# 1-Schematic_Volumetric_Display.net
KiCad netlist of a schematic drawn in EasyEDA
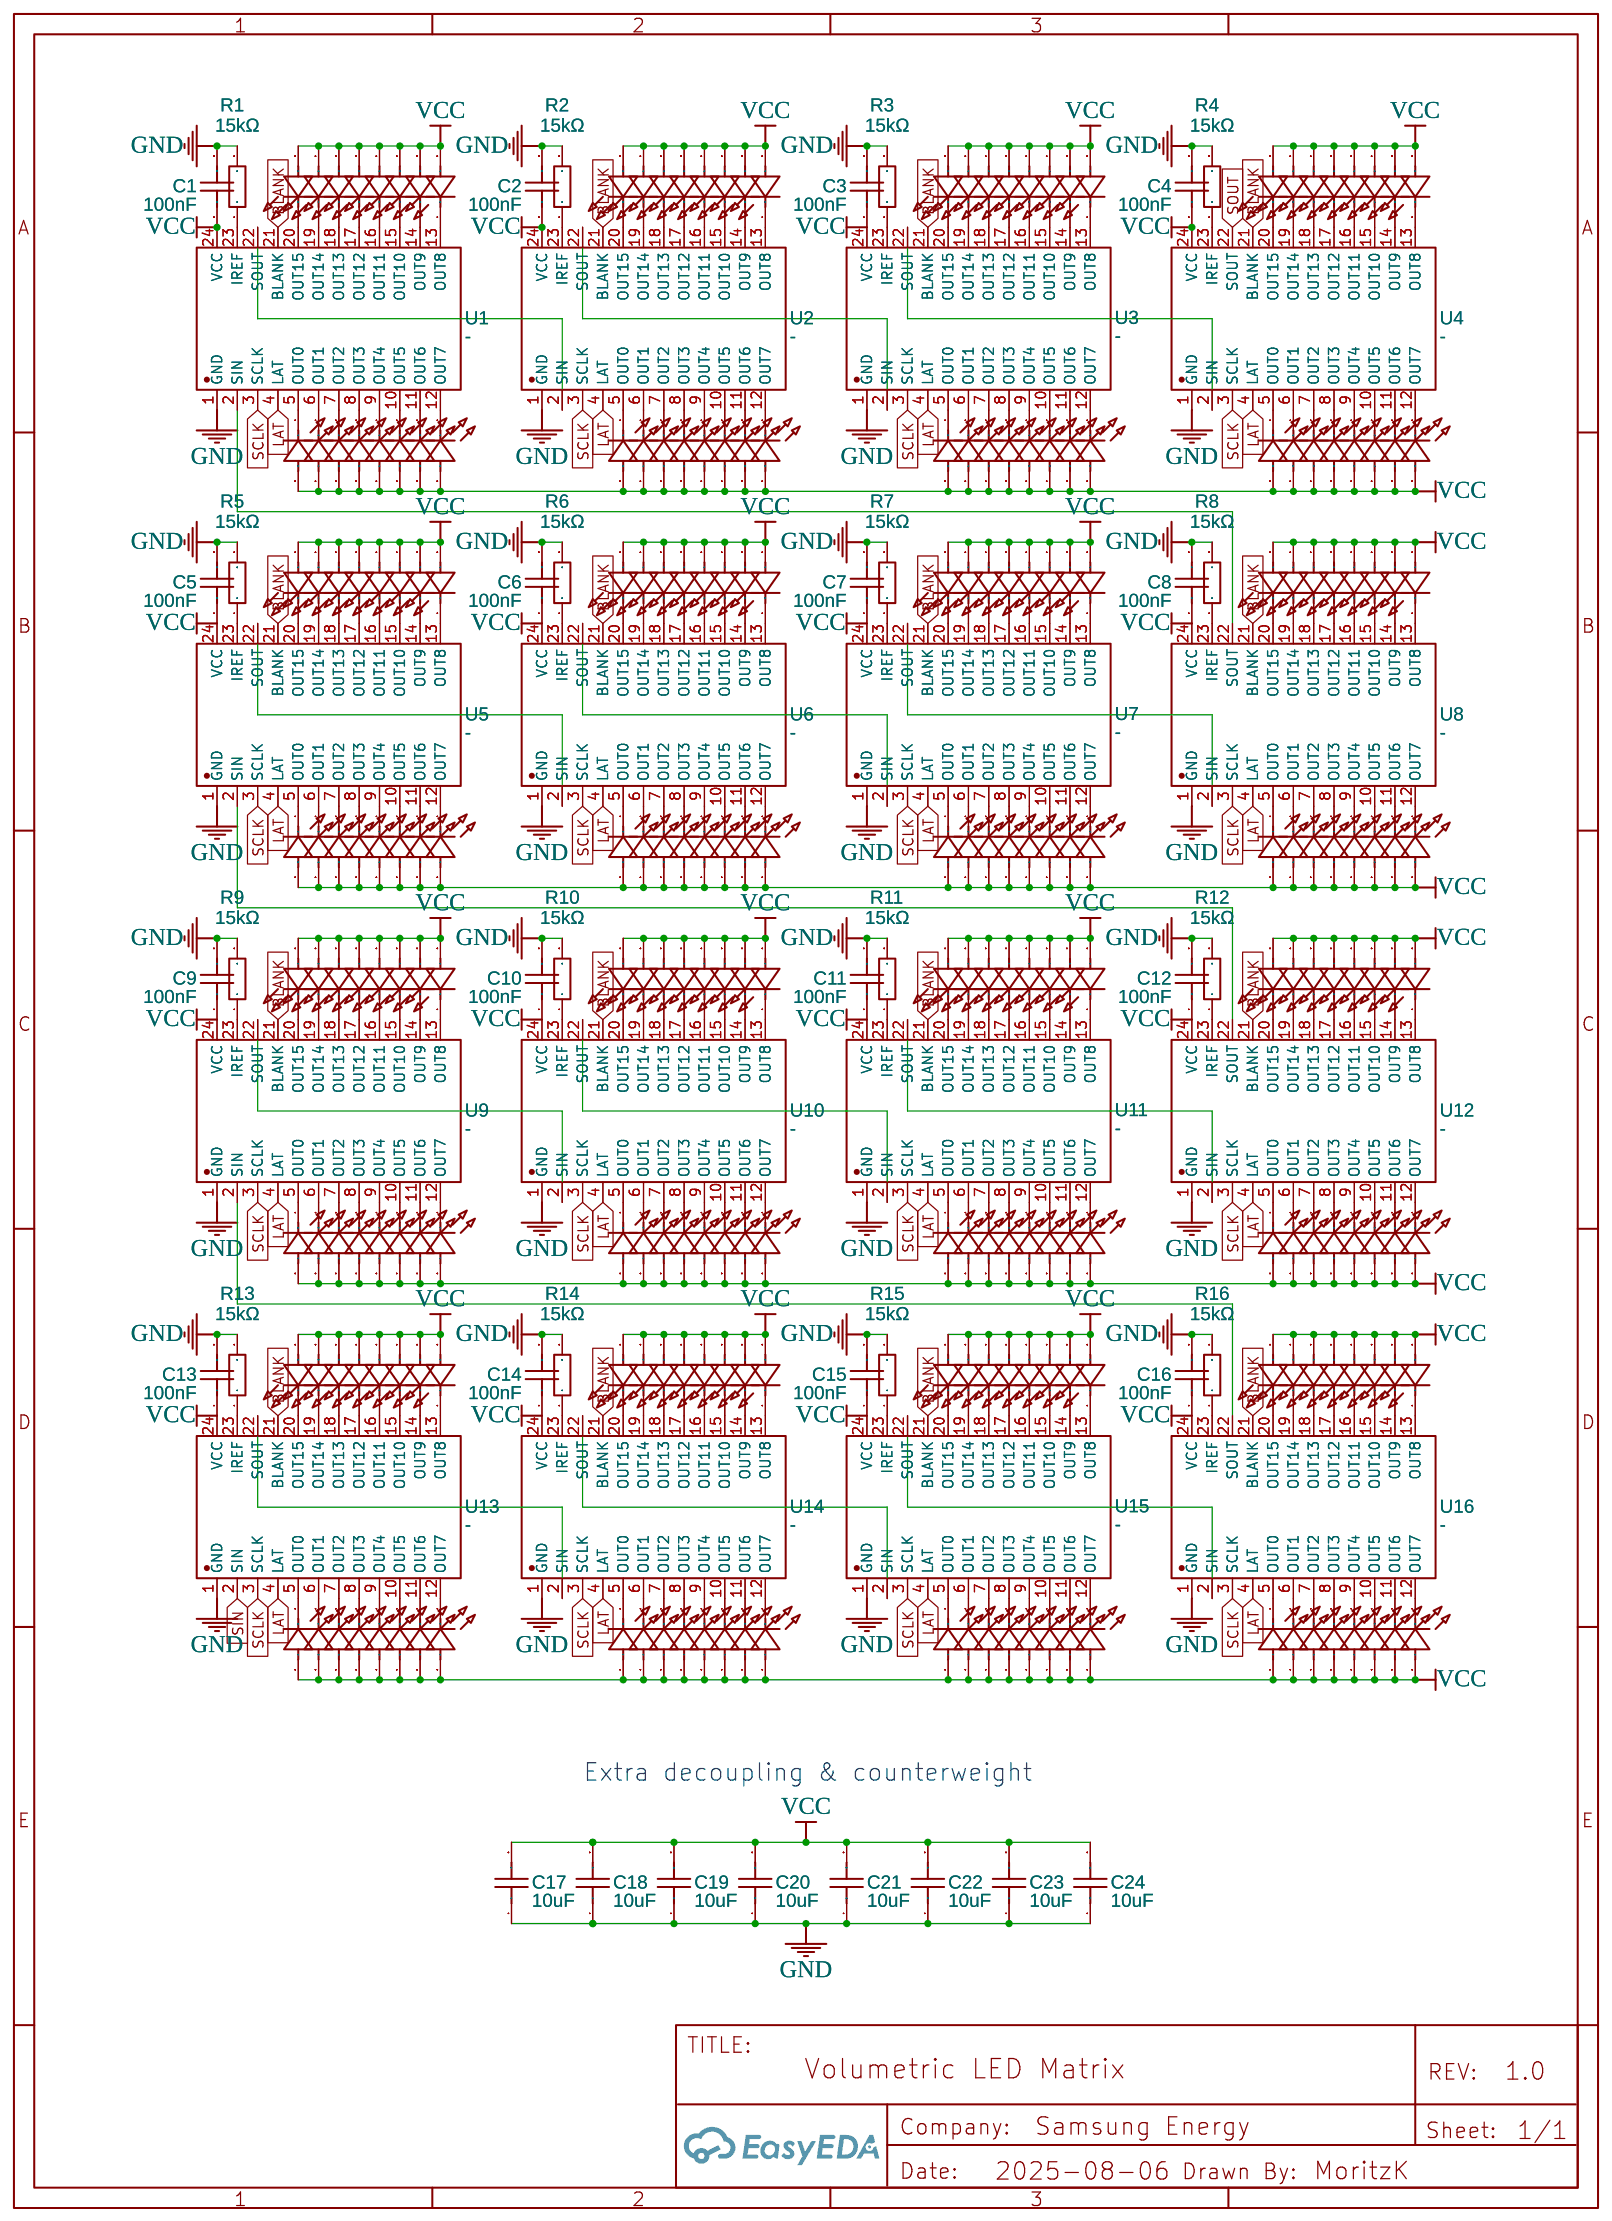
[diagram p0: schematic sheet]

(export (version "E")
  (design (tool "Eeschema 10.0.6"))
  (components
    (comp (ref "C1")
      (value "100nF")
      (fields
        (field (name "Manufacturer Part") "CC0603KRX7R9BB104")
        (field (name "Manufacturer") "YAGEO(国巨)")
      )
      (libsource (lib "") (part "CC0603KRX7R9BB104"))
    )
    (comp (ref "C2")
      (value "100nF")
      (fields
        (field (name "Manufacturer Part") "CC0603KRX7R9BB104")
        (field (name "Manufacturer") "YAGEO(国巨)")
      )
      (libsource (lib "") (part "CC0603KRX7R9BB104"))
    )
    (comp (ref "C3")
      (value "100nF")
      (fields
        (field (name "Manufacturer Part") "CC0603KRX7R9BB104")
        (field (name "Manufacturer") "YAGEO(国巨)")
      )
      (libsource (lib "") (part "CC0603KRX7R9BB104"))
    )
    (comp (ref "C4")
      (value "100nF")
      (fields
        (field (name "Manufacturer Part") "CC0603KRX7R9BB104")
        (field (name "Manufacturer") "YAGEO(国巨)")
      )
      (libsource (lib "") (part "CC0603KRX7R9BB104"))
    )
    (comp (ref "C5")
      (value "100nF")
      (fields
        (field (name "Manufacturer Part") "CC0603KRX7R9BB104")
        (field (name "Manufacturer") "YAGEO(国巨)")
      )
      (libsource (lib "") (part "CC0603KRX7R9BB104"))
    )
    (comp (ref "C6")
      (value "100nF")
      (fields
        (field (name "Manufacturer Part") "CC0603KRX7R9BB104")
        (field (name "Manufacturer") "YAGEO(国巨)")
      )
      (libsource (lib "") (part "CC0603KRX7R9BB104"))
    )
    (comp (ref "C7")
      (value "100nF")
      (fields
        (field (name "Manufacturer Part") "CC0603KRX7R9BB104")
        (field (name "Manufacturer") "YAGEO(国巨)")
      )
      (libsource (lib "") (part "CC0603KRX7R9BB104"))
    )
    (comp (ref "C8")
      (value "100nF")
      (fields
        (field (name "Manufacturer Part") "CC0603KRX7R9BB104")
        (field (name "Manufacturer") "YAGEO(国巨)")
      )
      (libsource (lib "") (part "CC0603KRX7R9BB104"))
    )
    (comp (ref "C9")
      (value "100nF")
      (fields
        (field (name "Manufacturer Part") "CC0603KRX7R9BB104")
        (field (name "Manufacturer") "YAGEO(国巨)")
      )
      (libsource (lib "") (part "CC0603KRX7R9BB104"))
    )
    (comp (ref "C10")
      (value "100nF")
      (fields
        (field (name "Manufacturer Part") "CC0603KRX7R9BB104")
        (field (name "Manufacturer") "YAGEO(国巨)")
      )
      (libsource (lib "") (part "CC0603KRX7R9BB104"))
    )
    (comp (ref "C11")
      (value "100nF")
      (fields
        (field (name "Manufacturer Part") "CC0603KRX7R9BB104")
        (field (name "Manufacturer") "YAGEO(国巨)")
      )
      (libsource (lib "") (part "CC0603KRX7R9BB104"))
    )
    (comp (ref "C12")
      (value "100nF")
      (fields
        (field (name "Manufacturer Part") "CC0603KRX7R9BB104")
        (field (name "Manufacturer") "YAGEO(国巨)")
      )
      (libsource (lib "") (part "CC0603KRX7R9BB104"))
    )
    (comp (ref "C13")
      (value "100nF")
      (fields
        (field (name "Manufacturer Part") "CC0603KRX7R9BB104")
        (field (name "Manufacturer") "YAGEO(国巨)")
      )
      (libsource (lib "") (part "CC0603KRX7R9BB104"))
    )
    (comp (ref "C14")
      (value "100nF")
      (fields
        (field (name "Manufacturer Part") "CC0603KRX7R9BB104")
        (field (name "Manufacturer") "YAGEO(国巨)")
      )
      (libsource (lib "") (part "CC0603KRX7R9BB104"))
    )
    (comp (ref "C15")
      (value "100nF")
      (fields
        (field (name "Manufacturer Part") "CC0603KRX7R9BB104")
        (field (name "Manufacturer") "YAGEO(国巨)")
      )
      (libsource (lib "") (part "CC0603KRX7R9BB104"))
    )
    (comp (ref "C16")
      (value "100nF")
      (fields
        (field (name "Manufacturer Part") "CC0603KRX7R9BB104")
        (field (name "Manufacturer") "YAGEO(国巨)")
      )
      (libsource (lib "") (part "CC0603KRX7R9BB104"))
    )
    (comp (ref "C17")
      (value "10uF")
      (fields
        (field (name "Manufacturer Part") "CL10A106KP8NNNC")
        (field (name "Manufacturer") "SAMSUNG(三星)")
      )
      (libsource (lib "") (part "CL10A106KP8NNNC"))
    )
    (comp (ref "C18")
      (value "10uF")
      (fields
        (field (name "Manufacturer Part") "CL10A106KP8NNNC")
        (field (name "Manufacturer") "SAMSUNG(三星)")
      )
      (libsource (lib "") (part "CL10A106KP8NNNC"))
    )
    (comp (ref "C19")
      (value "10uF")
      (fields
        (field (name "Manufacturer Part") "CL10A106KP8NNNC")
        (field (name "Manufacturer") "SAMSUNG(三星)")
      )
      (libsource (lib "") (part "CL10A106KP8NNNC"))
    )
    (comp (ref "C20")
      (value "10uF")
      (fields
        (field (name "Manufacturer Part") "CL10A106KP8NNNC")
        (field (name "Manufacturer") "SAMSUNG(三星)")
      )
      (libsource (lib "") (part "CL10A106KP8NNNC"))
    )
    (comp (ref "C21")
      (value "10uF")
      (fields
        (field (name "Manufacturer Part") "CL10A106KP8NNNC")
        (field (name "Manufacturer") "SAMSUNG(三星)")
      )
      (libsource (lib "") (part "CL10A106KP8NNNC"))
    )
    (comp (ref "C22")
      (value "10uF")
      (fields
        (field (name "Manufacturer Part") "CL10A106KP8NNNC")
        (field (name "Manufacturer") "SAMSUNG(三星)")
      )
      (libsource (lib "") (part "CL10A106KP8NNNC"))
    )
    (comp (ref "C23")
      (value "10uF")
      (fields
        (field (name "Manufacturer Part") "CL10A106KP8NNNC")
        (field (name "Manufacturer") "SAMSUNG(三星)")
      )
      (libsource (lib "") (part "CL10A106KP8NNNC"))
    )
    (comp (ref "C24")
      (value "10uF")
      (fields
        (field (name "Manufacturer Part") "CL10A106KP8NNNC")
        (field (name "Manufacturer") "SAMSUNG(三星)")
      )
      (libsource (lib "") (part "CL10A106KP8NNNC"))
    )
    (comp (ref "LED1")
      (value "F.0603.00106/P2-0603W7YS2-06T-001")
      (fields (field (name "Manufacturer") "TUOZHAN(拓展光电)"))
      (libsource (lib "") (part "F.0603.00106/P2-0603W7YS2-06T-001_1"))
    )
    (comp (ref "LED2")
      (value "F.0603.00106/P2-0603W7YS2-06T-001")
      (fields (field (name "Manufacturer") "TUOZHAN(拓展光电)"))
      (libsource (lib "") (part "F.0603.00106/P2-0603W7YS2-06T-001_1"))
    )
    (comp (ref "LED3")
      (value "F.0603.00106/P2-0603W7YS2-06T-001")
      (fields (field (name "Manufacturer") "TUOZHAN(拓展光电)"))
      (libsource (lib "") (part "F.0603.00106/P2-0603W7YS2-06T-001_1"))
    )
    (comp (ref "LED4")
      (value "F.0603.00106/P2-0603W7YS2-06T-001")
      (fields (field (name "Manufacturer") "TUOZHAN(拓展光电)"))
      (libsource (lib "") (part "F.0603.00106/P2-0603W7YS2-06T-001_1"))
    )
    (comp (ref "LED5")
      (value "F.0603.00106/P2-0603W7YS2-06T-001")
      (fields (field (name "Manufacturer") "TUOZHAN(拓展光电)"))
      (libsource (lib "") (part "F.0603.00106/P2-0603W7YS2-06T-001_1"))
    )
    (comp (ref "LED6")
      (value "F.0603.00106/P2-0603W7YS2-06T-001")
      (fields (field (name "Manufacturer") "TUOZHAN(拓展光电)"))
      (libsource (lib "") (part "F.0603.00106/P2-0603W7YS2-06T-001_1"))
    )
    (comp (ref "LED7")
      (value "F.0603.00106/P2-0603W7YS2-06T-001")
      (fields (field (name "Manufacturer") "TUOZHAN(拓展光电)"))
      (libsource (lib "") (part "F.0603.00106/P2-0603W7YS2-06T-001_1"))
    )
    (comp (ref "LED8")
      (value "F.0603.00106/P2-0603W7YS2-06T-001")
      (fields (field (name "Manufacturer") "TUOZHAN(拓展光电)"))
      (libsource (lib "") (part "F.0603.00106/P2-0603W7YS2-06T-001_1"))
    )
    (comp (ref "LED9")
      (value "F.0603.00106/P2-0603W7YS2-06T-001")
      (fields (field (name "Manufacturer") "TUOZHAN(拓展光电)"))
      (libsource (lib "") (part "F.0603.00106/P2-0603W7YS2-06T-001_1"))
    )
    (comp (ref "LED10")
      (value "F.0603.00106/P2-0603W7YS2-06T-001")
      (fields (field (name "Manufacturer") "TUOZHAN(拓展光电)"))
      (libsource (lib "") (part "F.0603.00106/P2-0603W7YS2-06T-001_1"))
    )
    (comp (ref "LED11")
      (value "F.0603.00106/P2-0603W7YS2-06T-001")
      (fields (field (name "Manufacturer") "TUOZHAN(拓展光电)"))
      (libsource (lib "") (part "F.0603.00106/P2-0603W7YS2-06T-001_1"))
    )
    (comp (ref "LED12")
      (value "F.0603.00106/P2-0603W7YS2-06T-001")
      (fields (field (name "Manufacturer") "TUOZHAN(拓展光电)"))
      (libsource (lib "") (part "F.0603.00106/P2-0603W7YS2-06T-001_1"))
    )
    (comp (ref "LED13")
      (value "F.0603.00106/P2-0603W7YS2-06T-001")
      (fields (field (name "Manufacturer") "TUOZHAN(拓展光电)"))
      (libsource (lib "") (part "F.0603.00106/P2-0603W7YS2-06T-001_1"))
    )
    (comp (ref "LED14")
      (value "F.0603.00106/P2-0603W7YS2-06T-001")
      (fields (field (name "Manufacturer") "TUOZHAN(拓展光电)"))
      (libsource (lib "") (part "F.0603.00106/P2-0603W7YS2-06T-001_1"))
    )
    (comp (ref "LED15")
      (value "F.0603.00106/P2-0603W7YS2-06T-001")
      (fields (field (name "Manufacturer") "TUOZHAN(拓展光电)"))
      (libsource (lib "") (part "F.0603.00106/P2-0603W7YS2-06T-001_1"))
    )
    (comp (ref "LED16")
      (value "F.0603.00106/P2-0603W7YS2-06T-001")
      (fields (field (name "Manufacturer") "TUOZHAN(拓展光电)"))
      (libsource (lib "") (part "F.0603.00106/P2-0603W7YS2-06T-001_1"))
    )
    (comp (ref "LED17")
      (value "F.0603.00106/P2-0603W7YS2-06T-001")
      (fields (field (name "Manufacturer") "TUOZHAN(拓展光电)"))
      (libsource (lib "") (part "F.0603.00106/P2-0603W7YS2-06T-001_1"))
    )
    (comp (ref "LED18")
      (value "F.0603.00106/P2-0603W7YS2-06T-001")
      (fields (field (name "Manufacturer") "TUOZHAN(拓展光电)"))
      (libsource (lib "") (part "F.0603.00106/P2-0603W7YS2-06T-001_1"))
    )
    (comp (ref "LED19")
      (value "F.0603.00106/P2-0603W7YS2-06T-001")
      (fields (field (name "Manufacturer") "TUOZHAN(拓展光电)"))
      (libsource (lib "") (part "F.0603.00106/P2-0603W7YS2-06T-001_1"))
    )
    (comp (ref "LED20")
      (value "F.0603.00106/P2-0603W7YS2-06T-001")
      (fields (field (name "Manufacturer") "TUOZHAN(拓展光电)"))
      (libsource (lib "") (part "F.0603.00106/P2-0603W7YS2-06T-001_1"))
    )
    (comp (ref "LED21")
      (value "F.0603.00106/P2-0603W7YS2-06T-001")
      (fields (field (name "Manufacturer") "TUOZHAN(拓展光电)"))
      (libsource (lib "") (part "F.0603.00106/P2-0603W7YS2-06T-001_1"))
    )
    (comp (ref "LED22")
      (value "F.0603.00106/P2-0603W7YS2-06T-001")
      (fields (field (name "Manufacturer") "TUOZHAN(拓展光电)"))
      (libsource (lib "") (part "F.0603.00106/P2-0603W7YS2-06T-001_1"))
    )
    (comp (ref "LED23")
      (value "F.0603.00106/P2-0603W7YS2-06T-001")
      (fields (field (name "Manufacturer") "TUOZHAN(拓展光电)"))
      (libsource (lib "") (part "F.0603.00106/P2-0603W7YS2-06T-001_1"))
    )
    (comp (ref "LED24")
      (value "F.0603.00106/P2-0603W7YS2-06T-001")
      (fields (field (name "Manufacturer") "TUOZHAN(拓展光电)"))
      (libsource (lib "") (part "F.0603.00106/P2-0603W7YS2-06T-001_1"))
    )
    (comp (ref "LED25")
      (value "F.0603.00106/P2-0603W7YS2-06T-001")
      (fields (field (name "Manufacturer") "TUOZHAN(拓展光电)"))
      (libsource (lib "") (part "F.0603.00106/P2-0603W7YS2-06T-001_1"))
    )
    (comp (ref "LED26")
      (value "F.0603.00106/P2-0603W7YS2-06T-001")
      (fields (field (name "Manufacturer") "TUOZHAN(拓展光电)"))
      (libsource (lib "") (part "F.0603.00106/P2-0603W7YS2-06T-001_1"))
    )
    (comp (ref "LED27")
      (value "F.0603.00106/P2-0603W7YS2-06T-001")
      (fields (field (name "Manufacturer") "TUOZHAN(拓展光电)"))
      (libsource (lib "") (part "F.0603.00106/P2-0603W7YS2-06T-001_1"))
    )
    (comp (ref "LED28")
      (value "F.0603.00106/P2-0603W7YS2-06T-001")
      (fields (field (name "Manufacturer") "TUOZHAN(拓展光电)"))
      (libsource (lib "") (part "F.0603.00106/P2-0603W7YS2-06T-001_1"))
    )
    (comp (ref "LED29")
      (value "F.0603.00106/P2-0603W7YS2-06T-001")
      (fields (field (name "Manufacturer") "TUOZHAN(拓展光电)"))
      (libsource (lib "") (part "F.0603.00106/P2-0603W7YS2-06T-001_1"))
    )
    (comp (ref "LED30")
      (value "F.0603.00106/P2-0603W7YS2-06T-001")
      (fields (field (name "Manufacturer") "TUOZHAN(拓展光电)"))
      (libsource (lib "") (part "F.0603.00106/P2-0603W7YS2-06T-001_1"))
    )
    (comp (ref "LED31")
      (value "F.0603.00106/P2-0603W7YS2-06T-001")
      (fields (field (name "Manufacturer") "TUOZHAN(拓展光电)"))
      (libsource (lib "") (part "F.0603.00106/P2-0603W7YS2-06T-001_1"))
    )
    (comp (ref "LED32")
      (value "F.0603.00106/P2-0603W7YS2-06T-001")
      (fields (field (name "Manufacturer") "TUOZHAN(拓展光电)"))
      (libsource (lib "") (part "F.0603.00106/P2-0603W7YS2-06T-001_1"))
    )
    (comp (ref "LED33")
      (value "F.0603.00106/P2-0603W7YS2-06T-001")
      (fields (field (name "Manufacturer") "TUOZHAN(拓展光电)"))
      (libsource (lib "") (part "F.0603.00106/P2-0603W7YS2-06T-001"))
    )
    (comp (ref "LED34")
      (value "F.0603.00106/P2-0603W7YS2-06T-001")
      (fields (field (name "Manufacturer") "TUOZHAN(拓展光电)"))
      (libsource (lib "") (part "F.0603.00106/P2-0603W7YS2-06T-001"))
    )
    (comp (ref "LED35")
      (value "F.0603.00106/P2-0603W7YS2-06T-001")
      (fields (field (name "Manufacturer") "TUOZHAN(拓展光电)"))
      (libsource (lib "") (part "F.0603.00106/P2-0603W7YS2-06T-001"))
    )
    (comp (ref "LED36")
      (value "F.0603.00106/P2-0603W7YS2-06T-001")
      (fields (field (name "Manufacturer") "TUOZHAN(拓展光电)"))
      (libsource (lib "") (part "F.0603.00106/P2-0603W7YS2-06T-001"))
    )
    (comp (ref "LED37")
      (value "F.0603.00106/P2-0603W7YS2-06T-001")
      (fields (field (name "Manufacturer") "TUOZHAN(拓展光电)"))
      (libsource (lib "") (part "F.0603.00106/P2-0603W7YS2-06T-001"))
    )
    (comp (ref "LED38")
      (value "F.0603.00106/P2-0603W7YS2-06T-001")
      (fields (field (name "Manufacturer") "TUOZHAN(拓展光电)"))
      (libsource (lib "") (part "F.0603.00106/P2-0603W7YS2-06T-001"))
    )
    (comp (ref "LED39")
      (value "F.0603.00106/P2-0603W7YS2-06T-001")
      (fields (field (name "Manufacturer") "TUOZHAN(拓展光电)"))
      (libsource (lib "") (part "F.0603.00106/P2-0603W7YS2-06T-001"))
    )
    (comp (ref "LED40")
      (value "F.0603.00106/P2-0603W7YS2-06T-001")
      (fields (field (name "Manufacturer") "TUOZHAN(拓展光电)"))
      (libsource (lib "") (part "F.0603.00106/P2-0603W7YS2-06T-001"))
    )
    (comp (ref "LED41")
      (value "F.0603.00106/P2-0603W7YS2-06T-001")
      (fields (field (name "Manufacturer") "TUOZHAN(拓展光电)"))
      (libsource (lib "") (part "F.0603.00106/P2-0603W7YS2-06T-001"))
    )
    (comp (ref "LED42")
      (value "F.0603.00106/P2-0603W7YS2-06T-001")
      (fields (field (name "Manufacturer") "TUOZHAN(拓展光电)"))
      (libsource (lib "") (part "F.0603.00106/P2-0603W7YS2-06T-001"))
    )
    (comp (ref "LED43")
      (value "F.0603.00106/P2-0603W7YS2-06T-001")
      (fields (field (name "Manufacturer") "TUOZHAN(拓展光电)"))
      (libsource (lib "") (part "F.0603.00106/P2-0603W7YS2-06T-001"))
    )
    (comp (ref "LED44")
      (value "F.0603.00106/P2-0603W7YS2-06T-001")
      (fields (field (name "Manufacturer") "TUOZHAN(拓展光电)"))
      (libsource (lib "") (part "F.0603.00106/P2-0603W7YS2-06T-001"))
    )
    (comp (ref "LED45")
      (value "F.0603.00106/P2-0603W7YS2-06T-001")
      (fields (field (name "Manufacturer") "TUOZHAN(拓展光电)"))
      (libsource (lib "") (part "F.0603.00106/P2-0603W7YS2-06T-001"))
    )
    (comp (ref "LED46")
      (value "F.0603.00106/P2-0603W7YS2-06T-001")
      (fields (field (name "Manufacturer") "TUOZHAN(拓展光电)"))
      (libsource (lib "") (part "F.0603.00106/P2-0603W7YS2-06T-001"))
    )
    (comp (ref "LED47")
      (value "F.0603.00106/P2-0603W7YS2-06T-001")
      (fields (field (name "Manufacturer") "TUOZHAN(拓展光电)"))
      (libsource (lib "") (part "F.0603.00106/P2-0603W7YS2-06T-001"))
    )
    (comp (ref "LED48")
      (value "F.0603.00106/P2-0603W7YS2-06T-001")
      (fields (field (name "Manufacturer") "TUOZHAN(拓展光电)"))
      (libsource (lib "") (part "F.0603.00106/P2-0603W7YS2-06T-001"))
    )
    (comp (ref "LED49")
      (value "F.0603.00106/P2-0603W7YS2-06T-001")
      (fields (field (name "Manufacturer") "TUOZHAN(拓展光电)"))
      (libsource (lib "") (part "F.0603.00106/P2-0603W7YS2-06T-001"))
    )
    (comp (ref "LED50")
      (value "F.0603.00106/P2-0603W7YS2-06T-001")
      (fields (field (name "Manufacturer") "TUOZHAN(拓展光电)"))
      (libsource (lib "") (part "F.0603.00106/P2-0603W7YS2-06T-001"))
    )
    (comp (ref "LED51")
      (value "F.0603.00106/P2-0603W7YS2-06T-001")
      (fields (field (name "Manufacturer") "TUOZHAN(拓展光电)"))
      (libsource (lib "") (part "F.0603.00106/P2-0603W7YS2-06T-001"))
    )
    (comp (ref "LED52")
      (value "F.0603.00106/P2-0603W7YS2-06T-001")
      (fields (field (name "Manufacturer") "TUOZHAN(拓展光电)"))
      (libsource (lib "") (part "F.0603.00106/P2-0603W7YS2-06T-001"))
    )
    (comp (ref "LED53")
      (value "F.0603.00106/P2-0603W7YS2-06T-001")
      (fields (field (name "Manufacturer") "TUOZHAN(拓展光电)"))
      (libsource (lib "") (part "F.0603.00106/P2-0603W7YS2-06T-001"))
    )
    (comp (ref "LED54")
      (value "F.0603.00106/P2-0603W7YS2-06T-001")
      (fields (field (name "Manufacturer") "TUOZHAN(拓展光电)"))
      (libsource (lib "") (part "F.0603.00106/P2-0603W7YS2-06T-001"))
    )
    (comp (ref "LED55")
      (value "F.0603.00106/P2-0603W7YS2-06T-001")
      (fields (field (name "Manufacturer") "TUOZHAN(拓展光电)"))
      (libsource (lib "") (part "F.0603.00106/P2-0603W7YS2-06T-001"))
    )
    (comp (ref "LED56")
      (value "F.0603.00106/P2-0603W7YS2-06T-001")
      (fields (field (name "Manufacturer") "TUOZHAN(拓展光电)"))
      (libsource (lib "") (part "F.0603.00106/P2-0603W7YS2-06T-001"))
    )
    (comp (ref "LED57")
      (value "F.0603.00106/P2-0603W7YS2-06T-001")
      (fields (field (name "Manufacturer") "TUOZHAN(拓展光电)"))
      (libsource (lib "") (part "F.0603.00106/P2-0603W7YS2-06T-001"))
    )
    (comp (ref "LED58")
      (value "F.0603.00106/P2-0603W7YS2-06T-001")
      (fields (field (name "Manufacturer") "TUOZHAN(拓展光电)"))
      (libsource (lib "") (part "F.0603.00106/P2-0603W7YS2-06T-001"))
    )
    (comp (ref "LED59")
      (value "F.0603.00106/P2-0603W7YS2-06T-001")
      (fields (field (name "Manufacturer") "TUOZHAN(拓展光电)"))
      (libsource (lib "") (part "F.0603.00106/P2-0603W7YS2-06T-001"))
    )
    (comp (ref "LED60")
      (value "F.0603.00106/P2-0603W7YS2-06T-001")
      (fields (field (name "Manufacturer") "TUOZHAN(拓展光电)"))
      (libsource (lib "") (part "F.0603.00106/P2-0603W7YS2-06T-001"))
    )
    (comp (ref "LED61")
      (value "F.0603.00106/P2-0603W7YS2-06T-001")
      (fields (field (name "Manufacturer") "TUOZHAN(拓展光电)"))
      (libsource (lib "") (part "F.0603.00106/P2-0603W7YS2-06T-001"))
    )
    (comp (ref "LED62")
      (value "F.0603.00106/P2-0603W7YS2-06T-001")
      (fields (field (name "Manufacturer") "TUOZHAN(拓展光电)"))
      (libsource (lib "") (part "F.0603.00106/P2-0603W7YS2-06T-001"))
    )
    (comp (ref "LED63")
      (value "F.0603.00106/P2-0603W7YS2-06T-001")
      (fields (field (name "Manufacturer") "TUOZHAN(拓展光电)"))
      (libsource (lib "") (part "F.0603.00106/P2-0603W7YS2-06T-001"))
    )
    (comp (ref "LED64")
      (value "F.0603.00106/P2-0603W7YS2-06T-001")
      (fields (field (name "Manufacturer") "TUOZHAN(拓展光电)"))
      (libsource (lib "") (part "F.0603.00106/P2-0603W7YS2-06T-001"))
    )
    (comp (ref "LED65")
      (value "F.0603.00106/P2-0603W7YS2-06T-001")
      (fields (field (name "Manufacturer") "TUOZHAN(拓展光电)"))
      (libsource (lib "") (part "F.0603.00106/P2-0603W7YS2-06T-001_1"))
    )
    (comp (ref "LED66")
      (value "F.0603.00106/P2-0603W7YS2-06T-001")
      (fields (field (name "Manufacturer") "TUOZHAN(拓展光电)"))
      (libsource (lib "") (part "F.0603.00106/P2-0603W7YS2-06T-001_1"))
    )
    (comp (ref "LED67")
      (value "F.0603.00106/P2-0603W7YS2-06T-001")
      (fields (field (name "Manufacturer") "TUOZHAN(拓展光电)"))
      (libsource (lib "") (part "F.0603.00106/P2-0603W7YS2-06T-001_1"))
    )
    (comp (ref "LED68")
      (value "F.0603.00106/P2-0603W7YS2-06T-001")
      (fields (field (name "Manufacturer") "TUOZHAN(拓展光电)"))
      (libsource (lib "") (part "F.0603.00106/P2-0603W7YS2-06T-001_1"))
    )
    (comp (ref "LED69")
      (value "F.0603.00106/P2-0603W7YS2-06T-001")
      (fields (field (name "Manufacturer") "TUOZHAN(拓展光电)"))
      (libsource (lib "") (part "F.0603.00106/P2-0603W7YS2-06T-001_1"))
    )
    (comp (ref "LED70")
      (value "F.0603.00106/P2-0603W7YS2-06T-001")
      (fields (field (name "Manufacturer") "TUOZHAN(拓展光电)"))
      (libsource (lib "") (part "F.0603.00106/P2-0603W7YS2-06T-001_1"))
    )
    (comp (ref "LED71")
      (value "F.0603.00106/P2-0603W7YS2-06T-001")
      (fields (field (name "Manufacturer") "TUOZHAN(拓展光电)"))
      (libsource (lib "") (part "F.0603.00106/P2-0603W7YS2-06T-001_1"))
    )
    (comp (ref "LED72")
      (value "F.0603.00106/P2-0603W7YS2-06T-001")
      (fields (field (name "Manufacturer") "TUOZHAN(拓展光电)"))
      (libsource (lib "") (part "F.0603.00106/P2-0603W7YS2-06T-001_1"))
    )
    (comp (ref "LED73")
      (value "F.0603.00106/P2-0603W7YS2-06T-001")
      (fields (field (name "Manufacturer") "TUOZHAN(拓展光电)"))
      (libsource (lib "") (part "F.0603.00106/P2-0603W7YS2-06T-001_1"))
    )
    (comp (ref "LED74")
      (value "F.0603.00106/P2-0603W7YS2-06T-001")
      (fields (field (name "Manufacturer") "TUOZHAN(拓展光电)"))
      (libsource (lib "") (part "F.0603.00106/P2-0603W7YS2-06T-001_1"))
    )
    (comp (ref "LED75")
      (value "F.0603.00106/P2-0603W7YS2-06T-001")
      (fields (field (name "Manufacturer") "TUOZHAN(拓展光电)"))
      (libsource (lib "") (part "F.0603.00106/P2-0603W7YS2-06T-001_1"))
    )
    (comp (ref "LED76")
      (value "F.0603.00106/P2-0603W7YS2-06T-001")
      (fields (field (name "Manufacturer") "TUOZHAN(拓展光电)"))
      (libsource (lib "") (part "F.0603.00106/P2-0603W7YS2-06T-001_1"))
    )
    (comp (ref "LED77")
      (value "F.0603.00106/P2-0603W7YS2-06T-001")
      (fields (field (name "Manufacturer") "TUOZHAN(拓展光电)"))
      (libsource (lib "") (part "F.0603.00106/P2-0603W7YS2-06T-001_1"))
    )
    (comp (ref "LED78")
      (value "F.0603.00106/P2-0603W7YS2-06T-001")
      (fields (field (name "Manufacturer") "TUOZHAN(拓展光电)"))
      (libsource (lib "") (part "F.0603.00106/P2-0603W7YS2-06T-001_1"))
    )
    (comp (ref "LED79")
      (value "F.0603.00106/P2-0603W7YS2-06T-001")
      (fields (field (name "Manufacturer") "TUOZHAN(拓展光电)"))
      (libsource (lib "") (part "F.0603.00106/P2-0603W7YS2-06T-001_1"))
    )
    (comp (ref "LED80")
      (value "F.0603.00106/P2-0603W7YS2-06T-001")
      (fields (field (name "Manufacturer") "TUOZHAN(拓展光电)"))
      (libsource (lib "") (part "F.0603.00106/P2-0603W7YS2-06T-001_1"))
    )
    (comp (ref "LED81")
      (value "F.0603.00106/P2-0603W7YS2-06T-001")
      (fields (field (name "Manufacturer") "TUOZHAN(拓展光电)"))
      (libsource (lib "") (part "F.0603.00106/P2-0603W7YS2-06T-001_1"))
    )
    (comp (ref "LED82")
      (value "F.0603.00106/P2-0603W7YS2-06T-001")
      (fields (field (name "Manufacturer") "TUOZHAN(拓展光电)"))
      (libsource (lib "") (part "F.0603.00106/P2-0603W7YS2-06T-001_1"))
    )
    (comp (ref "LED83")
      (value "F.0603.00106/P2-0603W7YS2-06T-001")
      (fields (field (name "Manufacturer") "TUOZHAN(拓展光电)"))
      (libsource (lib "") (part "F.0603.00106/P2-0603W7YS2-06T-001_1"))
    )
    (comp (ref "LED84")
      (value "F.0603.00106/P2-0603W7YS2-06T-001")
      (fields (field (name "Manufacturer") "TUOZHAN(拓展光电)"))
      (libsource (lib "") (part "F.0603.00106/P2-0603W7YS2-06T-001_1"))
    )
    (comp (ref "LED85")
      (value "F.0603.00106/P2-0603W7YS2-06T-001")
      (fields (field (name "Manufacturer") "TUOZHAN(拓展光电)"))
      (libsource (lib "") (part "F.0603.00106/P2-0603W7YS2-06T-001_1"))
    )
    (comp (ref "LED86")
      (value "F.0603.00106/P2-0603W7YS2-06T-001")
      (fields (field (name "Manufacturer") "TUOZHAN(拓展光电)"))
      (libsource (lib "") (part "F.0603.00106/P2-0603W7YS2-06T-001_1"))
    )
    (comp (ref "LED87")
      (value "F.0603.00106/P2-0603W7YS2-06T-001")
      (fields (field (name "Manufacturer") "TUOZHAN(拓展光电)"))
      (libsource (lib "") (part "F.0603.00106/P2-0603W7YS2-06T-001_1"))
    )
    (comp (ref "LED88")
      (value "F.0603.00106/P2-0603W7YS2-06T-001")
      (fields (field (name "Manufacturer") "TUOZHAN(拓展光电)"))
      (libsource (lib "") (part "F.0603.00106/P2-0603W7YS2-06T-001_1"))
    )
    (comp (ref "LED89")
      (value "F.0603.00106/P2-0603W7YS2-06T-001")
      (fields (field (name "Manufacturer") "TUOZHAN(拓展光电)"))
      (libsource (lib "") (part "F.0603.00106/P2-0603W7YS2-06T-001_1"))
    )
    (comp (ref "LED90")
      (value "F.0603.00106/P2-0603W7YS2-06T-001")
      (fields (field (name "Manufacturer") "TUOZHAN(拓展光电)"))
      (libsource (lib "") (part "F.0603.00106/P2-0603W7YS2-06T-001_1"))
    )
    (comp (ref "LED91")
      (value "F.0603.00106/P2-0603W7YS2-06T-001")
      (fields (field (name "Manufacturer") "TUOZHAN(拓展光电)"))
      (libsource (lib "") (part "F.0603.00106/P2-0603W7YS2-06T-001_1"))
    )
    (comp (ref "LED92")
      (value "F.0603.00106/P2-0603W7YS2-06T-001")
      (fields (field (name "Manufacturer") "TUOZHAN(拓展光电)"))
      (libsource (lib "") (part "F.0603.00106/P2-0603W7YS2-06T-001_1"))
    )
    (comp (ref "LED93")
      (value "F.0603.00106/P2-0603W7YS2-06T-001")
      (fields (field (name "Manufacturer") "TUOZHAN(拓展光电)"))
      (libsource (lib "") (part "F.0603.00106/P2-0603W7YS2-06T-001_1"))
    )
    (comp (ref "LED94")
      (value "F.0603.00106/P2-0603W7YS2-06T-001")
      (fields (field (name "Manufacturer") "TUOZHAN(拓展光电)"))
      (libsource (lib "") (part "F.0603.00106/P2-0603W7YS2-06T-001_1"))
    )
    (comp (ref "LED95")
      (value "F.0603.00106/P2-0603W7YS2-06T-001")
      (fields (field (name "Manufacturer") "TUOZHAN(拓展光电)"))
      (libsource (lib "") (part "F.0603.00106/P2-0603W7YS2-06T-001_1"))
    )
    (comp (ref "LED96")
      (value "F.0603.00106/P2-0603W7YS2-06T-001")
      (fields (field (name "Manufacturer") "TUOZHAN(拓展光电)"))
      (libsource (lib "") (part "F.0603.00106/P2-0603W7YS2-06T-001_1"))
    )
    (comp (ref "LED97")
      (value "F.0603.00106/P2-0603W7YS2-06T-001")
      (fields (field (name "Manufacturer") "TUOZHAN(拓展光电)"))
      (libsource (lib "") (part "F.0603.00106/P2-0603W7YS2-06T-001"))
    )
    (comp (ref "LED98")
      (value "F.0603.00106/P2-0603W7YS2-06T-001")
      (fields (field (name "Manufacturer") "TUOZHAN(拓展光电)"))
      (libsource (lib "") (part "F.0603.00106/P2-0603W7YS2-06T-001"))
    )
    (comp (ref "LED99")
      (value "F.0603.00106/P2-0603W7YS2-06T-001")
      (fields (field (name "Manufacturer") "TUOZHAN(拓展光电)"))
      (libsource (lib "") (part "F.0603.00106/P2-0603W7YS2-06T-001"))
    )
    (comp (ref "LED100")
      (value "F.0603.00106/P2-0603W7YS2-06T-001")
      (fields (field (name "Manufacturer") "TUOZHAN(拓展光电)"))
      (libsource (lib "") (part "F.0603.00106/P2-0603W7YS2-06T-001"))
    )
    (comp (ref "LED101")
      (value "F.0603.00106/P2-0603W7YS2-06T-001")
      (fields (field (name "Manufacturer") "TUOZHAN(拓展光电)"))
      (libsource (lib "") (part "F.0603.00106/P2-0603W7YS2-06T-001"))
    )
    (comp (ref "LED102")
      (value "F.0603.00106/P2-0603W7YS2-06T-001")
      (fields (field (name "Manufacturer") "TUOZHAN(拓展光电)"))
      (libsource (lib "") (part "F.0603.00106/P2-0603W7YS2-06T-001"))
    )
    (comp (ref "LED103")
      (value "F.0603.00106/P2-0603W7YS2-06T-001")
      (fields (field (name "Manufacturer") "TUOZHAN(拓展光电)"))
      (libsource (lib "") (part "F.0603.00106/P2-0603W7YS2-06T-001"))
    )
    (comp (ref "LED104")
      (value "F.0603.00106/P2-0603W7YS2-06T-001")
      (fields (field (name "Manufacturer") "TUOZHAN(拓展光电)"))
      (libsource (lib "") (part "F.0603.00106/P2-0603W7YS2-06T-001"))
    )
    (comp (ref "LED105")
      (value "F.0603.00106/P2-0603W7YS2-06T-001")
      (fields (field (name "Manufacturer") "TUOZHAN(拓展光电)"))
      (libsource (lib "") (part "F.0603.00106/P2-0603W7YS2-06T-001"))
    )
    (comp (ref "LED106")
      (value "F.0603.00106/P2-0603W7YS2-06T-001")
      (fields (field (name "Manufacturer") "TUOZHAN(拓展光电)"))
      (libsource (lib "") (part "F.0603.00106/P2-0603W7YS2-06T-001"))
    )
    (comp (ref "LED107")
      (value "F.0603.00106/P2-0603W7YS2-06T-001")
      (fields (field (name "Manufacturer") "TUOZHAN(拓展光电)"))
      (libsource (lib "") (part "F.0603.00106/P2-0603W7YS2-06T-001"))
    )
    (comp (ref "LED108")
      (value "F.0603.00106/P2-0603W7YS2-06T-001")
      (fields (field (name "Manufacturer") "TUOZHAN(拓展光电)"))
      (libsource (lib "") (part "F.0603.00106/P2-0603W7YS2-06T-001"))
    )
    (comp (ref "LED109")
      (value "F.0603.00106/P2-0603W7YS2-06T-001")
      (fields (field (name "Manufacturer") "TUOZHAN(拓展光电)"))
      (libsource (lib "") (part "F.0603.00106/P2-0603W7YS2-06T-001"))
    )
    (comp (ref "LED110")
      (value "F.0603.00106/P2-0603W7YS2-06T-001")
      (fields (field (name "Manufacturer") "TUOZHAN(拓展光电)"))
      (libsource (lib "") (part "F.0603.00106/P2-0603W7YS2-06T-001"))
    )
    (comp (ref "LED111")
      (value "F.0603.00106/P2-0603W7YS2-06T-001")
      (fields (field (name "Manufacturer") "TUOZHAN(拓展光电)"))
      (libsource (lib "") (part "F.0603.00106/P2-0603W7YS2-06T-001"))
    )
    (comp (ref "LED112")
      (value "F.0603.00106/P2-0603W7YS2-06T-001")
      (fields (field (name "Manufacturer") "TUOZHAN(拓展光电)"))
      (libsource (lib "") (part "F.0603.00106/P2-0603W7YS2-06T-001"))
    )
    (comp (ref "LED113")
      (value "F.0603.00106/P2-0603W7YS2-06T-001")
      (fields (field (name "Manufacturer") "TUOZHAN(拓展光电)"))
      (libsource (lib "") (part "F.0603.00106/P2-0603W7YS2-06T-001"))
    )
    (comp (ref "LED114")
      (value "F.0603.00106/P2-0603W7YS2-06T-001")
      (fields (field (name "Manufacturer") "TUOZHAN(拓展光电)"))
      (libsource (lib "") (part "F.0603.00106/P2-0603W7YS2-06T-001"))
    )
    (comp (ref "LED115")
      (value "F.0603.00106/P2-0603W7YS2-06T-001")
      (fields (field (name "Manufacturer") "TUOZHAN(拓展光电)"))
      (libsource (lib "") (part "F.0603.00106/P2-0603W7YS2-06T-001"))
    )
    (comp (ref "LED116")
      (value "F.0603.00106/P2-0603W7YS2-06T-001")
      (fields (field (name "Manufacturer") "TUOZHAN(拓展光电)"))
      (libsource (lib "") (part "F.0603.00106/P2-0603W7YS2-06T-001"))
    )
    (comp (ref "LED117")
      (value "F.0603.00106/P2-0603W7YS2-06T-001")
      (fields (field (name "Manufacturer") "TUOZHAN(拓展光电)"))
      (libsource (lib "") (part "F.0603.00106/P2-0603W7YS2-06T-001"))
    )
    (comp (ref "LED118")
      (value "F.0603.00106/P2-0603W7YS2-06T-001")
      (fields (field (name "Manufacturer") "TUOZHAN(拓展光电)"))
      (libsource (lib "") (part "F.0603.00106/P2-0603W7YS2-06T-001"))
    )
    (comp (ref "LED119")
      (value "F.0603.00106/P2-0603W7YS2-06T-001")
      (fields (field (name "Manufacturer") "TUOZHAN(拓展光电)"))
      (libsource (lib "") (part "F.0603.00106/P2-0603W7YS2-06T-001"))
    )
    (comp (ref "LED120")
      (value "F.0603.00106/P2-0603W7YS2-06T-001")
      (fields (field (name "Manufacturer") "TUOZHAN(拓展光电)"))
      (libsource (lib "") (part "F.0603.00106/P2-0603W7YS2-06T-001"))
    )
    (comp (ref "LED121")
      (value "F.0603.00106/P2-0603W7YS2-06T-001")
      (fields (field (name "Manufacturer") "TUOZHAN(拓展光电)"))
      (libsource (lib "") (part "F.0603.00106/P2-0603W7YS2-06T-001"))
    )
    (comp (ref "LED122")
      (value "F.0603.00106/P2-0603W7YS2-06T-001")
      (fields (field (name "Manufacturer") "TUOZHAN(拓展光电)"))
      (libsource (lib "") (part "F.0603.00106/P2-0603W7YS2-06T-001"))
    )
    (comp (ref "LED123")
      (value "F.0603.00106/P2-0603W7YS2-06T-001")
      (fields (field (name "Manufacturer") "TUOZHAN(拓展光电)"))
      (libsource (lib "") (part "F.0603.00106/P2-0603W7YS2-06T-001"))
    )
    (comp (ref "LED124")
      (value "F.0603.00106/P2-0603W7YS2-06T-001")
      (fields (field (name "Manufacturer") "TUOZHAN(拓展光电)"))
      (libsource (lib "") (part "F.0603.00106/P2-0603W7YS2-06T-001"))
    )
    (comp (ref "LED125")
      (value "F.0603.00106/P2-0603W7YS2-06T-001")
      (fields (field (name "Manufacturer") "TUOZHAN(拓展光电)"))
      (libsource (lib "") (part "F.0603.00106/P2-0603W7YS2-06T-001"))
    )
    (comp (ref "LED126")
      (value "F.0603.00106/P2-0603W7YS2-06T-001")
      (fields (field (name "Manufacturer") "TUOZHAN(拓展光电)"))
      (libsource (lib "") (part "F.0603.00106/P2-0603W7YS2-06T-001"))
    )
    (comp (ref "LED127")
      (value "F.0603.00106/P2-0603W7YS2-06T-001")
      (fields (field (name "Manufacturer") "TUOZHAN(拓展光电)"))
      (libsource (lib "") (part "F.0603.00106/P2-0603W7YS2-06T-001"))
    )
    (comp (ref "LED128")
      (value "F.0603.00106/P2-0603W7YS2-06T-001")
      (fields (field (name "Manufacturer") "TUOZHAN(拓展光电)"))
      (libsource (lib "") (part "F.0603.00106/P2-0603W7YS2-06T-001"))
    )
    (comp (ref "LED129")
      (value "F.0603.00106/P2-0603W7YS2-06T-001")
      (fields (field (name "Manufacturer") "TUOZHAN(拓展光电)"))
      (libsource (lib "") (part "F.0603.00106/P2-0603W7YS2-06T-001_1"))
    )
    (comp (ref "LED130")
      (value "F.0603.00106/P2-0603W7YS2-06T-001")
      (fields (field (name "Manufacturer") "TUOZHAN(拓展光电)"))
      (libsource (lib "") (part "F.0603.00106/P2-0603W7YS2-06T-001_1"))
    )
    (comp (ref "LED131")
      (value "F.0603.00106/P2-0603W7YS2-06T-001")
      (fields (field (name "Manufacturer") "TUOZHAN(拓展光电)"))
      (libsource (lib "") (part "F.0603.00106/P2-0603W7YS2-06T-001_1"))
    )
    (comp (ref "LED132")
      (value "F.0603.00106/P2-0603W7YS2-06T-001")
      (fields (field (name "Manufacturer") "TUOZHAN(拓展光电)"))
      (libsource (lib "") (part "F.0603.00106/P2-0603W7YS2-06T-001_1"))
    )
    (comp (ref "LED133")
      (value "F.0603.00106/P2-0603W7YS2-06T-001")
      (fields (field (name "Manufacturer") "TUOZHAN(拓展光电)"))
      (libsource (lib "") (part "F.0603.00106/P2-0603W7YS2-06T-001_1"))
    )
    (comp (ref "LED134")
      (value "F.0603.00106/P2-0603W7YS2-06T-001")
      (fields (field (name "Manufacturer") "TUOZHAN(拓展光电)"))
      (libsource (lib "") (part "F.0603.00106/P2-0603W7YS2-06T-001_1"))
    )
    (comp (ref "LED135")
      (value "F.0603.00106/P2-0603W7YS2-06T-001")
      (fields (field (name "Manufacturer") "TUOZHAN(拓展光电)"))
      (libsource (lib "") (part "F.0603.00106/P2-0603W7YS2-06T-001_1"))
    )
    (comp (ref "LED136")
      (value "F.0603.00106/P2-0603W7YS2-06T-001")
      (fields (field (name "Manufacturer") "TUOZHAN(拓展光电)"))
      (libsource (lib "") (part "F.0603.00106/P2-0603W7YS2-06T-001_1"))
    )
    (comp (ref "LED137")
      (value "F.0603.00106/P2-0603W7YS2-06T-001")
      (fields (field (name "Manufacturer") "TUOZHAN(拓展光电)"))
      (libsource (lib "") (part "F.0603.00106/P2-0603W7YS2-06T-001_1"))
    )
    (comp (ref "LED138")
      (value "F.0603.00106/P2-0603W7YS2-06T-001")
      (fields (field (name "Manufacturer") "TUOZHAN(拓展光电)"))
      (libsource (lib "") (part "F.0603.00106/P2-0603W7YS2-06T-001_1"))
    )
    (comp (ref "LED139")
      (value "F.0603.00106/P2-0603W7YS2-06T-001")
      (fields (field (name "Manufacturer") "TUOZHAN(拓展光电)"))
      (libsource (lib "") (part "F.0603.00106/P2-0603W7YS2-06T-001_1"))
    )
    (comp (ref "LED140")
      (value "F.0603.00106/P2-0603W7YS2-06T-001")
      (fields (field (name "Manufacturer") "TUOZHAN(拓展光电)"))
      (libsource (lib "") (part "F.0603.00106/P2-0603W7YS2-06T-001_1"))
    )
    (comp (ref "LED141")
      (value "F.0603.00106/P2-0603W7YS2-06T-001")
      (fields (field (name "Manufacturer") "TUOZHAN(拓展光电)"))
      (libsource (lib "") (part "F.0603.00106/P2-0603W7YS2-06T-001_1"))
    )
    (comp (ref "LED142")
      (value "F.0603.00106/P2-0603W7YS2-06T-001")
      (fields (field (name "Manufacturer") "TUOZHAN(拓展光电)"))
      (libsource (lib "") (part "F.0603.00106/P2-0603W7YS2-06T-001_1"))
    )
    (comp (ref "LED143")
      (value "F.0603.00106/P2-0603W7YS2-06T-001")
      (fields (field (name "Manufacturer") "TUOZHAN(拓展光电)"))
      (libsource (lib "") (part "F.0603.00106/P2-0603W7YS2-06T-001_1"))
    )
    (comp (ref "LED144")
      (value "F.0603.00106/P2-0603W7YS2-06T-001")
      (fields (field (name "Manufacturer") "TUOZHAN(拓展光电)"))
      (libsource (lib "") (part "F.0603.00106/P2-0603W7YS2-06T-001_1"))
    )
    (comp (ref "LED145")
      (value "F.0603.00106/P2-0603W7YS2-06T-001")
      (fields (field (name "Manufacturer") "TUOZHAN(拓展光电)"))
      (libsource (lib "") (part "F.0603.00106/P2-0603W7YS2-06T-001_1"))
    )
    (comp (ref "LED146")
      (value "F.0603.00106/P2-0603W7YS2-06T-001")
      (fields (field (name "Manufacturer") "TUOZHAN(拓展光电)"))
      (libsource (lib "") (part "F.0603.00106/P2-0603W7YS2-06T-001_1"))
    )
    (comp (ref "LED147")
      (value "F.0603.00106/P2-0603W7YS2-06T-001")
      (fields (field (name "Manufacturer") "TUOZHAN(拓展光电)"))
      (libsource (lib "") (part "F.0603.00106/P2-0603W7YS2-06T-001_1"))
    )
    (comp (ref "LED148")
      (value "F.0603.00106/P2-0603W7YS2-06T-001")
      (fields (field (name "Manufacturer") "TUOZHAN(拓展光电)"))
      (libsource (lib "") (part "F.0603.00106/P2-0603W7YS2-06T-001_1"))
    )
    (comp (ref "LED149")
      (value "F.0603.00106/P2-0603W7YS2-06T-001")
      (fields (field (name "Manufacturer") "TUOZHAN(拓展光电)"))
      (libsource (lib "") (part "F.0603.00106/P2-0603W7YS2-06T-001_1"))
    )
    (comp (ref "LED150")
      (value "F.0603.00106/P2-0603W7YS2-06T-001")
      (fields (field (name "Manufacturer") "TUOZHAN(拓展光电)"))
      (libsource (lib "") (part "F.0603.00106/P2-0603W7YS2-06T-001_1"))
    )
    (comp (ref "LED151")
      (value "F.0603.00106/P2-0603W7YS2-06T-001")
      (fields (field (name "Manufacturer") "TUOZHAN(拓展光电)"))
      (libsource (lib "") (part "F.0603.00106/P2-0603W7YS2-06T-001_1"))
    )
    (comp (ref "LED152")
      (value "F.0603.00106/P2-0603W7YS2-06T-001")
      (fields (field (name "Manufacturer") "TUOZHAN(拓展光电)"))
      (libsource (lib "") (part "F.0603.00106/P2-0603W7YS2-06T-001_1"))
    )
    (comp (ref "LED153")
      (value "F.0603.00106/P2-0603W7YS2-06T-001")
      (fields (field (name "Manufacturer") "TUOZHAN(拓展光电)"))
      (libsource (lib "") (part "F.0603.00106/P2-0603W7YS2-06T-001_1"))
    )
    (comp (ref "LED154")
      (value "F.0603.00106/P2-0603W7YS2-06T-001")
      (fields (field (name "Manufacturer") "TUOZHAN(拓展光电)"))
      (libsource (lib "") (part "F.0603.00106/P2-0603W7YS2-06T-001_1"))
    )
    (comp (ref "LED155")
      (value "F.0603.00106/P2-0603W7YS2-06T-001")
      (fields (field (name "Manufacturer") "TUOZHAN(拓展光电)"))
      (libsource (lib "") (part "F.0603.00106/P2-0603W7YS2-06T-001_1"))
    )
    (comp (ref "LED156")
      (value "F.0603.00106/P2-0603W7YS2-06T-001")
      (fields (field (name "Manufacturer") "TUOZHAN(拓展光电)"))
      (libsource (lib "") (part "F.0603.00106/P2-0603W7YS2-06T-001_1"))
    )
    (comp (ref "LED157")
      (value "F.0603.00106/P2-0603W7YS2-06T-001")
      (fields (field (name "Manufacturer") "TUOZHAN(拓展光电)"))
      (libsource (lib "") (part "F.0603.00106/P2-0603W7YS2-06T-001_1"))
    )
    (comp (ref "LED158")
      (value "F.0603.00106/P2-0603W7YS2-06T-001")
      (fields (field (name "Manufacturer") "TUOZHAN(拓展光电)"))
      (libsource (lib "") (part "F.0603.00106/P2-0603W7YS2-06T-001_1"))
    )
    (comp (ref "LED159")
      (value "F.0603.00106/P2-0603W7YS2-06T-001")
      (fields (field (name "Manufacturer") "TUOZHAN(拓展光电)"))
      (libsource (lib "") (part "F.0603.00106/P2-0603W7YS2-06T-001_1"))
    )
    (comp (ref "LED160")
      (value "F.0603.00106/P2-0603W7YS2-06T-001")
      (fields (field (name "Manufacturer") "TUOZHAN(拓展光电)"))
      (libsource (lib "") (part "F.0603.00106/P2-0603W7YS2-06T-001_1"))
    )
    (comp (ref "LED161")
      (value "F.0603.00106/P2-0603W7YS2-06T-001")
      (fields (field (name "Manufacturer") "TUOZHAN(拓展光电)"))
      (libsource (lib "") (part "F.0603.00106/P2-0603W7YS2-06T-001"))
    )
    (comp (ref "LED162")
      (value "F.0603.00106/P2-0603W7YS2-06T-001")
      (fields (field (name "Manufacturer") "TUOZHAN(拓展光电)"))
      (libsource (lib "") (part "F.0603.00106/P2-0603W7YS2-06T-001"))
    )
    (comp (ref "LED163")
      (value "F.0603.00106/P2-0603W7YS2-06T-001")
      (fields (field (name "Manufacturer") "TUOZHAN(拓展光电)"))
      (libsource (lib "") (part "F.0603.00106/P2-0603W7YS2-06T-001"))
    )
    (comp (ref "LED164")
      (value "F.0603.00106/P2-0603W7YS2-06T-001")
      (fields (field (name "Manufacturer") "TUOZHAN(拓展光电)"))
      (libsource (lib "") (part "F.0603.00106/P2-0603W7YS2-06T-001"))
    )
    (comp (ref "LED165")
      (value "F.0603.00106/P2-0603W7YS2-06T-001")
      (fields (field (name "Manufacturer") "TUOZHAN(拓展光电)"))
      (libsource (lib "") (part "F.0603.00106/P2-0603W7YS2-06T-001"))
    )
    (comp (ref "LED166")
      (value "F.0603.00106/P2-0603W7YS2-06T-001")
      (fields (field (name "Manufacturer") "TUOZHAN(拓展光电)"))
      (libsource (lib "") (part "F.0603.00106/P2-0603W7YS2-06T-001"))
    )
    (comp (ref "LED167")
      (value "F.0603.00106/P2-0603W7YS2-06T-001")
      (fields (field (name "Manufacturer") "TUOZHAN(拓展光电)"))
      (libsource (lib "") (part "F.0603.00106/P2-0603W7YS2-06T-001"))
    )
    (comp (ref "LED168")
      (value "F.0603.00106/P2-0603W7YS2-06T-001")
      (fields (field (name "Manufacturer") "TUOZHAN(拓展光电)"))
      (libsource (lib "") (part "F.0603.00106/P2-0603W7YS2-06T-001"))
    )
    (comp (ref "LED169")
      (value "F.0603.00106/P2-0603W7YS2-06T-001")
      (fields (field (name "Manufacturer") "TUOZHAN(拓展光电)"))
      (libsource (lib "") (part "F.0603.00106/P2-0603W7YS2-06T-001"))
    )
    (comp (ref "LED170")
      (value "F.0603.00106/P2-0603W7YS2-06T-001")
      (fields (field (name "Manufacturer") "TUOZHAN(拓展光电)"))
      (libsource (lib "") (part "F.0603.00106/P2-0603W7YS2-06T-001"))
    )
    (comp (ref "LED171")
      (value "F.0603.00106/P2-0603W7YS2-06T-001")
      (fields (field (name "Manufacturer") "TUOZHAN(拓展光电)"))
      (libsource (lib "") (part "F.0603.00106/P2-0603W7YS2-06T-001"))
    )
    (comp (ref "LED172")
      (value "F.0603.00106/P2-0603W7YS2-06T-001")
      (fields (field (name "Manufacturer") "TUOZHAN(拓展光电)"))
      (libsource (lib "") (part "F.0603.00106/P2-0603W7YS2-06T-001"))
    )
    (comp (ref "LED173")
      (value "F.0603.00106/P2-0603W7YS2-06T-001")
      (fields (field (name "Manufacturer") "TUOZHAN(拓展光电)"))
      (libsource (lib "") (part "F.0603.00106/P2-0603W7YS2-06T-001"))
    )
    (comp (ref "LED174")
      (value "F.0603.00106/P2-0603W7YS2-06T-001")
      (fields (field (name "Manufacturer") "TUOZHAN(拓展光电)"))
      (libsource (lib "") (part "F.0603.00106/P2-0603W7YS2-06T-001"))
    )
    (comp (ref "LED175")
      (value "F.0603.00106/P2-0603W7YS2-06T-001")
      (fields (field (name "Manufacturer") "TUOZHAN(拓展光电)"))
      (libsource (lib "") (part "F.0603.00106/P2-0603W7YS2-06T-001"))
    )
    (comp (ref "LED176")
      (value "F.0603.00106/P2-0603W7YS2-06T-001")
      (fields (field (name "Manufacturer") "TUOZHAN(拓展光电)"))
      (libsource (lib "") (part "F.0603.00106/P2-0603W7YS2-06T-001"))
    )
    (comp (ref "LED177")
      (value "F.0603.00106/P2-0603W7YS2-06T-001")
      (fields (field (name "Manufacturer") "TUOZHAN(拓展光电)"))
      (libsource (lib "") (part "F.0603.00106/P2-0603W7YS2-06T-001"))
    )
    (comp (ref "LED178")
      (value "F.0603.00106/P2-0603W7YS2-06T-001")
      (fields (field (name "Manufacturer") "TUOZHAN(拓展光电)"))
      (libsource (lib "") (part "F.0603.00106/P2-0603W7YS2-06T-001"))
    )
    (comp (ref "LED179")
      (value "F.0603.00106/P2-0603W7YS2-06T-001")
      (fields (field (name "Manufacturer") "TUOZHAN(拓展光电)"))
      (libsource (lib "") (part "F.0603.00106/P2-0603W7YS2-06T-001"))
    )
    (comp (ref "LED180")
      (value "F.0603.00106/P2-0603W7YS2-06T-001")
      (fields (field (name "Manufacturer") "TUOZHAN(拓展光电)"))
      (libsource (lib "") (part "F.0603.00106/P2-0603W7YS2-06T-001"))
    )
    (comp (ref "LED181")
      (value "F.0603.00106/P2-0603W7YS2-06T-001")
      (fields (field (name "Manufacturer") "TUOZHAN(拓展光电)"))
      (libsource (lib "") (part "F.0603.00106/P2-0603W7YS2-06T-001"))
    )
    (comp (ref "LED182")
      (value "F.0603.00106/P2-0603W7YS2-06T-001")
      (fields (field (name "Manufacturer") "TUOZHAN(拓展光电)"))
      (libsource (lib "") (part "F.0603.00106/P2-0603W7YS2-06T-001"))
    )
    (comp (ref "LED183")
      (value "F.0603.00106/P2-0603W7YS2-06T-001")
      (fields (field (name "Manufacturer") "TUOZHAN(拓展光电)"))
      (libsource (lib "") (part "F.0603.00106/P2-0603W7YS2-06T-001"))
    )
    (comp (ref "LED184")
      (value "F.0603.00106/P2-0603W7YS2-06T-001")
      (fields (field (name "Manufacturer") "TUOZHAN(拓展光电)"))
      (libsource (lib "") (part "F.0603.00106/P2-0603W7YS2-06T-001"))
    )
    (comp (ref "LED185")
      (value "F.0603.00106/P2-0603W7YS2-06T-001")
      (fields (field (name "Manufacturer") "TUOZHAN(拓展光电)"))
      (libsource (lib "") (part "F.0603.00106/P2-0603W7YS2-06T-001"))
    )
    (comp (ref "LED186")
      (value "F.0603.00106/P2-0603W7YS2-06T-001")
      (fields (field (name "Manufacturer") "TUOZHAN(拓展光电)"))
      (libsource (lib "") (part "F.0603.00106/P2-0603W7YS2-06T-001"))
    )
    (comp (ref "LED187")
      (value "F.0603.00106/P2-0603W7YS2-06T-001")
      (fields (field (name "Manufacturer") "TUOZHAN(拓展光电)"))
      (libsource (lib "") (part "F.0603.00106/P2-0603W7YS2-06T-001"))
    )
    (comp (ref "LED188")
      (value "F.0603.00106/P2-0603W7YS2-06T-001")
      (fields (field (name "Manufacturer") "TUOZHAN(拓展光电)"))
      (libsource (lib "") (part "F.0603.00106/P2-0603W7YS2-06T-001"))
    )
    (comp (ref "LED189")
      (value "F.0603.00106/P2-0603W7YS2-06T-001")
      (fields (field (name "Manufacturer") "TUOZHAN(拓展光电)"))
      (libsource (lib "") (part "F.0603.00106/P2-0603W7YS2-06T-001"))
    )
    (comp (ref "LED190")
      (value "F.0603.00106/P2-0603W7YS2-06T-001")
      (fields (field (name "Manufacturer") "TUOZHAN(拓展光电)"))
      (libsource (lib "") (part "F.0603.00106/P2-0603W7YS2-06T-001"))
    )
    (comp (ref "LED191")
      (value "F.0603.00106/P2-0603W7YS2-06T-001")
      (fields (field (name "Manufacturer") "TUOZHAN(拓展光电)"))
      (libsource (lib "") (part "F.0603.00106/P2-0603W7YS2-06T-001"))
    )
    (comp (ref "LED192")
      (value "F.0603.00106/P2-0603W7YS2-06T-001")
      (fields (field (name "Manufacturer") "TUOZHAN(拓展光电)"))
      (libsource (lib "") (part "F.0603.00106/P2-0603W7YS2-06T-001"))
    )
    (comp (ref "LED193")
      (value "F.0603.00106/P2-0603W7YS2-06T-001")
      (fields (field (name "Manufacturer") "TUOZHAN(拓展光电)"))
      (libsource (lib "") (part "F.0603.00106/P2-0603W7YS2-06T-001_1"))
    )
    (comp (ref "LED194")
      (value "F.0603.00106/P2-0603W7YS2-06T-001")
      (fields (field (name "Manufacturer") "TUOZHAN(拓展光电)"))
      (libsource (lib "") (part "F.0603.00106/P2-0603W7YS2-06T-001_1"))
    )
    (comp (ref "LED195")
      (value "F.0603.00106/P2-0603W7YS2-06T-001")
      (fields (field (name "Manufacturer") "TUOZHAN(拓展光电)"))
      (libsource (lib "") (part "F.0603.00106/P2-0603W7YS2-06T-001_1"))
    )
    (comp (ref "LED196")
      (value "F.0603.00106/P2-0603W7YS2-06T-001")
      (fields (field (name "Manufacturer") "TUOZHAN(拓展光电)"))
      (libsource (lib "") (part "F.0603.00106/P2-0603W7YS2-06T-001_1"))
    )
    (comp (ref "LED197")
      (value "F.0603.00106/P2-0603W7YS2-06T-001")
      (fields (field (name "Manufacturer") "TUOZHAN(拓展光电)"))
      (libsource (lib "") (part "F.0603.00106/P2-0603W7YS2-06T-001_1"))
    )
    (comp (ref "LED198")
      (value "F.0603.00106/P2-0603W7YS2-06T-001")
      (fields (field (name "Manufacturer") "TUOZHAN(拓展光电)"))
      (libsource (lib "") (part "F.0603.00106/P2-0603W7YS2-06T-001_1"))
    )
    (comp (ref "LED199")
      (value "F.0603.00106/P2-0603W7YS2-06T-001")
      (fields (field (name "Manufacturer") "TUOZHAN(拓展光电)"))
      (libsource (lib "") (part "F.0603.00106/P2-0603W7YS2-06T-001_1"))
    )
    (comp (ref "LED200")
      (value "F.0603.00106/P2-0603W7YS2-06T-001")
      (fields (field (name "Manufacturer") "TUOZHAN(拓展光电)"))
      (libsource (lib "") (part "F.0603.00106/P2-0603W7YS2-06T-001_1"))
    )
    (comp (ref "LED201")
      (value "F.0603.00106/P2-0603W7YS2-06T-001")
      (fields (field (name "Manufacturer") "TUOZHAN(拓展光电)"))
      (libsource (lib "") (part "F.0603.00106/P2-0603W7YS2-06T-001_1"))
    )
    (comp (ref "LED202")
      (value "F.0603.00106/P2-0603W7YS2-06T-001")
      (fields (field (name "Manufacturer") "TUOZHAN(拓展光电)"))
      (libsource (lib "") (part "F.0603.00106/P2-0603W7YS2-06T-001_1"))
    )
    (comp (ref "LED203")
      (value "F.0603.00106/P2-0603W7YS2-06T-001")
      (fields (field (name "Manufacturer") "TUOZHAN(拓展光电)"))
      (libsource (lib "") (part "F.0603.00106/P2-0603W7YS2-06T-001_1"))
    )
    (comp (ref "LED204")
      (value "F.0603.00106/P2-0603W7YS2-06T-001")
      (fields (field (name "Manufacturer") "TUOZHAN(拓展光电)"))
      (libsource (lib "") (part "F.0603.00106/P2-0603W7YS2-06T-001_1"))
    )
    (comp (ref "LED205")
      (value "F.0603.00106/P2-0603W7YS2-06T-001")
      (fields (field (name "Manufacturer") "TUOZHAN(拓展光电)"))
      (libsource (lib "") (part "F.0603.00106/P2-0603W7YS2-06T-001_1"))
    )
    (comp (ref "LED206")
      (value "F.0603.00106/P2-0603W7YS2-06T-001")
      (fields (field (name "Manufacturer") "TUOZHAN(拓展光电)"))
      (libsource (lib "") (part "F.0603.00106/P2-0603W7YS2-06T-001_1"))
    )
    (comp (ref "LED207")
      (value "F.0603.00106/P2-0603W7YS2-06T-001")
      (fields (field (name "Manufacturer") "TUOZHAN(拓展光电)"))
      (libsource (lib "") (part "F.0603.00106/P2-0603W7YS2-06T-001_1"))
    )
    (comp (ref "LED208")
      (value "F.0603.00106/P2-0603W7YS2-06T-001")
      (fields (field (name "Manufacturer") "TUOZHAN(拓展光电)"))
      (libsource (lib "") (part "F.0603.00106/P2-0603W7YS2-06T-001_1"))
    )
    (comp (ref "LED209")
      (value "F.0603.00106/P2-0603W7YS2-06T-001")
      (fields (field (name "Manufacturer") "TUOZHAN(拓展光电)"))
      (libsource (lib "") (part "F.0603.00106/P2-0603W7YS2-06T-001_1"))
    )
    (comp (ref "LED210")
      (value "F.0603.00106/P2-0603W7YS2-06T-001")
      (fields (field (name "Manufacturer") "TUOZHAN(拓展光电)"))
      (libsource (lib "") (part "F.0603.00106/P2-0603W7YS2-06T-001_1"))
    )
    (comp (ref "LED211")
      (value "F.0603.00106/P2-0603W7YS2-06T-001")
      (fields (field (name "Manufacturer") "TUOZHAN(拓展光电)"))
      (libsource (lib "") (part "F.0603.00106/P2-0603W7YS2-06T-001_1"))
    )
    (comp (ref "LED212")
      (value "F.0603.00106/P2-0603W7YS2-06T-001")
      (fields (field (name "Manufacturer") "TUOZHAN(拓展光电)"))
      (libsource (lib "") (part "F.0603.00106/P2-0603W7YS2-06T-001_1"))
    )
    (comp (ref "LED213")
      (value "F.0603.00106/P2-0603W7YS2-06T-001")
      (fields (field (name "Manufacturer") "TUOZHAN(拓展光电)"))
      (libsource (lib "") (part "F.0603.00106/P2-0603W7YS2-06T-001_1"))
    )
    (comp (ref "LED214")
      (value "F.0603.00106/P2-0603W7YS2-06T-001")
      (fields (field (name "Manufacturer") "TUOZHAN(拓展光电)"))
      (libsource (lib "") (part "F.0603.00106/P2-0603W7YS2-06T-001_1"))
    )
    (comp (ref "LED215")
      (value "F.0603.00106/P2-0603W7YS2-06T-001")
      (fields (field (name "Manufacturer") "TUOZHAN(拓展光电)"))
      (libsource (lib "") (part "F.0603.00106/P2-0603W7YS2-06T-001_1"))
    )
    (comp (ref "LED216")
      (value "F.0603.00106/P2-0603W7YS2-06T-001")
      (fields (field (name "Manufacturer") "TUOZHAN(拓展光电)"))
      (libsource (lib "") (part "F.0603.00106/P2-0603W7YS2-06T-001_1"))
    )
    (comp (ref "LED217")
      (value "F.0603.00106/P2-0603W7YS2-06T-001")
      (fields (field (name "Manufacturer") "TUOZHAN(拓展光电)"))
      (libsource (lib "") (part "F.0603.00106/P2-0603W7YS2-06T-001_1"))
    )
    (comp (ref "LED218")
      (value "F.0603.00106/P2-0603W7YS2-06T-001")
      (fields (field (name "Manufacturer") "TUOZHAN(拓展光电)"))
      (libsource (lib "") (part "F.0603.00106/P2-0603W7YS2-06T-001_1"))
    )
    (comp (ref "LED219")
      (value "F.0603.00106/P2-0603W7YS2-06T-001")
      (fields (field (name "Manufacturer") "TUOZHAN(拓展光电)"))
      (libsource (lib "") (part "F.0603.00106/P2-0603W7YS2-06T-001_1"))
    )
    (comp (ref "LED220")
      (value "F.0603.00106/P2-0603W7YS2-06T-001")
      (fields (field (name "Manufacturer") "TUOZHAN(拓展光电)"))
      (libsource (lib "") (part "F.0603.00106/P2-0603W7YS2-06T-001_1"))
    )
    (comp (ref "LED221")
      (value "F.0603.00106/P2-0603W7YS2-06T-001")
      (fields (field (name "Manufacturer") "TUOZHAN(拓展光电)"))
      (libsource (lib "") (part "F.0603.00106/P2-0603W7YS2-06T-001_1"))
    )
    (comp (ref "LED222")
      (value "F.0603.00106/P2-0603W7YS2-06T-001")
      (fields (field (name "Manufacturer") "TUOZHAN(拓展光电)"))
      (libsource (lib "") (part "F.0603.00106/P2-0603W7YS2-06T-001_1"))
    )
    (comp (ref "LED223")
      (value "F.0603.00106/P2-0603W7YS2-06T-001")
      (fields (field (name "Manufacturer") "TUOZHAN(拓展光电)"))
      (libsource (lib "") (part "F.0603.00106/P2-0603W7YS2-06T-001_1"))
    )
    (comp (ref "LED224")
      (value "F.0603.00106/P2-0603W7YS2-06T-001")
      (fields (field (name "Manufacturer") "TUOZHAN(拓展光电)"))
      (libsource (lib "") (part "F.0603.00106/P2-0603W7YS2-06T-001_1"))
    )
    (comp (ref "LED225")
      (value "F.0603.00106/P2-0603W7YS2-06T-001")
      (fields (field (name "Manufacturer") "TUOZHAN(拓展光电)"))
      (libsource (lib "") (part "F.0603.00106/P2-0603W7YS2-06T-001"))
    )
    (comp (ref "LED226")
      (value "F.0603.00106/P2-0603W7YS2-06T-001")
      (fields (field (name "Manufacturer") "TUOZHAN(拓展光电)"))
      (libsource (lib "") (part "F.0603.00106/P2-0603W7YS2-06T-001"))
    )
    (comp (ref "LED227")
      (value "F.0603.00106/P2-0603W7YS2-06T-001")
      (fields (field (name "Manufacturer") "TUOZHAN(拓展光电)"))
      (libsource (lib "") (part "F.0603.00106/P2-0603W7YS2-06T-001"))
    )
    (comp (ref "LED228")
      (value "F.0603.00106/P2-0603W7YS2-06T-001")
      (fields (field (name "Manufacturer") "TUOZHAN(拓展光电)"))
      (libsource (lib "") (part "F.0603.00106/P2-0603W7YS2-06T-001"))
    )
    (comp (ref "LED229")
      (value "F.0603.00106/P2-0603W7YS2-06T-001")
      (fields (field (name "Manufacturer") "TUOZHAN(拓展光电)"))
      (libsource (lib "") (part "F.0603.00106/P2-0603W7YS2-06T-001"))
    )
    (comp (ref "LED230")
      (value "F.0603.00106/P2-0603W7YS2-06T-001")
      (fields (field (name "Manufacturer") "TUOZHAN(拓展光电)"))
      (libsource (lib "") (part "F.0603.00106/P2-0603W7YS2-06T-001"))
    )
    (comp (ref "LED231")
      (value "F.0603.00106/P2-0603W7YS2-06T-001")
      (fields (field (name "Manufacturer") "TUOZHAN(拓展光电)"))
      (libsource (lib "") (part "F.0603.00106/P2-0603W7YS2-06T-001"))
    )
    (comp (ref "LED232")
      (value "F.0603.00106/P2-0603W7YS2-06T-001")
      (fields (field (name "Manufacturer") "TUOZHAN(拓展光电)"))
      (libsource (lib "") (part "F.0603.00106/P2-0603W7YS2-06T-001"))
    )
    (comp (ref "LED233")
      (value "F.0603.00106/P2-0603W7YS2-06T-001")
      (fields (field (name "Manufacturer") "TUOZHAN(拓展光电)"))
      (libsource (lib "") (part "F.0603.00106/P2-0603W7YS2-06T-001"))
    )
    (comp (ref "LED234")
      (value "F.0603.00106/P2-0603W7YS2-06T-001")
      (fields (field (name "Manufacturer") "TUOZHAN(拓展光电)"))
      (libsource (lib "") (part "F.0603.00106/P2-0603W7YS2-06T-001"))
    )
    (comp (ref "LED235")
      (value "F.0603.00106/P2-0603W7YS2-06T-001")
      (fields (field (name "Manufacturer") "TUOZHAN(拓展光电)"))
      (libsource (lib "") (part "F.0603.00106/P2-0603W7YS2-06T-001"))
    )
    (comp (ref "LED236")
      (value "F.0603.00106/P2-0603W7YS2-06T-001")
      (fields (field (name "Manufacturer") "TUOZHAN(拓展光电)"))
      (libsource (lib "") (part "F.0603.00106/P2-0603W7YS2-06T-001"))
    )
    (comp (ref "LED237")
      (value "F.0603.00106/P2-0603W7YS2-06T-001")
      (fields (field (name "Manufacturer") "TUOZHAN(拓展光电)"))
      (libsource (lib "") (part "F.0603.00106/P2-0603W7YS2-06T-001"))
    )
    (comp (ref "LED238")
      (value "F.0603.00106/P2-0603W7YS2-06T-001")
      (fields (field (name "Manufacturer") "TUOZHAN(拓展光电)"))
      (libsource (lib "") (part "F.0603.00106/P2-0603W7YS2-06T-001"))
    )
    (comp (ref "LED239")
      (value "F.0603.00106/P2-0603W7YS2-06T-001")
      (fields (field (name "Manufacturer") "TUOZHAN(拓展光电)"))
      (libsource (lib "") (part "F.0603.00106/P2-0603W7YS2-06T-001"))
    )
    (comp (ref "LED240")
      (value "F.0603.00106/P2-0603W7YS2-06T-001")
      (fields (field (name "Manufacturer") "TUOZHAN(拓展光电)"))
      (libsource (lib "") (part "F.0603.00106/P2-0603W7YS2-06T-001"))
    )
    (comp (ref "LED241")
      (value "F.0603.00106/P2-0603W7YS2-06T-001")
      (fields (field (name "Manufacturer") "TUOZHAN(拓展光电)"))
      (libsource (lib "") (part "F.0603.00106/P2-0603W7YS2-06T-001"))
    )
    (comp (ref "LED242")
      (value "F.0603.00106/P2-0603W7YS2-06T-001")
      (fields (field (name "Manufacturer") "TUOZHAN(拓展光电)"))
      (libsource (lib "") (part "F.0603.00106/P2-0603W7YS2-06T-001"))
    )
    (comp (ref "LED243")
      (value "F.0603.00106/P2-0603W7YS2-06T-001")
      (fields (field (name "Manufacturer") "TUOZHAN(拓展光电)"))
      (libsource (lib "") (part "F.0603.00106/P2-0603W7YS2-06T-001"))
    )
    (comp (ref "LED244")
      (value "F.0603.00106/P2-0603W7YS2-06T-001")
      (fields (field (name "Manufacturer") "TUOZHAN(拓展光电)"))
      (libsource (lib "") (part "F.0603.00106/P2-0603W7YS2-06T-001"))
    )
    (comp (ref "LED245")
      (value "F.0603.00106/P2-0603W7YS2-06T-001")
      (fields (field (name "Manufacturer") "TUOZHAN(拓展光电)"))
      (libsource (lib "") (part "F.0603.00106/P2-0603W7YS2-06T-001"))
    )
    (comp (ref "LED246")
      (value "F.0603.00106/P2-0603W7YS2-06T-001")
      (fields (field (name "Manufacturer") "TUOZHAN(拓展光电)"))
      (libsource (lib "") (part "F.0603.00106/P2-0603W7YS2-06T-001"))
    )
    (comp (ref "LED247")
      (value "F.0603.00106/P2-0603W7YS2-06T-001")
      (fields (field (name "Manufacturer") "TUOZHAN(拓展光电)"))
      (libsource (lib "") (part "F.0603.00106/P2-0603W7YS2-06T-001"))
    )
    (comp (ref "LED248")
      (value "F.0603.00106/P2-0603W7YS2-06T-001")
      (fields (field (name "Manufacturer") "TUOZHAN(拓展光电)"))
      (libsource (lib "") (part "F.0603.00106/P2-0603W7YS2-06T-001"))
    )
    (comp (ref "LED249")
      (value "F.0603.00106/P2-0603W7YS2-06T-001")
      (fields (field (name "Manufacturer") "TUOZHAN(拓展光电)"))
      (libsource (lib "") (part "F.0603.00106/P2-0603W7YS2-06T-001"))
    )
    (comp (ref "LED250")
      (value "F.0603.00106/P2-0603W7YS2-06T-001")
      (fields (field (name "Manufacturer") "TUOZHAN(拓展光电)"))
      (libsource (lib "") (part "F.0603.00106/P2-0603W7YS2-06T-001"))
    )
    (comp (ref "LED251")
      (value "F.0603.00106/P2-0603W7YS2-06T-001")
      (fields (field (name "Manufacturer") "TUOZHAN(拓展光电)"))
      (libsource (lib "") (part "F.0603.00106/P2-0603W7YS2-06T-001"))
    )
    (comp (ref "LED252")
      (value "F.0603.00106/P2-0603W7YS2-06T-001")
      (fields (field (name "Manufacturer") "TUOZHAN(拓展光电)"))
      (libsource (lib "") (part "F.0603.00106/P2-0603W7YS2-06T-001"))
    )
    (comp (ref "LED253")
      (value "F.0603.00106/P2-0603W7YS2-06T-001")
      (fields (field (name "Manufacturer") "TUOZHAN(拓展光电)"))
      (libsource (lib "") (part "F.0603.00106/P2-0603W7YS2-06T-001"))
    )
    (comp (ref "LED254")
      (value "F.0603.00106/P2-0603W7YS2-06T-001")
      (fields (field (name "Manufacturer") "TUOZHAN(拓展光电)"))
      (libsource (lib "") (part "F.0603.00106/P2-0603W7YS2-06T-001"))
    )
    (comp (ref "LED255")
      (value "F.0603.00106/P2-0603W7YS2-06T-001")
      (fields (field (name "Manufacturer") "TUOZHAN(拓展光电)"))
      (libsource (lib "") (part "F.0603.00106/P2-0603W7YS2-06T-001"))
    )
    (comp (ref "LED256")
      (value "F.0603.00106/P2-0603W7YS2-06T-001")
      (fields (field (name "Manufacturer") "TUOZHAN(拓展光电)"))
      (libsource (lib "") (part "F.0603.00106/P2-0603W7YS2-06T-001"))
    )
    (comp (ref "R1")
      (value "15kΩ")
      (fields
        (field (name "Manufacturer Part") "0603WAF1502T5E")
        (field (name "Manufacturer") "UNI-ROYAL(厚声)")
      )
      (libsource (lib "") (part "0603WAF1502T5E"))
    )
    (comp (ref "R2")
      (value "15kΩ")
      (fields
        (field (name "Manufacturer Part") "0603WAF1502T5E")
        (field (name "Manufacturer") "UNI-ROYAL(厚声)")
      )
      (libsource (lib "") (part "0603WAF1502T5E"))
    )
    (comp (ref "R3")
      (value "15kΩ")
      (fields
        (field (name "Manufacturer Part") "0603WAF1502T5E")
        (field (name "Manufacturer") "UNI-ROYAL(厚声)")
      )
      (libsource (lib "") (part "0603WAF1502T5E"))
    )
    (comp (ref "R4")
      (value "15kΩ")
      (fields
        (field (name "Manufacturer Part") "0603WAF1502T5E")
        (field (name "Manufacturer") "UNI-ROYAL(厚声)")
      )
      (libsource (lib "") (part "0603WAF1502T5E"))
    )
    (comp (ref "R5")
      (value "15kΩ")
      (fields
        (field (name "Manufacturer Part") "0603WAF1502T5E")
        (field (name "Manufacturer") "UNI-ROYAL(厚声)")
      )
      (libsource (lib "") (part "0603WAF1502T5E"))
    )
    (comp (ref "R6")
      (value "15kΩ")
      (fields
        (field (name "Manufacturer Part") "0603WAF1502T5E")
        (field (name "Manufacturer") "UNI-ROYAL(厚声)")
      )
      (libsource (lib "") (part "0603WAF1502T5E"))
    )
    (comp (ref "R7")
      (value "15kΩ")
      (fields
        (field (name "Manufacturer Part") "0603WAF1502T5E")
        (field (name "Manufacturer") "UNI-ROYAL(厚声)")
      )
      (libsource (lib "") (part "0603WAF1502T5E"))
    )
    (comp (ref "R8")
      (value "15kΩ")
      (fields
        (field (name "Manufacturer Part") "0603WAF1502T5E")
        (field (name "Manufacturer") "UNI-ROYAL(厚声)")
      )
      (libsource (lib "") (part "0603WAF1502T5E"))
    )
    (comp (ref "R9")
      (value "15kΩ")
      (fields
        (field (name "Manufacturer Part") "0603WAF1502T5E")
        (field (name "Manufacturer") "UNI-ROYAL(厚声)")
      )
      (libsource (lib "") (part "0603WAF1502T5E"))
    )
    (comp (ref "R10")
      (value "15kΩ")
      (fields
        (field (name "Manufacturer Part") "0603WAF1502T5E")
        (field (name "Manufacturer") "UNI-ROYAL(厚声)")
      )
      (libsource (lib "") (part "0603WAF1502T5E"))
    )
    (comp (ref "R11")
      (value "15kΩ")
      (fields
        (field (name "Manufacturer Part") "0603WAF1502T5E")
        (field (name "Manufacturer") "UNI-ROYAL(厚声)")
      )
      (libsource (lib "") (part "0603WAF1502T5E"))
    )
    (comp (ref "R12")
      (value "15kΩ")
      (fields
        (field (name "Manufacturer Part") "0603WAF1502T5E")
        (field (name "Manufacturer") "UNI-ROYAL(厚声)")
      )
      (libsource (lib "") (part "0603WAF1502T5E"))
    )
    (comp (ref "R13")
      (value "15kΩ")
      (fields
        (field (name "Manufacturer Part") "0603WAF1502T5E")
        (field (name "Manufacturer") "UNI-ROYAL(厚声)")
      )
      (libsource (lib "") (part "0603WAF1502T5E"))
    )
    (comp (ref "R14")
      (value "15kΩ")
      (fields
        (field (name "Manufacturer Part") "0603WAF1502T5E")
        (field (name "Manufacturer") "UNI-ROYAL(厚声)")
      )
      (libsource (lib "") (part "0603WAF1502T5E"))
    )
    (comp (ref "R15")
      (value "15kΩ")
      (fields
        (field (name "Manufacturer Part") "0603WAF1502T5E")
        (field (name "Manufacturer") "UNI-ROYAL(厚声)")
      )
      (libsource (lib "") (part "0603WAF1502T5E"))
    )
    (comp (ref "R16")
      (value "15kΩ")
      (fields
        (field (name "Manufacturer Part") "0603WAF1502T5E")
        (field (name "Manufacturer") "UNI-ROYAL(厚声)")
      )
      (libsource (lib "") (part "0603WAF1502T5E"))
    )
    (comp (ref "U1")
      (value "-")
      (fields (field (name "Manufacturer Part") "TLC59283DBQR") (field (name "Manufacturer") "TI(德州仪器)"))
      (libsource (lib "") (part "TLC59283DBQR"))
    )
    (comp (ref "U2")
      (value "-")
      (fields (field (name "Manufacturer Part") "TLC59283DBQR") (field (name "Manufacturer") "TI(德州仪器)"))
      (libsource (lib "") (part "TLC59283DBQR"))
    )
    (comp (ref "U3")
      (value "-")
      (fields (field (name "Manufacturer Part") "TLC59283DBQR") (field (name "Manufacturer") "TI(德州仪器)"))
      (libsource (lib "") (part "TLC59283DBQR"))
    )
    (comp (ref "U4")
      (value "-")
      (fields (field (name "Manufacturer Part") "TLC59283DBQR") (field (name "Manufacturer") "TI(德州仪器)"))
      (libsource (lib "") (part "TLC59283DBQR"))
    )
    (comp (ref "U5")
      (value "-")
      (fields (field (name "Manufacturer Part") "TLC59283DBQR") (field (name "Manufacturer") "TI(德州仪器)"))
      (libsource (lib "") (part "TLC59283DBQR"))
    )
    (comp (ref "U6")
      (value "-")
      (fields (field (name "Manufacturer Part") "TLC59283DBQR") (field (name "Manufacturer") "TI(德州仪器)"))
      (libsource (lib "") (part "TLC59283DBQR"))
    )
    (comp (ref "U7")
      (value "-")
      (fields (field (name "Manufacturer Part") "TLC59283DBQR") (field (name "Manufacturer") "TI(德州仪器)"))
      (libsource (lib "") (part "TLC59283DBQR"))
    )
    (comp (ref "U8")
      (value "-")
      (fields (field (name "Manufacturer Part") "TLC59283DBQR") (field (name "Manufacturer") "TI(德州仪器)"))
      (libsource (lib "") (part "TLC59283DBQR"))
    )
    (comp (ref "U9")
      (value "-")
      (fields (field (name "Manufacturer Part") "TLC59283DBQR") (field (name "Manufacturer") "TI(德州仪器)"))
      (libsource (lib "") (part "TLC59283DBQR"))
    )
    (comp (ref "U10")
      (value "-")
      (fields (field (name "Manufacturer Part") "TLC59283DBQR") (field (name "Manufacturer") "TI(德州仪器)"))
      (libsource (lib "") (part "TLC59283DBQR"))
    )
    (comp (ref "U11")
      (value "-")
      (fields (field (name "Manufacturer Part") "TLC59283DBQR") (field (name "Manufacturer") "TI(德州仪器)"))
      (libsource (lib "") (part "TLC59283DBQR"))
    )
    (comp (ref "U12")
      (value "-")
      (fields (field (name "Manufacturer Part") "TLC59283DBQR") (field (name "Manufacturer") "TI(德州仪器)"))
      (libsource (lib "") (part "TLC59283DBQR"))
    )
    (comp (ref "U13")
      (value "-")
      (fields (field (name "Manufacturer Part") "TLC59283DBQR") (field (name "Manufacturer") "TI(德州仪器)"))
      (libsource (lib "") (part "TLC59283DBQR"))
    )
    (comp (ref "U14")
      (value "-")
      (fields (field (name "Manufacturer Part") "TLC59283DBQR") (field (name "Manufacturer") "TI(德州仪器)"))
      (libsource (lib "") (part "TLC59283DBQR"))
    )
    (comp (ref "U15")
      (value "-")
      (fields (field (name "Manufacturer Part") "TLC59283DBQR") (field (name "Manufacturer") "TI(德州仪器)"))
      (libsource (lib "") (part "TLC59283DBQR"))
    )
    (comp (ref "U16")
      (value "-")
      (fields (field (name "Manufacturer Part") "TLC59283DBQR") (field (name "Manufacturer") "TI(德州仪器)"))
      (libsource (lib "") (part "TLC59283DBQR"))
    )
  )
  (nets
    (net (code "1") (name "BLANK") (class "Default")
      (node (ref "U1") (pin "21") (pinfunction "BLANK_21") (pintype "unspecified"))
      (node (ref "U10") (pin "21") (pinfunction "BLANK_21") (pintype "unspecified"))
      (node (ref "U11") (pin "21") (pinfunction "BLANK_21") (pintype "unspecified"))
      (node (ref "U12") (pin "21") (pinfunction "BLANK_21") (pintype "unspecified"))
      (node (ref "U13") (pin "21") (pinfunction "BLANK_21") (pintype "unspecified"))
      (node (ref "U14") (pin "21") (pinfunction "BLANK_21") (pintype "unspecified"))
      (node (ref "U15") (pin "21") (pinfunction "BLANK_21") (pintype "unspecified"))
      (node (ref "U16") (pin "21") (pinfunction "BLANK_21") (pintype "unspecified"))
      (node (ref "U2") (pin "21") (pinfunction "BLANK_21") (pintype "unspecified"))
      (node (ref "U3") (pin "21") (pinfunction "BLANK_21") (pintype "unspecified"))
      (node (ref "U4") (pin "21") (pinfunction "BLANK_21") (pintype "unspecified"))
      (node (ref "U5") (pin "21") (pinfunction "BLANK_21") (pintype "unspecified"))
      (node (ref "U6") (pin "21") (pinfunction "BLANK_21") (pintype "unspecified"))
      (node (ref "U7") (pin "21") (pinfunction "BLANK_21") (pintype "unspecified"))
      (node (ref "U8") (pin "21") (pinfunction "BLANK_21") (pintype "unspecified"))
      (node (ref "U9") (pin "21") (pinfunction "BLANK_21") (pintype "unspecified"))
    )
    (net (code "2") (name "GND") (class "Default")
      (node (ref "C1") (pin "2") (pinfunction "2_2") (pintype "unspecified"))
      (node (ref "C10") (pin "2") (pinfunction "2_2") (pintype "unspecified"))
      (node (ref "C11") (pin "2") (pinfunction "2_2") (pintype "unspecified"))
      (node (ref "C12") (pin "2") (pinfunction "2_2") (pintype "unspecified"))
      (node (ref "C13") (pin "2") (pinfunction "2_2") (pintype "unspecified"))
      (node (ref "C14") (pin "2") (pinfunction "2_2") (pintype "unspecified"))
      (node (ref "C15") (pin "2") (pinfunction "2_2") (pintype "unspecified"))
      (node (ref "C16") (pin "2") (pinfunction "2_2") (pintype "unspecified"))
      (node (ref "C17") (pin "1") (pinfunction "1_1") (pintype "unspecified"))
      (node (ref "C18") (pin "1") (pinfunction "1_1") (pintype "unspecified"))
      (node (ref "C19") (pin "1") (pinfunction "1_1") (pintype "unspecified"))
      (node (ref "C2") (pin "2") (pinfunction "2_2") (pintype "unspecified"))
      (node (ref "C20") (pin "1") (pinfunction "1_1") (pintype "unspecified"))
      (node (ref "C21") (pin "1") (pinfunction "1_1") (pintype "unspecified"))
      (node (ref "C22") (pin "1") (pinfunction "1_1") (pintype "unspecified"))
      (node (ref "C23") (pin "1") (pinfunction "1_1") (pintype "unspecified"))
      (node (ref "C24") (pin "1") (pinfunction "1_1") (pintype "unspecified"))
      (node (ref "C3") (pin "2") (pinfunction "2_2") (pintype "unspecified"))
      (node (ref "C4") (pin "2") (pinfunction "2_2") (pintype "unspecified"))
      (node (ref "C5") (pin "2") (pinfunction "2_2") (pintype "unspecified"))
      (node (ref "C6") (pin "2") (pinfunction "2_2") (pintype "unspecified"))
      (node (ref "C7") (pin "2") (pinfunction "2_2") (pintype "unspecified"))
      (node (ref "C8") (pin "2") (pinfunction "2_2") (pintype "unspecified"))
      (node (ref "C9") (pin "2") (pinfunction "2_2") (pintype "unspecified"))
      (node (ref "R1") (pin "2") (pinfunction "2_2") (pintype "input"))
      (node (ref "R10") (pin "2") (pinfunction "2_2") (pintype "input"))
      (node (ref "R11") (pin "2") (pinfunction "2_2") (pintype "input"))
      (node (ref "R12") (pin "2") (pinfunction "2_2") (pintype "input"))
      (node (ref "R13") (pin "2") (pinfunction "2_2") (pintype "input"))
      (node (ref "R14") (pin "2") (pinfunction "2_2") (pintype "input"))
      (node (ref "R15") (pin "2") (pinfunction "2_2") (pintype "input"))
      (node (ref "R16") (pin "2") (pinfunction "2_2") (pintype "input"))
      (node (ref "R2") (pin "2") (pinfunction "2_2") (pintype "input"))
      (node (ref "R3") (pin "2") (pinfunction "2_2") (pintype "input"))
      (node (ref "R4") (pin "2") (pinfunction "2_2") (pintype "input"))
      (node (ref "R5") (pin "2") (pinfunction "2_2") (pintype "input"))
      (node (ref "R6") (pin "2") (pinfunction "2_2") (pintype "input"))
      (node (ref "R7") (pin "2") (pinfunction "2_2") (pintype "input"))
      (node (ref "R8") (pin "2") (pinfunction "2_2") (pintype "input"))
      (node (ref "R9") (pin "2") (pinfunction "2_2") (pintype "input"))
      (node (ref "U1") (pin "1") (pinfunction "GND_1") (pintype "unspecified"))
      (node (ref "U10") (pin "1") (pinfunction "GND_1") (pintype "unspecified"))
      (node (ref "U11") (pin "1") (pinfunction "GND_1") (pintype "unspecified"))
      (node (ref "U12") (pin "1") (pinfunction "GND_1") (pintype "unspecified"))
      (node (ref "U13") (pin "1") (pinfunction "GND_1") (pintype "unspecified"))
      (node (ref "U14") (pin "1") (pinfunction "GND_1") (pintype "unspecified"))
      (node (ref "U15") (pin "1") (pinfunction "GND_1") (pintype "unspecified"))
      (node (ref "U16") (pin "1") (pinfunction "GND_1") (pintype "unspecified"))
      (node (ref "U2") (pin "1") (pinfunction "GND_1") (pintype "unspecified"))
      (node (ref "U3") (pin "1") (pinfunction "GND_1") (pintype "unspecified"))
      (node (ref "U4") (pin "1") (pinfunction "GND_1") (pintype "unspecified"))
      (node (ref "U5") (pin "1") (pinfunction "GND_1") (pintype "unspecified"))
      (node (ref "U6") (pin "1") (pinfunction "GND_1") (pintype "unspecified"))
      (node (ref "U7") (pin "1") (pinfunction "GND_1") (pintype "unspecified"))
      (node (ref "U8") (pin "1") (pinfunction "GND_1") (pintype "unspecified"))
      (node (ref "U9") (pin "1") (pinfunction "GND_1") (pintype "unspecified"))
    )
    (net (code "3") (name "LAT") (class "Default")
      (node (ref "U1") (pin "4") (pinfunction "LAT_4") (pintype "unspecified"))
      (node (ref "U10") (pin "4") (pinfunction "LAT_4") (pintype "unspecified"))
      (node (ref "U11") (pin "4") (pinfunction "LAT_4") (pintype "unspecified"))
      (node (ref "U12") (pin "4") (pinfunction "LAT_4") (pintype "unspecified"))
      (node (ref "U13") (pin "4") (pinfunction "LAT_4") (pintype "unspecified"))
      (node (ref "U14") (pin "4") (pinfunction "LAT_4") (pintype "unspecified"))
      (node (ref "U15") (pin "4") (pinfunction "LAT_4") (pintype "unspecified"))
      (node (ref "U16") (pin "4") (pinfunction "LAT_4") (pintype "unspecified"))
      (node (ref "U2") (pin "4") (pinfunction "LAT_4") (pintype "unspecified"))
      (node (ref "U3") (pin "4") (pinfunction "LAT_4") (pintype "unspecified"))
      (node (ref "U4") (pin "4") (pinfunction "LAT_4") (pintype "unspecified"))
      (node (ref "U5") (pin "4") (pinfunction "LAT_4") (pintype "unspecified"))
      (node (ref "U6") (pin "4") (pinfunction "LAT_4") (pintype "unspecified"))
      (node (ref "U7") (pin "4") (pinfunction "LAT_4") (pintype "unspecified"))
      (node (ref "U8") (pin "4") (pinfunction "LAT_4") (pintype "unspecified"))
      (node (ref "U9") (pin "4") (pinfunction "LAT_4") (pintype "unspecified"))
    )
    (net (code "4") (name "Net-(LED1-K)") (class "Default")
      (node (ref "LED1") (pin "1") (pinfunction "K_1") (pintype "unspecified"))
      (node (ref "U1") (pin "20") (pinfunction "OUT15_20") (pintype "unspecified"))
    )
    (net (code "5") (name "Net-(LED2-K)") (class "Default")
      (node (ref "LED2") (pin "1") (pinfunction "K_1") (pintype "unspecified"))
      (node (ref "U1") (pin "19") (pinfunction "OUT14_19") (pintype "unspecified"))
    )
    (net (code "6") (name "Net-(LED3-K)") (class "Default")
      (node (ref "LED3") (pin "1") (pinfunction "K_1") (pintype "unspecified"))
      (node (ref "U1") (pin "18") (pinfunction "OUT13_18") (pintype "unspecified"))
    )
    (net (code "7") (name "Net-(LED4-K)") (class "Default")
      (node (ref "LED4") (pin "1") (pinfunction "K_1") (pintype "unspecified"))
      (node (ref "U1") (pin "17") (pinfunction "OUT12_17") (pintype "unspecified"))
    )
    (net (code "8") (name "Net-(LED5-K)") (class "Default")
      (node (ref "LED5") (pin "1") (pinfunction "K_1") (pintype "unspecified"))
      (node (ref "U1") (pin "16") (pinfunction "OUT11_16") (pintype "unspecified"))
    )
    (net (code "9") (name "Net-(LED6-K)") (class "Default")
      (node (ref "LED6") (pin "1") (pinfunction "K_1") (pintype "unspecified"))
      (node (ref "U1") (pin "15") (pinfunction "OUT10_15") (pintype "unspecified"))
    )
    (net (code "10") (name "Net-(LED7-K)") (class "Default")
      (node (ref "LED7") (pin "1") (pinfunction "K_1") (pintype "unspecified"))
      (node (ref "U1") (pin "14") (pinfunction "OUT9_14") (pintype "unspecified"))
    )
    (net (code "11") (name "Net-(LED8-K)") (class "Default")
      (node (ref "LED8") (pin "1") (pinfunction "K_1") (pintype "unspecified"))
      (node (ref "U1") (pin "13") (pinfunction "OUT8_13") (pintype "unspecified"))
    )
    (net (code "12") (name "Net-(LED9-K)") (class "Default")
      (node (ref "LED9") (pin "1") (pinfunction "K_1") (pintype "unspecified"))
      (node (ref "U2") (pin "20") (pinfunction "OUT15_20") (pintype "unspecified"))
    )
    (net (code "13") (name "Net-(LED10-K)") (class "Default")
      (node (ref "LED10") (pin "1") (pinfunction "K_1") (pintype "unspecified"))
      (node (ref "U2") (pin "19") (pinfunction "OUT14_19") (pintype "unspecified"))
    )
    (net (code "14") (name "Net-(LED11-K)") (class "Default")
      (node (ref "LED11") (pin "1") (pinfunction "K_1") (pintype "unspecified"))
      (node (ref "U2") (pin "18") (pinfunction "OUT13_18") (pintype "unspecified"))
    )
    (net (code "15") (name "Net-(LED12-K)") (class "Default")
      (node (ref "LED12") (pin "1") (pinfunction "K_1") (pintype "unspecified"))
      (node (ref "U2") (pin "17") (pinfunction "OUT12_17") (pintype "unspecified"))
    )
    (net (code "16") (name "Net-(LED13-K)") (class "Default")
      (node (ref "LED13") (pin "1") (pinfunction "K_1") (pintype "unspecified"))
      (node (ref "U2") (pin "16") (pinfunction "OUT11_16") (pintype "unspecified"))
    )
    (net (code "17") (name "Net-(LED14-K)") (class "Default")
      (node (ref "LED14") (pin "1") (pinfunction "K_1") (pintype "unspecified"))
      (node (ref "U2") (pin "15") (pinfunction "OUT10_15") (pintype "unspecified"))
    )
    (net (code "18") (name "Net-(LED15-K)") (class "Default")
      (node (ref "LED15") (pin "1") (pinfunction "K_1") (pintype "unspecified"))
      (node (ref "U2") (pin "14") (pinfunction "OUT9_14") (pintype "unspecified"))
    )
    (net (code "19") (name "Net-(LED16-K)") (class "Default")
      (node (ref "LED16") (pin "1") (pinfunction "K_1") (pintype "unspecified"))
      (node (ref "U2") (pin "13") (pinfunction "OUT8_13") (pintype "unspecified"))
    )
    (net (code "20") (name "Net-(LED17-K)") (class "Default")
      (node (ref "LED17") (pin "1") (pinfunction "K_1") (pintype "unspecified"))
      (node (ref "U3") (pin "20") (pinfunction "OUT15_20") (pintype "unspecified"))
    )
    (net (code "21") (name "Net-(LED18-K)") (class "Default")
      (node (ref "LED18") (pin "1") (pinfunction "K_1") (pintype "unspecified"))
      (node (ref "U3") (pin "19") (pinfunction "OUT14_19") (pintype "unspecified"))
    )
    (net (code "22") (name "Net-(LED19-K)") (class "Default")
      (node (ref "LED19") (pin "1") (pinfunction "K_1") (pintype "unspecified"))
      (node (ref "U3") (pin "18") (pinfunction "OUT13_18") (pintype "unspecified"))
    )
    (net (code "23") (name "Net-(LED20-K)") (class "Default")
      (node (ref "LED20") (pin "1") (pinfunction "K_1") (pintype "unspecified"))
      (node (ref "U3") (pin "17") (pinfunction "OUT12_17") (pintype "unspecified"))
    )
    (net (code "24") (name "Net-(LED21-K)") (class "Default")
      (node (ref "LED21") (pin "1") (pinfunction "K_1") (pintype "unspecified"))
      (node (ref "U3") (pin "16") (pinfunction "OUT11_16") (pintype "unspecified"))
    )
    (net (code "25") (name "Net-(LED22-K)") (class "Default")
      (node (ref "LED22") (pin "1") (pinfunction "K_1") (pintype "unspecified"))
      (node (ref "U3") (pin "15") (pinfunction "OUT10_15") (pintype "unspecified"))
    )
    (net (code "26") (name "Net-(LED23-K)") (class "Default")
      (node (ref "LED23") (pin "1") (pinfunction "K_1") (pintype "unspecified"))
      (node (ref "U3") (pin "14") (pinfunction "OUT9_14") (pintype "unspecified"))
    )
    (net (code "27") (name "Net-(LED24-K)") (class "Default")
      (node (ref "LED24") (pin "1") (pinfunction "K_1") (pintype "unspecified"))
      (node (ref "U3") (pin "13") (pinfunction "OUT8_13") (pintype "unspecified"))
    )
    (net (code "28") (name "Net-(LED25-K)") (class "Default")
      (node (ref "LED25") (pin "1") (pinfunction "K_1") (pintype "unspecified"))
      (node (ref "U4") (pin "20") (pinfunction "OUT15_20") (pintype "unspecified"))
    )
    (net (code "29") (name "Net-(LED26-K)") (class "Default")
      (node (ref "LED26") (pin "1") (pinfunction "K_1") (pintype "unspecified"))
      (node (ref "U4") (pin "19") (pinfunction "OUT14_19") (pintype "unspecified"))
    )
    (net (code "30") (name "Net-(LED27-K)") (class "Default")
      (node (ref "LED27") (pin "1") (pinfunction "K_1") (pintype "unspecified"))
      (node (ref "U4") (pin "18") (pinfunction "OUT13_18") (pintype "unspecified"))
    )
    (net (code "31") (name "Net-(LED28-K)") (class "Default")
      (node (ref "LED28") (pin "1") (pinfunction "K_1") (pintype "unspecified"))
      (node (ref "U4") (pin "17") (pinfunction "OUT12_17") (pintype "unspecified"))
    )
    (net (code "32") (name "Net-(LED29-K)") (class "Default")
      (node (ref "LED29") (pin "1") (pinfunction "K_1") (pintype "unspecified"))
      (node (ref "U4") (pin "16") (pinfunction "OUT11_16") (pintype "unspecified"))
    )
    (net (code "33") (name "Net-(LED30-K)") (class "Default")
      (node (ref "LED30") (pin "1") (pinfunction "K_1") (pintype "unspecified"))
      (node (ref "U4") (pin "15") (pinfunction "OUT10_15") (pintype "unspecified"))
    )
    (net (code "34") (name "Net-(LED31-K)") (class "Default")
      (node (ref "LED31") (pin "1") (pinfunction "K_1") (pintype "unspecified"))
      (node (ref "U4") (pin "14") (pinfunction "OUT9_14") (pintype "unspecified"))
    )
    (net (code "35") (name "Net-(LED32-K)") (class "Default")
      (node (ref "LED32") (pin "1") (pinfunction "K_1") (pintype "unspecified"))
      (node (ref "U4") (pin "13") (pinfunction "OUT8_13") (pintype "unspecified"))
    )
    (net (code "36") (name "Net-(LED33-K)") (class "Default")
      (node (ref "LED33") (pin "1") (pinfunction "K_1") (pintype "unspecified"))
      (node (ref "U1") (pin "5") (pinfunction "OUT0_5") (pintype "unspecified"))
    )
    (net (code "37") (name "Net-(LED34-K)") (class "Default")
      (node (ref "LED34") (pin "1") (pinfunction "K_1") (pintype "unspecified"))
      (node (ref "U1") (pin "6") (pinfunction "OUT1_6") (pintype "unspecified"))
    )
    (net (code "38") (name "Net-(LED35-K)") (class "Default")
      (node (ref "LED35") (pin "1") (pinfunction "K_1") (pintype "unspecified"))
      (node (ref "U1") (pin "7") (pinfunction "OUT2_7") (pintype "unspecified"))
    )
    (net (code "39") (name "Net-(LED36-K)") (class "Default")
      (node (ref "LED36") (pin "1") (pinfunction "K_1") (pintype "unspecified"))
      (node (ref "U1") (pin "8") (pinfunction "OUT3_8") (pintype "unspecified"))
    )
    (net (code "40") (name "Net-(LED37-K)") (class "Default")
      (node (ref "LED37") (pin "1") (pinfunction "K_1") (pintype "unspecified"))
      (node (ref "U1") (pin "9") (pinfunction "OUT4_9") (pintype "unspecified"))
    )
    (net (code "41") (name "Net-(LED38-K)") (class "Default")
      (node (ref "LED38") (pin "1") (pinfunction "K_1") (pintype "unspecified"))
      (node (ref "U1") (pin "10") (pinfunction "OUT5_10") (pintype "unspecified"))
    )
    (net (code "42") (name "Net-(LED39-K)") (class "Default")
      (node (ref "LED39") (pin "1") (pinfunction "K_1") (pintype "unspecified"))
      (node (ref "U1") (pin "11") (pinfunction "OUT6_11") (pintype "unspecified"))
    )
    (net (code "43") (name "Net-(LED40-K)") (class "Default")
      (node (ref "LED40") (pin "1") (pinfunction "K_1") (pintype "unspecified"))
      (node (ref "U1") (pin "12") (pinfunction "OUT7_12") (pintype "unspecified"))
    )
    (net (code "44") (name "Net-(LED41-K)") (class "Default")
      (node (ref "LED41") (pin "1") (pinfunction "K_1") (pintype "unspecified"))
      (node (ref "U2") (pin "5") (pinfunction "OUT0_5") (pintype "unspecified"))
    )
    (net (code "45") (name "Net-(LED42-K)") (class "Default")
      (node (ref "LED42") (pin "1") (pinfunction "K_1") (pintype "unspecified"))
      (node (ref "U2") (pin "6") (pinfunction "OUT1_6") (pintype "unspecified"))
    )
    (net (code "46") (name "Net-(LED43-K)") (class "Default")
      (node (ref "LED43") (pin "1") (pinfunction "K_1") (pintype "unspecified"))
      (node (ref "U2") (pin "7") (pinfunction "OUT2_7") (pintype "unspecified"))
    )
    (net (code "47") (name "Net-(LED44-K)") (class "Default")
      (node (ref "LED44") (pin "1") (pinfunction "K_1") (pintype "unspecified"))
      (node (ref "U2") (pin "8") (pinfunction "OUT3_8") (pintype "unspecified"))
    )
    (net (code "48") (name "Net-(LED45-K)") (class "Default")
      (node (ref "LED45") (pin "1") (pinfunction "K_1") (pintype "unspecified"))
      (node (ref "U2") (pin "9") (pinfunction "OUT4_9") (pintype "unspecified"))
    )
    (net (code "49") (name "Net-(LED46-K)") (class "Default")
      (node (ref "LED46") (pin "1") (pinfunction "K_1") (pintype "unspecified"))
      (node (ref "U2") (pin "10") (pinfunction "OUT5_10") (pintype "unspecified"))
    )
    (net (code "50") (name "Net-(LED47-K)") (class "Default")
      (node (ref "LED47") (pin "1") (pinfunction "K_1") (pintype "unspecified"))
      (node (ref "U2") (pin "11") (pinfunction "OUT6_11") (pintype "unspecified"))
    )
    (net (code "51") (name "Net-(LED48-K)") (class "Default")
      (node (ref "LED48") (pin "1") (pinfunction "K_1") (pintype "unspecified"))
      (node (ref "U2") (pin "12") (pinfunction "OUT7_12") (pintype "unspecified"))
    )
    (net (code "52") (name "Net-(LED49-K)") (class "Default")
      (node (ref "LED49") (pin "1") (pinfunction "K_1") (pintype "unspecified"))
      (node (ref "U3") (pin "5") (pinfunction "OUT0_5") (pintype "unspecified"))
    )
    (net (code "53") (name "Net-(LED50-K)") (class "Default")
      (node (ref "LED50") (pin "1") (pinfunction "K_1") (pintype "unspecified"))
      (node (ref "U3") (pin "6") (pinfunction "OUT1_6") (pintype "unspecified"))
    )
    (net (code "54") (name "Net-(LED51-K)") (class "Default")
      (node (ref "LED51") (pin "1") (pinfunction "K_1") (pintype "unspecified"))
      (node (ref "U3") (pin "7") (pinfunction "OUT2_7") (pintype "unspecified"))
    )
    (net (code "55") (name "Net-(LED52-K)") (class "Default")
      (node (ref "LED52") (pin "1") (pinfunction "K_1") (pintype "unspecified"))
      (node (ref "U3") (pin "8") (pinfunction "OUT3_8") (pintype "unspecified"))
    )
    (net (code "56") (name "Net-(LED53-K)") (class "Default")
      (node (ref "LED53") (pin "1") (pinfunction "K_1") (pintype "unspecified"))
      (node (ref "U3") (pin "9") (pinfunction "OUT4_9") (pintype "unspecified"))
    )
    (net (code "57") (name "Net-(LED54-K)") (class "Default")
      (node (ref "LED54") (pin "1") (pinfunction "K_1") (pintype "unspecified"))
      (node (ref "U3") (pin "10") (pinfunction "OUT5_10") (pintype "unspecified"))
    )
    (net (code "58") (name "Net-(LED55-K)") (class "Default")
      (node (ref "LED55") (pin "1") (pinfunction "K_1") (pintype "unspecified"))
      (node (ref "U3") (pin "11") (pinfunction "OUT6_11") (pintype "unspecified"))
    )
    (net (code "59") (name "Net-(LED56-K)") (class "Default")
      (node (ref "LED56") (pin "1") (pinfunction "K_1") (pintype "unspecified"))
      (node (ref "U3") (pin "12") (pinfunction "OUT7_12") (pintype "unspecified"))
    )
    (net (code "60") (name "Net-(LED57-K)") (class "Default")
      (node (ref "LED57") (pin "1") (pinfunction "K_1") (pintype "unspecified"))
      (node (ref "U4") (pin "5") (pinfunction "OUT0_5") (pintype "unspecified"))
    )
    (net (code "61") (name "Net-(LED58-K)") (class "Default")
      (node (ref "LED58") (pin "1") (pinfunction "K_1") (pintype "unspecified"))
      (node (ref "U4") (pin "6") (pinfunction "OUT1_6") (pintype "unspecified"))
    )
    (net (code "62") (name "Net-(LED59-K)") (class "Default")
      (node (ref "LED59") (pin "1") (pinfunction "K_1") (pintype "unspecified"))
      (node (ref "U4") (pin "7") (pinfunction "OUT2_7") (pintype "unspecified"))
    )
    (net (code "63") (name "Net-(LED60-K)") (class "Default")
      (node (ref "LED60") (pin "1") (pinfunction "K_1") (pintype "unspecified"))
      (node (ref "U4") (pin "8") (pinfunction "OUT3_8") (pintype "unspecified"))
    )
    (net (code "64") (name "Net-(LED61-K)") (class "Default")
      (node (ref "LED61") (pin "1") (pinfunction "K_1") (pintype "unspecified"))
      (node (ref "U4") (pin "9") (pinfunction "OUT4_9") (pintype "unspecified"))
    )
    (net (code "65") (name "Net-(LED62-K)") (class "Default")
      (node (ref "LED62") (pin "1") (pinfunction "K_1") (pintype "unspecified"))
      (node (ref "U4") (pin "10") (pinfunction "OUT5_10") (pintype "unspecified"))
    )
    (net (code "66") (name "Net-(LED63-K)") (class "Default")
      (node (ref "LED63") (pin "1") (pinfunction "K_1") (pintype "unspecified"))
      (node (ref "U4") (pin "11") (pinfunction "OUT6_11") (pintype "unspecified"))
    )
    (net (code "67") (name "Net-(LED64-K)") (class "Default")
      (node (ref "LED64") (pin "1") (pinfunction "K_1") (pintype "unspecified"))
      (node (ref "U4") (pin "12") (pinfunction "OUT7_12") (pintype "unspecified"))
    )
    (net (code "68") (name "Net-(LED65-K)") (class "Default")
      (node (ref "LED65") (pin "1") (pinfunction "K_1") (pintype "unspecified"))
      (node (ref "U5") (pin "20") (pinfunction "OUT15_20") (pintype "unspecified"))
    )
    (net (code "69") (name "Net-(LED66-K)") (class "Default")
      (node (ref "LED66") (pin "1") (pinfunction "K_1") (pintype "unspecified"))
      (node (ref "U5") (pin "19") (pinfunction "OUT14_19") (pintype "unspecified"))
    )
    (net (code "70") (name "Net-(LED67-K)") (class "Default")
      (node (ref "LED67") (pin "1") (pinfunction "K_1") (pintype "unspecified"))
      (node (ref "U5") (pin "18") (pinfunction "OUT13_18") (pintype "unspecified"))
    )
    (net (code "71") (name "Net-(LED68-K)") (class "Default")
      (node (ref "LED68") (pin "1") (pinfunction "K_1") (pintype "unspecified"))
      (node (ref "U5") (pin "17") (pinfunction "OUT12_17") (pintype "unspecified"))
    )
    (net (code "72") (name "Net-(LED69-K)") (class "Default")
      (node (ref "LED69") (pin "1") (pinfunction "K_1") (pintype "unspecified"))
      (node (ref "U5") (pin "16") (pinfunction "OUT11_16") (pintype "unspecified"))
    )
    (net (code "73") (name "Net-(LED70-K)") (class "Default")
      (node (ref "LED70") (pin "1") (pinfunction "K_1") (pintype "unspecified"))
      (node (ref "U5") (pin "15") (pinfunction "OUT10_15") (pintype "unspecified"))
    )
    (net (code "74") (name "Net-(LED71-K)") (class "Default")
      (node (ref "LED71") (pin "1") (pinfunction "K_1") (pintype "unspecified"))
      (node (ref "U5") (pin "14") (pinfunction "OUT9_14") (pintype "unspecified"))
    )
    (net (code "75") (name "Net-(LED72-K)") (class "Default")
      (node (ref "LED72") (pin "1") (pinfunction "K_1") (pintype "unspecified"))
      (node (ref "U5") (pin "13") (pinfunction "OUT8_13") (pintype "unspecified"))
    )
    (net (code "76") (name "Net-(LED73-K)") (class "Default")
      (node (ref "LED73") (pin "1") (pinfunction "K_1") (pintype "unspecified"))
      (node (ref "U6") (pin "20") (pinfunction "OUT15_20") (pintype "unspecified"))
    )
    (net (code "77") (name "Net-(LED74-K)") (class "Default")
      (node (ref "LED74") (pin "1") (pinfunction "K_1") (pintype "unspecified"))
      (node (ref "U6") (pin "19") (pinfunction "OUT14_19") (pintype "unspecified"))
    )
    (net (code "78") (name "Net-(LED75-K)") (class "Default")
      (node (ref "LED75") (pin "1") (pinfunction "K_1") (pintype "unspecified"))
      (node (ref "U6") (pin "18") (pinfunction "OUT13_18") (pintype "unspecified"))
    )
    (net (code "79") (name "Net-(LED76-K)") (class "Default")
      (node (ref "LED76") (pin "1") (pinfunction "K_1") (pintype "unspecified"))
      (node (ref "U6") (pin "17") (pinfunction "OUT12_17") (pintype "unspecified"))
    )
    (net (code "80") (name "Net-(LED77-K)") (class "Default")
      (node (ref "LED77") (pin "1") (pinfunction "K_1") (pintype "unspecified"))
      (node (ref "U6") (pin "16") (pinfunction "OUT11_16") (pintype "unspecified"))
    )
    (net (code "81") (name "Net-(LED78-K)") (class "Default")
      (node (ref "LED78") (pin "1") (pinfunction "K_1") (pintype "unspecified"))
      (node (ref "U6") (pin "15") (pinfunction "OUT10_15") (pintype "unspecified"))
    )
    (net (code "82") (name "Net-(LED79-K)") (class "Default")
      (node (ref "LED79") (pin "1") (pinfunction "K_1") (pintype "unspecified"))
      (node (ref "U6") (pin "14") (pinfunction "OUT9_14") (pintype "unspecified"))
    )
    (net (code "83") (name "Net-(LED80-K)") (class "Default")
      (node (ref "LED80") (pin "1") (pinfunction "K_1") (pintype "unspecified"))
      (node (ref "U6") (pin "13") (pinfunction "OUT8_13") (pintype "unspecified"))
    )
    (net (code "84") (name "Net-(LED81-K)") (class "Default")
      (node (ref "LED81") (pin "1") (pinfunction "K_1") (pintype "unspecified"))
      (node (ref "U7") (pin "20") (pinfunction "OUT15_20") (pintype "unspecified"))
    )
    (net (code "85") (name "Net-(LED82-K)") (class "Default")
      (node (ref "LED82") (pin "1") (pinfunction "K_1") (pintype "unspecified"))
      (node (ref "U7") (pin "19") (pinfunction "OUT14_19") (pintype "unspecified"))
    )
    (net (code "86") (name "Net-(LED83-K)") (class "Default")
      (node (ref "LED83") (pin "1") (pinfunction "K_1") (pintype "unspecified"))
      (node (ref "U7") (pin "18") (pinfunction "OUT13_18") (pintype "unspecified"))
    )
    (net (code "87") (name "Net-(LED84-K)") (class "Default")
      (node (ref "LED84") (pin "1") (pinfunction "K_1") (pintype "unspecified"))
      (node (ref "U7") (pin "17") (pinfunction "OUT12_17") (pintype "unspecified"))
    )
    (net (code "88") (name "Net-(LED85-K)") (class "Default")
      (node (ref "LED85") (pin "1") (pinfunction "K_1") (pintype "unspecified"))
      (node (ref "U7") (pin "16") (pinfunction "OUT11_16") (pintype "unspecified"))
    )
    (net (code "89") (name "Net-(LED86-K)") (class "Default")
      (node (ref "LED86") (pin "1") (pinfunction "K_1") (pintype "unspecified"))
      (node (ref "U7") (pin "15") (pinfunction "OUT10_15") (pintype "unspecified"))
    )
    (net (code "90") (name "Net-(LED87-K)") (class "Default")
      (node (ref "LED87") (pin "1") (pinfunction "K_1") (pintype "unspecified"))
      (node (ref "U7") (pin "14") (pinfunction "OUT9_14") (pintype "unspecified"))
    )
    (net (code "91") (name "Net-(LED88-K)") (class "Default")
      (node (ref "LED88") (pin "1") (pinfunction "K_1") (pintype "unspecified"))
      (node (ref "U7") (pin "13") (pinfunction "OUT8_13") (pintype "unspecified"))
    )
    (net (code "92") (name "Net-(LED89-K)") (class "Default")
      (node (ref "LED89") (pin "1") (pinfunction "K_1") (pintype "unspecified"))
      (node (ref "U8") (pin "20") (pinfunction "OUT15_20") (pintype "unspecified"))
    )
    (net (code "93") (name "Net-(LED90-K)") (class "Default")
      (node (ref "LED90") (pin "1") (pinfunction "K_1") (pintype "unspecified"))
      (node (ref "U8") (pin "19") (pinfunction "OUT14_19") (pintype "unspecified"))
    )
    (net (code "94") (name "Net-(LED91-K)") (class "Default")
      (node (ref "LED91") (pin "1") (pinfunction "K_1") (pintype "unspecified"))
      (node (ref "U8") (pin "18") (pinfunction "OUT13_18") (pintype "unspecified"))
    )
    (net (code "95") (name "Net-(LED92-K)") (class "Default")
      (node (ref "LED92") (pin "1") (pinfunction "K_1") (pintype "unspecified"))
      (node (ref "U8") (pin "17") (pinfunction "OUT12_17") (pintype "unspecified"))
    )
    (net (code "96") (name "Net-(LED93-K)") (class "Default")
      (node (ref "LED93") (pin "1") (pinfunction "K_1") (pintype "unspecified"))
      (node (ref "U8") (pin "16") (pinfunction "OUT11_16") (pintype "unspecified"))
    )
    (net (code "97") (name "Net-(LED94-K)") (class "Default")
      (node (ref "LED94") (pin "1") (pinfunction "K_1") (pintype "unspecified"))
      (node (ref "U8") (pin "15") (pinfunction "OUT10_15") (pintype "unspecified"))
    )
    (net (code "98") (name "Net-(LED95-K)") (class "Default")
      (node (ref "LED95") (pin "1") (pinfunction "K_1") (pintype "unspecified"))
      (node (ref "U8") (pin "14") (pinfunction "OUT9_14") (pintype "unspecified"))
    )
    (net (code "99") (name "Net-(LED96-K)") (class "Default")
      (node (ref "LED96") (pin "1") (pinfunction "K_1") (pintype "unspecified"))
      (node (ref "U8") (pin "13") (pinfunction "OUT8_13") (pintype "unspecified"))
    )
    (net (code "100") (name "Net-(LED97-K)") (class "Default")
      (node (ref "LED97") (pin "1") (pinfunction "K_1") (pintype "unspecified"))
      (node (ref "U5") (pin "5") (pinfunction "OUT0_5") (pintype "unspecified"))
    )
    (net (code "101") (name "Net-(LED98-K)") (class "Default")
      (node (ref "LED98") (pin "1") (pinfunction "K_1") (pintype "unspecified"))
      (node (ref "U5") (pin "6") (pinfunction "OUT1_6") (pintype "unspecified"))
    )
    (net (code "102") (name "Net-(LED99-K)") (class "Default")
      (node (ref "LED99") (pin "1") (pinfunction "K_1") (pintype "unspecified"))
      (node (ref "U5") (pin "7") (pinfunction "OUT2_7") (pintype "unspecified"))
    )
    (net (code "103") (name "Net-(LED100-K)") (class "Default")
      (node (ref "LED100") (pin "1") (pinfunction "K_1") (pintype "unspecified"))
      (node (ref "U5") (pin "8") (pinfunction "OUT3_8") (pintype "unspecified"))
    )
    (net (code "104") (name "Net-(LED101-K)") (class "Default")
      (node (ref "LED101") (pin "1") (pinfunction "K_1") (pintype "unspecified"))
      (node (ref "U5") (pin "9") (pinfunction "OUT4_9") (pintype "unspecified"))
    )
    (net (code "105") (name "Net-(LED102-K)") (class "Default")
      (node (ref "LED102") (pin "1") (pinfunction "K_1") (pintype "unspecified"))
      (node (ref "U5") (pin "10") (pinfunction "OUT5_10") (pintype "unspecified"))
    )
    (net (code "106") (name "Net-(LED103-K)") (class "Default")
      (node (ref "LED103") (pin "1") (pinfunction "K_1") (pintype "unspecified"))
      (node (ref "U5") (pin "11") (pinfunction "OUT6_11") (pintype "unspecified"))
    )
    (net (code "107") (name "Net-(LED104-K)") (class "Default")
      (node (ref "LED104") (pin "1") (pinfunction "K_1") (pintype "unspecified"))
      (node (ref "U5") (pin "12") (pinfunction "OUT7_12") (pintype "unspecified"))
    )
    (net (code "108") (name "Net-(LED105-K)") (class "Default")
      (node (ref "LED105") (pin "1") (pinfunction "K_1") (pintype "unspecified"))
      (node (ref "U6") (pin "5") (pinfunction "OUT0_5") (pintype "unspecified"))
    )
    (net (code "109") (name "Net-(LED106-K)") (class "Default")
      (node (ref "LED106") (pin "1") (pinfunction "K_1") (pintype "unspecified"))
      (node (ref "U6") (pin "6") (pinfunction "OUT1_6") (pintype "unspecified"))
    )
    (net (code "110") (name "Net-(LED107-K)") (class "Default")
      (node (ref "LED107") (pin "1") (pinfunction "K_1") (pintype "unspecified"))
      (node (ref "U6") (pin "7") (pinfunction "OUT2_7") (pintype "unspecified"))
    )
    (net (code "111") (name "Net-(LED108-K)") (class "Default")
      (node (ref "LED108") (pin "1") (pinfunction "K_1") (pintype "unspecified"))
      (node (ref "U6") (pin "8") (pinfunction "OUT3_8") (pintype "unspecified"))
    )
    (net (code "112") (name "Net-(LED109-K)") (class "Default")
      (node (ref "LED109") (pin "1") (pinfunction "K_1") (pintype "unspecified"))
      (node (ref "U6") (pin "9") (pinfunction "OUT4_9") (pintype "unspecified"))
    )
    (net (code "113") (name "Net-(LED110-K)") (class "Default")
      (node (ref "LED110") (pin "1") (pinfunction "K_1") (pintype "unspecified"))
      (node (ref "U6") (pin "10") (pinfunction "OUT5_10") (pintype "unspecified"))
    )
    (net (code "114") (name "Net-(LED111-K)") (class "Default")
      (node (ref "LED111") (pin "1") (pinfunction "K_1") (pintype "unspecified"))
      (node (ref "U6") (pin "11") (pinfunction "OUT6_11") (pintype "unspecified"))
    )
    (net (code "115") (name "Net-(LED112-K)") (class "Default")
      (node (ref "LED112") (pin "1") (pinfunction "K_1") (pintype "unspecified"))
      (node (ref "U6") (pin "12") (pinfunction "OUT7_12") (pintype "unspecified"))
    )
    (net (code "116") (name "Net-(LED113-K)") (class "Default")
      (node (ref "LED113") (pin "1") (pinfunction "K_1") (pintype "unspecified"))
      (node (ref "U7") (pin "5") (pinfunction "OUT0_5") (pintype "unspecified"))
    )
    (net (code "117") (name "Net-(LED114-K)") (class "Default")
      (node (ref "LED114") (pin "1") (pinfunction "K_1") (pintype "unspecified"))
      (node (ref "U7") (pin "6") (pinfunction "OUT1_6") (pintype "unspecified"))
    )
    (net (code "118") (name "Net-(LED115-K)") (class "Default")
      (node (ref "LED115") (pin "1") (pinfunction "K_1") (pintype "unspecified"))
      (node (ref "U7") (pin "7") (pinfunction "OUT2_7") (pintype "unspecified"))
    )
    (net (code "119") (name "Net-(LED116-K)") (class "Default")
      (node (ref "LED116") (pin "1") (pinfunction "K_1") (pintype "unspecified"))
      (node (ref "U7") (pin "8") (pinfunction "OUT3_8") (pintype "unspecified"))
    )
    (net (code "120") (name "Net-(LED117-K)") (class "Default")
      (node (ref "LED117") (pin "1") (pinfunction "K_1") (pintype "unspecified"))
      (node (ref "U7") (pin "9") (pinfunction "OUT4_9") (pintype "unspecified"))
    )
    (net (code "121") (name "Net-(LED118-K)") (class "Default")
      (node (ref "LED118") (pin "1") (pinfunction "K_1") (pintype "unspecified"))
      (node (ref "U7") (pin "10") (pinfunction "OUT5_10") (pintype "unspecified"))
    )
    (net (code "122") (name "Net-(LED119-K)") (class "Default")
      (node (ref "LED119") (pin "1") (pinfunction "K_1") (pintype "unspecified"))
      (node (ref "U7") (pin "11") (pinfunction "OUT6_11") (pintype "unspecified"))
    )
    (net (code "123") (name "Net-(LED120-K)") (class "Default")
      (node (ref "LED120") (pin "1") (pinfunction "K_1") (pintype "unspecified"))
      (node (ref "U7") (pin "12") (pinfunction "OUT7_12") (pintype "unspecified"))
    )
    (net (code "124") (name "Net-(LED121-K)") (class "Default")
      (node (ref "LED121") (pin "1") (pinfunction "K_1") (pintype "unspecified"))
      (node (ref "U8") (pin "5") (pinfunction "OUT0_5") (pintype "unspecified"))
    )
    (net (code "125") (name "Net-(LED122-K)") (class "Default")
      (node (ref "LED122") (pin "1") (pinfunction "K_1") (pintype "unspecified"))
      (node (ref "U8") (pin "6") (pinfunction "OUT1_6") (pintype "unspecified"))
    )
    (net (code "126") (name "Net-(LED123-K)") (class "Default")
      (node (ref "LED123") (pin "1") (pinfunction "K_1") (pintype "unspecified"))
      (node (ref "U8") (pin "7") (pinfunction "OUT2_7") (pintype "unspecified"))
    )
    (net (code "127") (name "Net-(LED124-K)") (class "Default")
      (node (ref "LED124") (pin "1") (pinfunction "K_1") (pintype "unspecified"))
      (node (ref "U8") (pin "8") (pinfunction "OUT3_8") (pintype "unspecified"))
    )
    (net (code "128") (name "Net-(LED125-K)") (class "Default")
      (node (ref "LED125") (pin "1") (pinfunction "K_1") (pintype "unspecified"))
      (node (ref "U8") (pin "9") (pinfunction "OUT4_9") (pintype "unspecified"))
    )
    (net (code "129") (name "Net-(LED126-K)") (class "Default")
      (node (ref "LED126") (pin "1") (pinfunction "K_1") (pintype "unspecified"))
      (node (ref "U8") (pin "10") (pinfunction "OUT5_10") (pintype "unspecified"))
    )
    (net (code "130") (name "Net-(LED127-K)") (class "Default")
      (node (ref "LED127") (pin "1") (pinfunction "K_1") (pintype "unspecified"))
      (node (ref "U8") (pin "11") (pinfunction "OUT6_11") (pintype "unspecified"))
    )
    (net (code "131") (name "Net-(LED128-K)") (class "Default")
      (node (ref "LED128") (pin "1") (pinfunction "K_1") (pintype "unspecified"))
      (node (ref "U8") (pin "12") (pinfunction "OUT7_12") (pintype "unspecified"))
    )
    (net (code "132") (name "Net-(LED129-K)") (class "Default")
      (node (ref "LED129") (pin "1") (pinfunction "K_1") (pintype "unspecified"))
      (node (ref "U9") (pin "20") (pinfunction "OUT15_20") (pintype "unspecified"))
    )
    (net (code "133") (name "Net-(LED130-K)") (class "Default")
      (node (ref "LED130") (pin "1") (pinfunction "K_1") (pintype "unspecified"))
      (node (ref "U9") (pin "19") (pinfunction "OUT14_19") (pintype "unspecified"))
    )
    (net (code "134") (name "Net-(LED131-K)") (class "Default")
      (node (ref "LED131") (pin "1") (pinfunction "K_1") (pintype "unspecified"))
      (node (ref "U9") (pin "18") (pinfunction "OUT13_18") (pintype "unspecified"))
    )
    (net (code "135") (name "Net-(LED132-K)") (class "Default")
      (node (ref "LED132") (pin "1") (pinfunction "K_1") (pintype "unspecified"))
      (node (ref "U9") (pin "17") (pinfunction "OUT12_17") (pintype "unspecified"))
    )
    (net (code "136") (name "Net-(LED133-K)") (class "Default")
      (node (ref "LED133") (pin "1") (pinfunction "K_1") (pintype "unspecified"))
      (node (ref "U9") (pin "16") (pinfunction "OUT11_16") (pintype "unspecified"))
    )
    (net (code "137") (name "Net-(LED134-K)") (class "Default")
      (node (ref "LED134") (pin "1") (pinfunction "K_1") (pintype "unspecified"))
      (node (ref "U9") (pin "15") (pinfunction "OUT10_15") (pintype "unspecified"))
    )
    (net (code "138") (name "Net-(LED135-K)") (class "Default")
      (node (ref "LED135") (pin "1") (pinfunction "K_1") (pintype "unspecified"))
      (node (ref "U9") (pin "14") (pinfunction "OUT9_14") (pintype "unspecified"))
    )
    (net (code "139") (name "Net-(LED136-K)") (class "Default")
      (node (ref "LED136") (pin "1") (pinfunction "K_1") (pintype "unspecified"))
      (node (ref "U9") (pin "13") (pinfunction "OUT8_13") (pintype "unspecified"))
    )
    (net (code "140") (name "Net-(LED137-K)") (class "Default")
      (node (ref "LED137") (pin "1") (pinfunction "K_1") (pintype "unspecified"))
      (node (ref "U10") (pin "20") (pinfunction "OUT15_20") (pintype "unspecified"))
    )
    (net (code "141") (name "Net-(LED138-K)") (class "Default")
      (node (ref "LED138") (pin "1") (pinfunction "K_1") (pintype "unspecified"))
      (node (ref "U10") (pin "19") (pinfunction "OUT14_19") (pintype "unspecified"))
    )
    (net (code "142") (name "Net-(LED139-K)") (class "Default")
      (node (ref "LED139") (pin "1") (pinfunction "K_1") (pintype "unspecified"))
      (node (ref "U10") (pin "18") (pinfunction "OUT13_18") (pintype "unspecified"))
    )
    (net (code "143") (name "Net-(LED140-K)") (class "Default")
      (node (ref "LED140") (pin "1") (pinfunction "K_1") (pintype "unspecified"))
      (node (ref "U10") (pin "17") (pinfunction "OUT12_17") (pintype "unspecified"))
    )
    (net (code "144") (name "Net-(LED141-K)") (class "Default")
      (node (ref "LED141") (pin "1") (pinfunction "K_1") (pintype "unspecified"))
      (node (ref "U10") (pin "16") (pinfunction "OUT11_16") (pintype "unspecified"))
    )
    (net (code "145") (name "Net-(LED142-K)") (class "Default")
      (node (ref "LED142") (pin "1") (pinfunction "K_1") (pintype "unspecified"))
      (node (ref "U10") (pin "15") (pinfunction "OUT10_15") (pintype "unspecified"))
    )
    (net (code "146") (name "Net-(LED143-K)") (class "Default")
      (node (ref "LED143") (pin "1") (pinfunction "K_1") (pintype "unspecified"))
      (node (ref "U10") (pin "14") (pinfunction "OUT9_14") (pintype "unspecified"))
    )
    (net (code "147") (name "Net-(LED144-K)") (class "Default")
      (node (ref "LED144") (pin "1") (pinfunction "K_1") (pintype "unspecified"))
      (node (ref "U10") (pin "13") (pinfunction "OUT8_13") (pintype "unspecified"))
    )
    (net (code "148") (name "Net-(LED145-K)") (class "Default")
      (node (ref "LED145") (pin "1") (pinfunction "K_1") (pintype "unspecified"))
      (node (ref "U11") (pin "20") (pinfunction "OUT15_20") (pintype "unspecified"))
    )
    (net (code "149") (name "Net-(LED146-K)") (class "Default")
      (node (ref "LED146") (pin "1") (pinfunction "K_1") (pintype "unspecified"))
      (node (ref "U11") (pin "19") (pinfunction "OUT14_19") (pintype "unspecified"))
    )
    (net (code "150") (name "Net-(LED147-K)") (class "Default")
      (node (ref "LED147") (pin "1") (pinfunction "K_1") (pintype "unspecified"))
      (node (ref "U11") (pin "18") (pinfunction "OUT13_18") (pintype "unspecified"))
    )
    (net (code "151") (name "Net-(LED148-K)") (class "Default")
      (node (ref "LED148") (pin "1") (pinfunction "K_1") (pintype "unspecified"))
      (node (ref "U11") (pin "17") (pinfunction "OUT12_17") (pintype "unspecified"))
    )
    (net (code "152") (name "Net-(LED149-K)") (class "Default")
      (node (ref "LED149") (pin "1") (pinfunction "K_1") (pintype "unspecified"))
      (node (ref "U11") (pin "16") (pinfunction "OUT11_16") (pintype "unspecified"))
    )
    (net (code "153") (name "Net-(LED150-K)") (class "Default")
      (node (ref "LED150") (pin "1") (pinfunction "K_1") (pintype "unspecified"))
      (node (ref "U11") (pin "15") (pinfunction "OUT10_15") (pintype "unspecified"))
    )
    (net (code "154") (name "Net-(LED151-K)") (class "Default")
      (node (ref "LED151") (pin "1") (pinfunction "K_1") (pintype "unspecified"))
      (node (ref "U11") (pin "14") (pinfunction "OUT9_14") (pintype "unspecified"))
    )
    (net (code "155") (name "Net-(LED152-K)") (class "Default")
      (node (ref "LED152") (pin "1") (pinfunction "K_1") (pintype "unspecified"))
      (node (ref "U11") (pin "13") (pinfunction "OUT8_13") (pintype "unspecified"))
    )
    (net (code "156") (name "Net-(LED153-K)") (class "Default")
      (node (ref "LED153") (pin "1") (pinfunction "K_1") (pintype "unspecified"))
      (node (ref "U12") (pin "20") (pinfunction "OUT15_20") (pintype "unspecified"))
    )
    (net (code "157") (name "Net-(LED154-K)") (class "Default")
      (node (ref "LED154") (pin "1") (pinfunction "K_1") (pintype "unspecified"))
      (node (ref "U12") (pin "19") (pinfunction "OUT14_19") (pintype "unspecified"))
    )
    (net (code "158") (name "Net-(LED155-K)") (class "Default")
      (node (ref "LED155") (pin "1") (pinfunction "K_1") (pintype "unspecified"))
      (node (ref "U12") (pin "18") (pinfunction "OUT13_18") (pintype "unspecified"))
    )
    (net (code "159") (name "Net-(LED156-K)") (class "Default")
      (node (ref "LED156") (pin "1") (pinfunction "K_1") (pintype "unspecified"))
      (node (ref "U12") (pin "17") (pinfunction "OUT12_17") (pintype "unspecified"))
    )
    (net (code "160") (name "Net-(LED157-K)") (class "Default")
      (node (ref "LED157") (pin "1") (pinfunction "K_1") (pintype "unspecified"))
      (node (ref "U12") (pin "16") (pinfunction "OUT11_16") (pintype "unspecified"))
    )
    (net (code "161") (name "Net-(LED158-K)") (class "Default")
      (node (ref "LED158") (pin "1") (pinfunction "K_1") (pintype "unspecified"))
      (node (ref "U12") (pin "15") (pinfunction "OUT10_15") (pintype "unspecified"))
    )
    (net (code "162") (name "Net-(LED159-K)") (class "Default")
      (node (ref "LED159") (pin "1") (pinfunction "K_1") (pintype "unspecified"))
      (node (ref "U12") (pin "14") (pinfunction "OUT9_14") (pintype "unspecified"))
    )
    (net (code "163") (name "Net-(LED160-K)") (class "Default")
      (node (ref "LED160") (pin "1") (pinfunction "K_1") (pintype "unspecified"))
      (node (ref "U12") (pin "13") (pinfunction "OUT8_13") (pintype "unspecified"))
    )
    (net (code "164") (name "Net-(LED161-K)") (class "Default")
      (node (ref "LED161") (pin "1") (pinfunction "K_1") (pintype "unspecified"))
      (node (ref "U9") (pin "5") (pinfunction "OUT0_5") (pintype "unspecified"))
    )
    (net (code "165") (name "Net-(LED162-K)") (class "Default")
      (node (ref "LED162") (pin "1") (pinfunction "K_1") (pintype "unspecified"))
      (node (ref "U9") (pin "6") (pinfunction "OUT1_6") (pintype "unspecified"))
    )
    (net (code "166") (name "Net-(LED163-K)") (class "Default")
      (node (ref "LED163") (pin "1") (pinfunction "K_1") (pintype "unspecified"))
      (node (ref "U9") (pin "7") (pinfunction "OUT2_7") (pintype "unspecified"))
    )
    (net (code "167") (name "Net-(LED164-K)") (class "Default")
      (node (ref "LED164") (pin "1") (pinfunction "K_1") (pintype "unspecified"))
      (node (ref "U9") (pin "8") (pinfunction "OUT3_8") (pintype "unspecified"))
    )
    (net (code "168") (name "Net-(LED165-K)") (class "Default")
      (node (ref "LED165") (pin "1") (pinfunction "K_1") (pintype "unspecified"))
      (node (ref "U9") (pin "9") (pinfunction "OUT4_9") (pintype "unspecified"))
    )
    (net (code "169") (name "Net-(LED166-K)") (class "Default")
      (node (ref "LED166") (pin "1") (pinfunction "K_1") (pintype "unspecified"))
      (node (ref "U9") (pin "10") (pinfunction "OUT5_10") (pintype "unspecified"))
    )
    (net (code "170") (name "Net-(LED167-K)") (class "Default")
      (node (ref "LED167") (pin "1") (pinfunction "K_1") (pintype "unspecified"))
      (node (ref "U9") (pin "11") (pinfunction "OUT6_11") (pintype "unspecified"))
    )
    (net (code "171") (name "Net-(LED168-K)") (class "Default")
      (node (ref "LED168") (pin "1") (pinfunction "K_1") (pintype "unspecified"))
      (node (ref "U9") (pin "12") (pinfunction "OUT7_12") (pintype "unspecified"))
    )
    (net (code "172") (name "Net-(LED169-K)") (class "Default")
      (node (ref "LED169") (pin "1") (pinfunction "K_1") (pintype "unspecified"))
      (node (ref "U10") (pin "5") (pinfunction "OUT0_5") (pintype "unspecified"))
    )
    (net (code "173") (name "Net-(LED170-K)") (class "Default")
      (node (ref "LED170") (pin "1") (pinfunction "K_1") (pintype "unspecified"))
      (node (ref "U10") (pin "6") (pinfunction "OUT1_6") (pintype "unspecified"))
    )
    (net (code "174") (name "Net-(LED171-K)") (class "Default")
      (node (ref "LED171") (pin "1") (pinfunction "K_1") (pintype "unspecified"))
      (node (ref "U10") (pin "7") (pinfunction "OUT2_7") (pintype "unspecified"))
    )
    (net (code "175") (name "Net-(LED172-K)") (class "Default")
      (node (ref "LED172") (pin "1") (pinfunction "K_1") (pintype "unspecified"))
      (node (ref "U10") (pin "8") (pinfunction "OUT3_8") (pintype "unspecified"))
    )
    (net (code "176") (name "Net-(LED173-K)") (class "Default")
      (node (ref "LED173") (pin "1") (pinfunction "K_1") (pintype "unspecified"))
      (node (ref "U10") (pin "9") (pinfunction "OUT4_9") (pintype "unspecified"))
    )
    (net (code "177") (name "Net-(LED174-K)") (class "Default")
      (node (ref "LED174") (pin "1") (pinfunction "K_1") (pintype "unspecified"))
      (node (ref "U10") (pin "10") (pinfunction "OUT5_10") (pintype "unspecified"))
    )
    (net (code "178") (name "Net-(LED175-K)") (class "Default")
      (node (ref "LED175") (pin "1") (pinfunction "K_1") (pintype "unspecified"))
      (node (ref "U10") (pin "11") (pinfunction "OUT6_11") (pintype "unspecified"))
    )
    (net (code "179") (name "Net-(LED176-K)") (class "Default")
      (node (ref "LED176") (pin "1") (pinfunction "K_1") (pintype "unspecified"))
      (node (ref "U10") (pin "12") (pinfunction "OUT7_12") (pintype "unspecified"))
    )
    (net (code "180") (name "Net-(LED177-K)") (class "Default")
      (node (ref "LED177") (pin "1") (pinfunction "K_1") (pintype "unspecified"))
      (node (ref "U11") (pin "5") (pinfunction "OUT0_5") (pintype "unspecified"))
    )
    (net (code "181") (name "Net-(LED178-K)") (class "Default")
      (node (ref "LED178") (pin "1") (pinfunction "K_1") (pintype "unspecified"))
      (node (ref "U11") (pin "6") (pinfunction "OUT1_6") (pintype "unspecified"))
    )
    (net (code "182") (name "Net-(LED179-K)") (class "Default")
      (node (ref "LED179") (pin "1") (pinfunction "K_1") (pintype "unspecified"))
      (node (ref "U11") (pin "7") (pinfunction "OUT2_7") (pintype "unspecified"))
    )
    (net (code "183") (name "Net-(LED180-K)") (class "Default")
      (node (ref "LED180") (pin "1") (pinfunction "K_1") (pintype "unspecified"))
      (node (ref "U11") (pin "8") (pinfunction "OUT3_8") (pintype "unspecified"))
    )
    (net (code "184") (name "Net-(LED181-K)") (class "Default")
      (node (ref "LED181") (pin "1") (pinfunction "K_1") (pintype "unspecified"))
      (node (ref "U11") (pin "9") (pinfunction "OUT4_9") (pintype "unspecified"))
    )
    (net (code "185") (name "Net-(LED182-K)") (class "Default")
      (node (ref "LED182") (pin "1") (pinfunction "K_1") (pintype "unspecified"))
      (node (ref "U11") (pin "10") (pinfunction "OUT5_10") (pintype "unspecified"))
    )
    (net (code "186") (name "Net-(LED183-K)") (class "Default")
      (node (ref "LED183") (pin "1") (pinfunction "K_1") (pintype "unspecified"))
      (node (ref "U11") (pin "11") (pinfunction "OUT6_11") (pintype "unspecified"))
    )
    (net (code "187") (name "Net-(LED184-K)") (class "Default")
      (node (ref "LED184") (pin "1") (pinfunction "K_1") (pintype "unspecified"))
      (node (ref "U11") (pin "12") (pinfunction "OUT7_12") (pintype "unspecified"))
    )
    (net (code "188") (name "Net-(LED185-K)") (class "Default")
      (node (ref "LED185") (pin "1") (pinfunction "K_1") (pintype "unspecified"))
      (node (ref "U12") (pin "5") (pinfunction "OUT0_5") (pintype "unspecified"))
    )
    (net (code "189") (name "Net-(LED186-K)") (class "Default")
      (node (ref "LED186") (pin "1") (pinfunction "K_1") (pintype "unspecified"))
      (node (ref "U12") (pin "6") (pinfunction "OUT1_6") (pintype "unspecified"))
    )
    (net (code "190") (name "Net-(LED187-K)") (class "Default")
      (node (ref "LED187") (pin "1") (pinfunction "K_1") (pintype "unspecified"))
      (node (ref "U12") (pin "7") (pinfunction "OUT2_7") (pintype "unspecified"))
    )
    (net (code "191") (name "Net-(LED188-K)") (class "Default")
      (node (ref "LED188") (pin "1") (pinfunction "K_1") (pintype "unspecified"))
      (node (ref "U12") (pin "8") (pinfunction "OUT3_8") (pintype "unspecified"))
    )
    (net (code "192") (name "Net-(LED189-K)") (class "Default")
      (node (ref "LED189") (pin "1") (pinfunction "K_1") (pintype "unspecified"))
      (node (ref "U12") (pin "9") (pinfunction "OUT4_9") (pintype "unspecified"))
    )
    (net (code "193") (name "Net-(LED190-K)") (class "Default")
      (node (ref "LED190") (pin "1") (pinfunction "K_1") (pintype "unspecified"))
      (node (ref "U12") (pin "10") (pinfunction "OUT5_10") (pintype "unspecified"))
    )
    (net (code "194") (name "Net-(LED191-K)") (class "Default")
      (node (ref "LED191") (pin "1") (pinfunction "K_1") (pintype "unspecified"))
      (node (ref "U12") (pin "11") (pinfunction "OUT6_11") (pintype "unspecified"))
    )
    (net (code "195") (name "Net-(LED192-K)") (class "Default")
      (node (ref "LED192") (pin "1") (pinfunction "K_1") (pintype "unspecified"))
      (node (ref "U12") (pin "12") (pinfunction "OUT7_12") (pintype "unspecified"))
    )
    (net (code "196") (name "Net-(LED193-K)") (class "Default")
      (node (ref "LED193") (pin "1") (pinfunction "K_1") (pintype "unspecified"))
      (node (ref "U13") (pin "20") (pinfunction "OUT15_20") (pintype "unspecified"))
    )
    (net (code "197") (name "Net-(LED194-K)") (class "Default")
      (node (ref "LED194") (pin "1") (pinfunction "K_1") (pintype "unspecified"))
      (node (ref "U13") (pin "19") (pinfunction "OUT14_19") (pintype "unspecified"))
    )
    (net (code "198") (name "Net-(LED195-K)") (class "Default")
      (node (ref "LED195") (pin "1") (pinfunction "K_1") (pintype "unspecified"))
      (node (ref "U13") (pin "18") (pinfunction "OUT13_18") (pintype "unspecified"))
    )
    (net (code "199") (name "Net-(LED196-K)") (class "Default")
      (node (ref "LED196") (pin "1") (pinfunction "K_1") (pintype "unspecified"))
      (node (ref "U13") (pin "17") (pinfunction "OUT12_17") (pintype "unspecified"))
    )
    (net (code "200") (name "Net-(LED197-K)") (class "Default")
      (node (ref "LED197") (pin "1") (pinfunction "K_1") (pintype "unspecified"))
      (node (ref "U13") (pin "16") (pinfunction "OUT11_16") (pintype "unspecified"))
    )
    (net (code "201") (name "Net-(LED198-K)") (class "Default")
      (node (ref "LED198") (pin "1") (pinfunction "K_1") (pintype "unspecified"))
      (node (ref "U13") (pin "15") (pinfunction "OUT10_15") (pintype "unspecified"))
    )
    (net (code "202") (name "Net-(LED199-K)") (class "Default")
      (node (ref "LED199") (pin "1") (pinfunction "K_1") (pintype "unspecified"))
      (node (ref "U13") (pin "14") (pinfunction "OUT9_14") (pintype "unspecified"))
    )
    (net (code "203") (name "Net-(LED200-K)") (class "Default")
      (node (ref "LED200") (pin "1") (pinfunction "K_1") (pintype "unspecified"))
      (node (ref "U13") (pin "13") (pinfunction "OUT8_13") (pintype "unspecified"))
    )
    (net (code "204") (name "Net-(LED201-K)") (class "Default")
      (node (ref "LED201") (pin "1") (pinfunction "K_1") (pintype "unspecified"))
      (node (ref "U14") (pin "20") (pinfunction "OUT15_20") (pintype "unspecified"))
    )
    (net (code "205") (name "Net-(LED202-K)") (class "Default")
      (node (ref "LED202") (pin "1") (pinfunction "K_1") (pintype "unspecified"))
      (node (ref "U14") (pin "19") (pinfunction "OUT14_19") (pintype "unspecified"))
    )
    (net (code "206") (name "Net-(LED203-K)") (class "Default")
      (node (ref "LED203") (pin "1") (pinfunction "K_1") (pintype "unspecified"))
      (node (ref "U14") (pin "18") (pinfunction "OUT13_18") (pintype "unspecified"))
    )
    (net (code "207") (name "Net-(LED204-K)") (class "Default")
      (node (ref "LED204") (pin "1") (pinfunction "K_1") (pintype "unspecified"))
      (node (ref "U14") (pin "17") (pinfunction "OUT12_17") (pintype "unspecified"))
    )
    (net (code "208") (name "Net-(LED205-K)") (class "Default")
      (node (ref "LED205") (pin "1") (pinfunction "K_1") (pintype "unspecified"))
      (node (ref "U14") (pin "16") (pinfunction "OUT11_16") (pintype "unspecified"))
    )
    (net (code "209") (name "Net-(LED206-K)") (class "Default")
      (node (ref "LED206") (pin "1") (pinfunction "K_1") (pintype "unspecified"))
      (node (ref "U14") (pin "15") (pinfunction "OUT10_15") (pintype "unspecified"))
    )
    (net (code "210") (name "Net-(LED207-K)") (class "Default")
      (node (ref "LED207") (pin "1") (pinfunction "K_1") (pintype "unspecified"))
      (node (ref "U14") (pin "14") (pinfunction "OUT9_14") (pintype "unspecified"))
    )
    (net (code "211") (name "Net-(LED208-K)") (class "Default")
      (node (ref "LED208") (pin "1") (pinfunction "K_1") (pintype "unspecified"))
      (node (ref "U14") (pin "13") (pinfunction "OUT8_13") (pintype "unspecified"))
    )
    (net (code "212") (name "Net-(LED209-K)") (class "Default")
      (node (ref "LED209") (pin "1") (pinfunction "K_1") (pintype "unspecified"))
      (node (ref "U15") (pin "20") (pinfunction "OUT15_20") (pintype "unspecified"))
    )
    (net (code "213") (name "Net-(LED210-K)") (class "Default")
      (node (ref "LED210") (pin "1") (pinfunction "K_1") (pintype "unspecified"))
      (node (ref "U15") (pin "19") (pinfunction "OUT14_19") (pintype "unspecified"))
    )
    (net (code "214") (name "Net-(LED211-K)") (class "Default")
      (node (ref "LED211") (pin "1") (pinfunction "K_1") (pintype "unspecified"))
      (node (ref "U15") (pin "18") (pinfunction "OUT13_18") (pintype "unspecified"))
    )
    (net (code "215") (name "Net-(LED212-K)") (class "Default")
      (node (ref "LED212") (pin "1") (pinfunction "K_1") (pintype "unspecified"))
      (node (ref "U15") (pin "17") (pinfunction "OUT12_17") (pintype "unspecified"))
    )
    (net (code "216") (name "Net-(LED213-K)") (class "Default")
      (node (ref "LED213") (pin "1") (pinfunction "K_1") (pintype "unspecified"))
      (node (ref "U15") (pin "16") (pinfunction "OUT11_16") (pintype "unspecified"))
    )
    (net (code "217") (name "Net-(LED214-K)") (class "Default")
      (node (ref "LED214") (pin "1") (pinfunction "K_1") (pintype "unspecified"))
      (node (ref "U15") (pin "15") (pinfunction "OUT10_15") (pintype "unspecified"))
    )
    (net (code "218") (name "Net-(LED215-K)") (class "Default")
      (node (ref "LED215") (pin "1") (pinfunction "K_1") (pintype "unspecified"))
      (node (ref "U15") (pin "14") (pinfunction "OUT9_14") (pintype "unspecified"))
    )
    (net (code "219") (name "Net-(LED216-K)") (class "Default")
      (node (ref "LED216") (pin "1") (pinfunction "K_1") (pintype "unspecified"))
      (node (ref "U15") (pin "13") (pinfunction "OUT8_13") (pintype "unspecified"))
    )
    (net (code "220") (name "Net-(LED217-K)") (class "Default")
      (node (ref "LED217") (pin "1") (pinfunction "K_1") (pintype "unspecified"))
      (node (ref "U16") (pin "20") (pinfunction "OUT15_20") (pintype "unspecified"))
    )
    (net (code "221") (name "Net-(LED218-K)") (class "Default")
      (node (ref "LED218") (pin "1") (pinfunction "K_1") (pintype "unspecified"))
      (node (ref "U16") (pin "19") (pinfunction "OUT14_19") (pintype "unspecified"))
    )
    (net (code "222") (name "Net-(LED219-K)") (class "Default")
      (node (ref "LED219") (pin "1") (pinfunction "K_1") (pintype "unspecified"))
      (node (ref "U16") (pin "18") (pinfunction "OUT13_18") (pintype "unspecified"))
    )
    (net (code "223") (name "Net-(LED220-K)") (class "Default")
      (node (ref "LED220") (pin "1") (pinfunction "K_1") (pintype "unspecified"))
      (node (ref "U16") (pin "17") (pinfunction "OUT12_17") (pintype "unspecified"))
    )
    (net (code "224") (name "Net-(LED221-K)") (class "Default")
      (node (ref "LED221") (pin "1") (pinfunction "K_1") (pintype "unspecified"))
      (node (ref "U16") (pin "16") (pinfunction "OUT11_16") (pintype "unspecified"))
    )
    (net (code "225") (name "Net-(LED222-K)") (class "Default")
      (node (ref "LED222") (pin "1") (pinfunction "K_1") (pintype "unspecified"))
      (node (ref "U16") (pin "15") (pinfunction "OUT10_15") (pintype "unspecified"))
    )
    (net (code "226") (name "Net-(LED223-K)") (class "Default")
      (node (ref "LED223") (pin "1") (pinfunction "K_1") (pintype "unspecified"))
      (node (ref "U16") (pin "14") (pinfunction "OUT9_14") (pintype "unspecified"))
    )
    (net (code "227") (name "Net-(LED224-K)") (class "Default")
      (node (ref "LED224") (pin "1") (pinfunction "K_1") (pintype "unspecified"))
      (node (ref "U16") (pin "13") (pinfunction "OUT8_13") (pintype "unspecified"))
    )
    (net (code "228") (name "Net-(LED225-K)") (class "Default")
      (node (ref "LED225") (pin "1") (pinfunction "K_1") (pintype "unspecified"))
      (node (ref "U13") (pin "5") (pinfunction "OUT0_5") (pintype "unspecified"))
    )
    (net (code "229") (name "Net-(LED226-K)") (class "Default")
      (node (ref "LED226") (pin "1") (pinfunction "K_1") (pintype "unspecified"))
      (node (ref "U13") (pin "6") (pinfunction "OUT1_6") (pintype "unspecified"))
    )
    (net (code "230") (name "Net-(LED227-K)") (class "Default")
      (node (ref "LED227") (pin "1") (pinfunction "K_1") (pintype "unspecified"))
      (node (ref "U13") (pin "7") (pinfunction "OUT2_7") (pintype "unspecified"))
    )
    (net (code "231") (name "Net-(LED228-K)") (class "Default")
      (node (ref "LED228") (pin "1") (pinfunction "K_1") (pintype "unspecified"))
      (node (ref "U13") (pin "8") (pinfunction "OUT3_8") (pintype "unspecified"))
    )
    (net (code "232") (name "Net-(LED229-K)") (class "Default")
      (node (ref "LED229") (pin "1") (pinfunction "K_1") (pintype "unspecified"))
      (node (ref "U13") (pin "9") (pinfunction "OUT4_9") (pintype "unspecified"))
    )
    (net (code "233") (name "Net-(LED230-K)") (class "Default")
      (node (ref "LED230") (pin "1") (pinfunction "K_1") (pintype "unspecified"))
      (node (ref "U13") (pin "10") (pinfunction "OUT5_10") (pintype "unspecified"))
    )
    (net (code "234") (name "Net-(LED231-K)") (class "Default")
      (node (ref "LED231") (pin "1") (pinfunction "K_1") (pintype "unspecified"))
      (node (ref "U13") (pin "11") (pinfunction "OUT6_11") (pintype "unspecified"))
    )
    (net (code "235") (name "Net-(LED232-K)") (class "Default")
      (node (ref "LED232") (pin "1") (pinfunction "K_1") (pintype "unspecified"))
      (node (ref "U13") (pin "12") (pinfunction "OUT7_12") (pintype "unspecified"))
    )
    (net (code "236") (name "Net-(LED233-K)") (class "Default")
      (node (ref "LED233") (pin "1") (pinfunction "K_1") (pintype "unspecified"))
      (node (ref "U14") (pin "5") (pinfunction "OUT0_5") (pintype "unspecified"))
    )
    (net (code "237") (name "Net-(LED234-K)") (class "Default")
      (node (ref "LED234") (pin "1") (pinfunction "K_1") (pintype "unspecified"))
      (node (ref "U14") (pin "6") (pinfunction "OUT1_6") (pintype "unspecified"))
    )
    (net (code "238") (name "Net-(LED235-K)") (class "Default")
      (node (ref "LED235") (pin "1") (pinfunction "K_1") (pintype "unspecified"))
      (node (ref "U14") (pin "7") (pinfunction "OUT2_7") (pintype "unspecified"))
    )
    (net (code "239") (name "Net-(LED236-K)") (class "Default")
      (node (ref "LED236") (pin "1") (pinfunction "K_1") (pintype "unspecified"))
      (node (ref "U14") (pin "8") (pinfunction "OUT3_8") (pintype "unspecified"))
    )
    (net (code "240") (name "Net-(LED237-K)") (class "Default")
      (node (ref "LED237") (pin "1") (pinfunction "K_1") (pintype "unspecified"))
      (node (ref "U14") (pin "9") (pinfunction "OUT4_9") (pintype "unspecified"))
    )
    (net (code "241") (name "Net-(LED238-K)") (class "Default")
      (node (ref "LED238") (pin "1") (pinfunction "K_1") (pintype "unspecified"))
      (node (ref "U14") (pin "10") (pinfunction "OUT5_10") (pintype "unspecified"))
    )
    (net (code "242") (name "Net-(LED239-K)") (class "Default")
      (node (ref "LED239") (pin "1") (pinfunction "K_1") (pintype "unspecified"))
      (node (ref "U14") (pin "11") (pinfunction "OUT6_11") (pintype "unspecified"))
    )
    (net (code "243") (name "Net-(LED240-K)") (class "Default")
      (node (ref "LED240") (pin "1") (pinfunction "K_1") (pintype "unspecified"))
      (node (ref "U14") (pin "12") (pinfunction "OUT7_12") (pintype "unspecified"))
    )
    (net (code "244") (name "Net-(LED241-K)") (class "Default")
      (node (ref "LED241") (pin "1") (pinfunction "K_1") (pintype "unspecified"))
      (node (ref "U15") (pin "5") (pinfunction "OUT0_5") (pintype "unspecified"))
    )
    (net (code "245") (name "Net-(LED242-K)") (class "Default")
      (node (ref "LED242") (pin "1") (pinfunction "K_1") (pintype "unspecified"))
      (node (ref "U15") (pin "6") (pinfunction "OUT1_6") (pintype "unspecified"))
    )
    (net (code "246") (name "Net-(LED243-K)") (class "Default")
      (node (ref "LED243") (pin "1") (pinfunction "K_1") (pintype "unspecified"))
      (node (ref "U15") (pin "7") (pinfunction "OUT2_7") (pintype "unspecified"))
    )
    (net (code "247") (name "Net-(LED244-K)") (class "Default")
      (node (ref "LED244") (pin "1") (pinfunction "K_1") (pintype "unspecified"))
      (node (ref "U15") (pin "8") (pinfunction "OUT3_8") (pintype "unspecified"))
    )
    (net (code "248") (name "Net-(LED245-K)") (class "Default")
      (node (ref "LED245") (pin "1") (pinfunction "K_1") (pintype "unspecified"))
      (node (ref "U15") (pin "9") (pinfunction "OUT4_9") (pintype "unspecified"))
    )
    (net (code "249") (name "Net-(LED246-K)") (class "Default")
      (node (ref "LED246") (pin "1") (pinfunction "K_1") (pintype "unspecified"))
      (node (ref "U15") (pin "10") (pinfunction "OUT5_10") (pintype "unspecified"))
    )
    (net (code "250") (name "Net-(LED247-K)") (class "Default")
      (node (ref "LED247") (pin "1") (pinfunction "K_1") (pintype "unspecified"))
      (node (ref "U15") (pin "11") (pinfunction "OUT6_11") (pintype "unspecified"))
    )
    (net (code "251") (name "Net-(LED248-K)") (class "Default")
      (node (ref "LED248") (pin "1") (pinfunction "K_1") (pintype "unspecified"))
      (node (ref "U15") (pin "12") (pinfunction "OUT7_12") (pintype "unspecified"))
    )
    (net (code "252") (name "Net-(LED249-K)") (class "Default")
      (node (ref "LED249") (pin "1") (pinfunction "K_1") (pintype "unspecified"))
      (node (ref "U16") (pin "5") (pinfunction "OUT0_5") (pintype "unspecified"))
    )
    (net (code "253") (name "Net-(LED250-K)") (class "Default")
      (node (ref "LED250") (pin "1") (pinfunction "K_1") (pintype "unspecified"))
      (node (ref "U16") (pin "6") (pinfunction "OUT1_6") (pintype "unspecified"))
    )
    (net (code "254") (name "Net-(LED251-K)") (class "Default")
      (node (ref "LED251") (pin "1") (pinfunction "K_1") (pintype "unspecified"))
      (node (ref "U16") (pin "7") (pinfunction "OUT2_7") (pintype "unspecified"))
    )
    (net (code "255") (name "Net-(LED252-K)") (class "Default")
      (node (ref "LED252") (pin "1") (pinfunction "K_1") (pintype "unspecified"))
      (node (ref "U16") (pin "8") (pinfunction "OUT3_8") (pintype "unspecified"))
    )
    (net (code "256") (name "Net-(LED253-K)") (class "Default")
      (node (ref "LED253") (pin "1") (pinfunction "K_1") (pintype "unspecified"))
      (node (ref "U16") (pin "9") (pinfunction "OUT4_9") (pintype "unspecified"))
    )
    (net (code "257") (name "Net-(LED254-K)") (class "Default")
      (node (ref "LED254") (pin "1") (pinfunction "K_1") (pintype "unspecified"))
      (node (ref "U16") (pin "10") (pinfunction "OUT5_10") (pintype "unspecified"))
    )
    (net (code "258") (name "Net-(LED255-K)") (class "Default")
      (node (ref "LED255") (pin "1") (pinfunction "K_1") (pintype "unspecified"))
      (node (ref "U16") (pin "11") (pinfunction "OUT6_11") (pintype "unspecified"))
    )
    (net (code "259") (name "Net-(LED256-K)") (class "Default")
      (node (ref "LED256") (pin "1") (pinfunction "K_1") (pintype "unspecified"))
      (node (ref "U16") (pin "12") (pinfunction "OUT7_12") (pintype "unspecified"))
    )
    (net (code "260") (name "Net-(U1-IREF)") (class "Default")
      (node (ref "R1") (pin "1") (pinfunction "1_1") (pintype "input"))
      (node (ref "U1") (pin "23") (pinfunction "IREF_23") (pintype "unspecified"))
    )
    (net (code "261") (name "Net-(U1-SIN)") (class "Default")
      (node (ref "U1") (pin "2") (pinfunction "SIN_2") (pintype "unspecified"))
      (node (ref "U8") (pin "22") (pinfunction "SOUT_22") (pintype "unspecified"))
    )
    (net (code "262") (name "Net-(U1-SOUT)") (class "Default")
      (node (ref "U1") (pin "22") (pinfunction "SOUT_22") (pintype "unspecified"))
      (node (ref "U2") (pin "2") (pinfunction "SIN_2") (pintype "unspecified"))
    )
    (net (code "263") (name "Net-(U2-IREF)") (class "Default")
      (node (ref "R2") (pin "1") (pinfunction "1_1") (pintype "input"))
      (node (ref "U2") (pin "23") (pinfunction "IREF_23") (pintype "unspecified"))
    )
    (net (code "264") (name "Net-(U2-SOUT)") (class "Default")
      (node (ref "U2") (pin "22") (pinfunction "SOUT_22") (pintype "unspecified"))
      (node (ref "U3") (pin "2") (pinfunction "SIN_2") (pintype "unspecified"))
    )
    (net (code "265") (name "Net-(U3-IREF)") (class "Default")
      (node (ref "R3") (pin "1") (pinfunction "1_1") (pintype "input"))
      (node (ref "U3") (pin "23") (pinfunction "IREF_23") (pintype "unspecified"))
    )
    (net (code "266") (name "Net-(U3-SOUT)") (class "Default")
      (node (ref "U3") (pin "22") (pinfunction "SOUT_22") (pintype "unspecified"))
      (node (ref "U4") (pin "2") (pinfunction "SIN_2") (pintype "unspecified"))
    )
    (net (code "267") (name "Net-(U4-IREF)") (class "Default")
      (node (ref "R4") (pin "1") (pinfunction "1_1") (pintype "input"))
      (node (ref "U4") (pin "23") (pinfunction "IREF_23") (pintype "unspecified"))
    )
    (net (code "268") (name "Net-(U5-IREF)") (class "Default")
      (node (ref "R5") (pin "1") (pinfunction "1_1") (pintype "input"))
      (node (ref "U5") (pin "23") (pinfunction "IREF_23") (pintype "unspecified"))
    )
    (net (code "269") (name "Net-(U5-SOUT)") (class "Default")
      (node (ref "U5") (pin "22") (pinfunction "SOUT_22") (pintype "unspecified"))
      (node (ref "U6") (pin "2") (pinfunction "SIN_2") (pintype "unspecified"))
    )
    (net (code "270") (name "Net-(U6-IREF)") (class "Default")
      (node (ref "R6") (pin "1") (pinfunction "1_1") (pintype "input"))
      (node (ref "U6") (pin "23") (pinfunction "IREF_23") (pintype "unspecified"))
    )
    (net (code "271") (name "Net-(U6-SOUT)") (class "Default")
      (node (ref "U6") (pin "22") (pinfunction "SOUT_22") (pintype "unspecified"))
      (node (ref "U7") (pin "2") (pinfunction "SIN_2") (pintype "unspecified"))
    )
    (net (code "272") (name "Net-(U7-IREF)") (class "Default")
      (node (ref "R7") (pin "1") (pinfunction "1_1") (pintype "input"))
      (node (ref "U7") (pin "23") (pinfunction "IREF_23") (pintype "unspecified"))
    )
    (net (code "273") (name "Net-(U7-SOUT)") (class "Default")
      (node (ref "U7") (pin "22") (pinfunction "SOUT_22") (pintype "unspecified"))
      (node (ref "U8") (pin "2") (pinfunction "SIN_2") (pintype "unspecified"))
    )
    (net (code "274") (name "Net-(U8-IREF)") (class "Default")
      (node (ref "R8") (pin "1") (pinfunction "1_1") (pintype "input"))
      (node (ref "U8") (pin "23") (pinfunction "IREF_23") (pintype "unspecified"))
    )
    (net (code "275") (name "Net-(U9-IREF)") (class "Default")
      (node (ref "R9") (pin "1") (pinfunction "1_1") (pintype "input"))
      (node (ref "U9") (pin "23") (pinfunction "IREF_23") (pintype "unspecified"))
    )
    (net (code "276") (name "Net-(U10-IREF)") (class "Default")
      (node (ref "R10") (pin "1") (pinfunction "1_1") (pintype "input"))
      (node (ref "U10") (pin "23") (pinfunction "IREF_23") (pintype "unspecified"))
    )
    (net (code "277") (name "Net-(U10-SIN)") (class "Default")
      (node (ref "U10") (pin "2") (pinfunction "SIN_2") (pintype "unspecified"))
      (node (ref "U9") (pin "22") (pinfunction "SOUT_22") (pintype "unspecified"))
    )
    (net (code "278") (name "Net-(U10-SOUT)") (class "Default")
      (node (ref "U10") (pin "22") (pinfunction "SOUT_22") (pintype "unspecified"))
      (node (ref "U11") (pin "2") (pinfunction "SIN_2") (pintype "unspecified"))
    )
    (net (code "279") (name "Net-(U11-IREF)") (class "Default")
      (node (ref "R11") (pin "1") (pinfunction "1_1") (pintype "input"))
      (node (ref "U11") (pin "23") (pinfunction "IREF_23") (pintype "unspecified"))
    )
    (net (code "280") (name "Net-(U11-SOUT)") (class "Default")
      (node (ref "U11") (pin "22") (pinfunction "SOUT_22") (pintype "unspecified"))
      (node (ref "U12") (pin "2") (pinfunction "SIN_2") (pintype "unspecified"))
    )
    (net (code "281") (name "Net-(U12-IREF)") (class "Default")
      (node (ref "R12") (pin "1") (pinfunction "1_1") (pintype "input"))
      (node (ref "U12") (pin "23") (pinfunction "IREF_23") (pintype "unspecified"))
    )
    (net (code "282") (name "Net-(U12-SOUT)") (class "Default")
      (node (ref "U12") (pin "22") (pinfunction "SOUT_22") (pintype "unspecified"))
      (node (ref "U5") (pin "2") (pinfunction "SIN_2") (pintype "unspecified"))
    )
    (net (code "283") (name "Net-(U13-IREF)") (class "Default")
      (node (ref "R13") (pin "1") (pinfunction "1_1") (pintype "input"))
      (node (ref "U13") (pin "23") (pinfunction "IREF_23") (pintype "unspecified"))
    )
    (net (code "284") (name "Net-(U13-SOUT)") (class "Default")
      (node (ref "U13") (pin "22") (pinfunction "SOUT_22") (pintype "unspecified"))
      (node (ref "U14") (pin "2") (pinfunction "SIN_2") (pintype "unspecified"))
    )
    (net (code "285") (name "Net-(U14-IREF)") (class "Default")
      (node (ref "R14") (pin "1") (pinfunction "1_1") (pintype "input"))
      (node (ref "U14") (pin "23") (pinfunction "IREF_23") (pintype "unspecified"))
    )
    (net (code "286") (name "Net-(U14-SOUT)") (class "Default")
      (node (ref "U14") (pin "22") (pinfunction "SOUT_22") (pintype "unspecified"))
      (node (ref "U15") (pin "2") (pinfunction "SIN_2") (pintype "unspecified"))
    )
    (net (code "287") (name "Net-(U15-IREF)") (class "Default")
      (node (ref "R15") (pin "1") (pinfunction "1_1") (pintype "input"))
      (node (ref "U15") (pin "23") (pinfunction "IREF_23") (pintype "unspecified"))
    )
    (net (code "288") (name "Net-(U15-SOUT)") (class "Default")
      (node (ref "U15") (pin "22") (pinfunction "SOUT_22") (pintype "unspecified"))
      (node (ref "U16") (pin "2") (pinfunction "SIN_2") (pintype "unspecified"))
    )
    (net (code "289") (name "Net-(U16-IREF)") (class "Default")
      (node (ref "R16") (pin "1") (pinfunction "1_1") (pintype "input"))
      (node (ref "U16") (pin "23") (pinfunction "IREF_23") (pintype "unspecified"))
    )
    (net (code "290") (name "Net-(U16-SOUT)") (class "Default")
      (node (ref "U16") (pin "22") (pinfunction "SOUT_22") (pintype "unspecified"))
      (node (ref "U9") (pin "2") (pinfunction "SIN_2") (pintype "unspecified"))
    )
    (net (code "291") (name "SCLK") (class "Default")
      (node (ref "U1") (pin "3") (pinfunction "SCLK_3") (pintype "unspecified"))
      (node (ref "U10") (pin "3") (pinfunction "SCLK_3") (pintype "unspecified"))
      (node (ref "U11") (pin "3") (pinfunction "SCLK_3") (pintype "unspecified"))
      (node (ref "U12") (pin "3") (pinfunction "SCLK_3") (pintype "unspecified"))
      (node (ref "U13") (pin "3") (pinfunction "SCLK_3") (pintype "unspecified"))
      (node (ref "U14") (pin "3") (pinfunction "SCLK_3") (pintype "unspecified"))
      (node (ref "U15") (pin "3") (pinfunction "SCLK_3") (pintype "unspecified"))
      (node (ref "U16") (pin "3") (pinfunction "SCLK_3") (pintype "unspecified"))
      (node (ref "U2") (pin "3") (pinfunction "SCLK_3") (pintype "unspecified"))
      (node (ref "U3") (pin "3") (pinfunction "SCLK_3") (pintype "unspecified"))
      (node (ref "U4") (pin "3") (pinfunction "SCLK_3") (pintype "unspecified"))
      (node (ref "U5") (pin "3") (pinfunction "SCLK_3") (pintype "unspecified"))
      (node (ref "U6") (pin "3") (pinfunction "SCLK_3") (pintype "unspecified"))
      (node (ref "U7") (pin "3") (pinfunction "SCLK_3") (pintype "unspecified"))
      (node (ref "U8") (pin "3") (pinfunction "SCLK_3") (pintype "unspecified"))
      (node (ref "U9") (pin "3") (pinfunction "SCLK_3") (pintype "unspecified"))
    )
    (net (code "292") (name "SIN") (class "Default")
      (node (ref "U13") (pin "2") (pinfunction "SIN_2") (pintype "unspecified"))
    )
    (net (code "293") (name "SOUT") (class "Default")
      (node (ref "U4") (pin "22") (pinfunction "SOUT_22") (pintype "unspecified"))
    )
    (net (code "294") (name "VCC") (class "Default")
      (node (ref "C1") (pin "1") (pinfunction "1_1") (pintype "unspecified"))
      (node (ref "C10") (pin "1") (pinfunction "1_1") (pintype "unspecified"))
      (node (ref "C11") (pin "1") (pinfunction "1_1") (pintype "unspecified"))
      (node (ref "C12") (pin "1") (pinfunction "1_1") (pintype "unspecified"))
      (node (ref "C13") (pin "1") (pinfunction "1_1") (pintype "unspecified"))
      (node (ref "C14") (pin "1") (pinfunction "1_1") (pintype "unspecified"))
      (node (ref "C15") (pin "1") (pinfunction "1_1") (pintype "unspecified"))
      (node (ref "C16") (pin "1") (pinfunction "1_1") (pintype "unspecified"))
      (node (ref "C17") (pin "2") (pinfunction "2_2") (pintype "unspecified"))
      (node (ref "C18") (pin "2") (pinfunction "2_2") (pintype "unspecified"))
      (node (ref "C19") (pin "2") (pinfunction "2_2") (pintype "unspecified"))
      (node (ref "C2") (pin "1") (pinfunction "1_1") (pintype "unspecified"))
      (node (ref "C20") (pin "2") (pinfunction "2_2") (pintype "unspecified"))
      (node (ref "C21") (pin "2") (pinfunction "2_2") (pintype "unspecified"))
      (node (ref "C22") (pin "2") (pinfunction "2_2") (pintype "unspecified"))
      (node (ref "C23") (pin "2") (pinfunction "2_2") (pintype "unspecified"))
      (node (ref "C24") (pin "2") (pinfunction "2_2") (pintype "unspecified"))
      (node (ref "C3") (pin "1") (pinfunction "1_1") (pintype "unspecified"))
      (node (ref "C4") (pin "1") (pinfunction "1_1") (pintype "unspecified"))
      (node (ref "C5") (pin "1") (pinfunction "1_1") (pintype "unspecified"))
      (node (ref "C6") (pin "1") (pinfunction "1_1") (pintype "unspecified"))
      (node (ref "C7") (pin "1") (pinfunction "1_1") (pintype "unspecified"))
      (node (ref "C8") (pin "1") (pinfunction "1_1") (pintype "unspecified"))
      (node (ref "C9") (pin "1") (pinfunction "1_1") (pintype "unspecified"))
      (node (ref "LED1") (pin "2") (pinfunction "A_2") (pintype "unspecified"))
      (node (ref "LED10") (pin "2") (pinfunction "A_2") (pintype "unspecified"))
      (node (ref "LED100") (pin "2") (pinfunction "A_2") (pintype "unspecified"))
      (node (ref "LED101") (pin "2") (pinfunction "A_2") (pintype "unspecified"))
      (node (ref "LED102") (pin "2") (pinfunction "A_2") (pintype "unspecified"))
      (node (ref "LED103") (pin "2") (pinfunction "A_2") (pintype "unspecified"))
      (node (ref "LED104") (pin "2") (pinfunction "A_2") (pintype "unspecified"))
      (node (ref "LED105") (pin "2") (pinfunction "A_2") (pintype "unspecified"))
      (node (ref "LED106") (pin "2") (pinfunction "A_2") (pintype "unspecified"))
      (node (ref "LED107") (pin "2") (pinfunction "A_2") (pintype "unspecified"))
      (node (ref "LED108") (pin "2") (pinfunction "A_2") (pintype "unspecified"))
      (node (ref "LED109") (pin "2") (pinfunction "A_2") (pintype "unspecified"))
      (node (ref "LED11") (pin "2") (pinfunction "A_2") (pintype "unspecified"))
      (node (ref "LED110") (pin "2") (pinfunction "A_2") (pintype "unspecified"))
      (node (ref "LED111") (pin "2") (pinfunction "A_2") (pintype "unspecified"))
      (node (ref "LED112") (pin "2") (pinfunction "A_2") (pintype "unspecified"))
      (node (ref "LED113") (pin "2") (pinfunction "A_2") (pintype "unspecified"))
      (node (ref "LED114") (pin "2") (pinfunction "A_2") (pintype "unspecified"))
      (node (ref "LED115") (pin "2") (pinfunction "A_2") (pintype "unspecified"))
      (node (ref "LED116") (pin "2") (pinfunction "A_2") (pintype "unspecified"))
      (node (ref "LED117") (pin "2") (pinfunction "A_2") (pintype "unspecified"))
      (node (ref "LED118") (pin "2") (pinfunction "A_2") (pintype "unspecified"))
      (node (ref "LED119") (pin "2") (pinfunction "A_2") (pintype "unspecified"))
      (node (ref "LED12") (pin "2") (pinfunction "A_2") (pintype "unspecified"))
      (node (ref "LED120") (pin "2") (pinfunction "A_2") (pintype "unspecified"))
      (node (ref "LED121") (pin "2") (pinfunction "A_2") (pintype "unspecified"))
      (node (ref "LED122") (pin "2") (pinfunction "A_2") (pintype "unspecified"))
      (node (ref "LED123") (pin "2") (pinfunction "A_2") (pintype "unspecified"))
      (node (ref "LED124") (pin "2") (pinfunction "A_2") (pintype "unspecified"))
      (node (ref "LED125") (pin "2") (pinfunction "A_2") (pintype "unspecified"))
      (node (ref "LED126") (pin "2") (pinfunction "A_2") (pintype "unspecified"))
      (node (ref "LED127") (pin "2") (pinfunction "A_2") (pintype "unspecified"))
      (node (ref "LED128") (pin "2") (pinfunction "A_2") (pintype "unspecified"))
      (node (ref "LED129") (pin "2") (pinfunction "A_2") (pintype "unspecified"))
      (node (ref "LED13") (pin "2") (pinfunction "A_2") (pintype "unspecified"))
      (node (ref "LED130") (pin "2") (pinfunction "A_2") (pintype "unspecified"))
      (node (ref "LED131") (pin "2") (pinfunction "A_2") (pintype "unspecified"))
      (node (ref "LED132") (pin "2") (pinfunction "A_2") (pintype "unspecified"))
      (node (ref "LED133") (pin "2") (pinfunction "A_2") (pintype "unspecified"))
      (node (ref "LED134") (pin "2") (pinfunction "A_2") (pintype "unspecified"))
      (node (ref "LED135") (pin "2") (pinfunction "A_2") (pintype "unspecified"))
      (node (ref "LED136") (pin "2") (pinfunction "A_2") (pintype "unspecified"))
      (node (ref "LED137") (pin "2") (pinfunction "A_2") (pintype "unspecified"))
      (node (ref "LED138") (pin "2") (pinfunction "A_2") (pintype "unspecified"))
      (node (ref "LED139") (pin "2") (pinfunction "A_2") (pintype "unspecified"))
      (node (ref "LED14") (pin "2") (pinfunction "A_2") (pintype "unspecified"))
      (node (ref "LED140") (pin "2") (pinfunction "A_2") (pintype "unspecified"))
      (node (ref "LED141") (pin "2") (pinfunction "A_2") (pintype "unspecified"))
      (node (ref "LED142") (pin "2") (pinfunction "A_2") (pintype "unspecified"))
      (node (ref "LED143") (pin "2") (pinfunction "A_2") (pintype "unspecified"))
      (node (ref "LED144") (pin "2") (pinfunction "A_2") (pintype "unspecified"))
      (node (ref "LED145") (pin "2") (pinfunction "A_2") (pintype "unspecified"))
      (node (ref "LED146") (pin "2") (pinfunction "A_2") (pintype "unspecified"))
      (node (ref "LED147") (pin "2") (pinfunction "A_2") (pintype "unspecified"))
      (node (ref "LED148") (pin "2") (pinfunction "A_2") (pintype "unspecified"))
      (node (ref "LED149") (pin "2") (pinfunction "A_2") (pintype "unspecified"))
      (node (ref "LED15") (pin "2") (pinfunction "A_2") (pintype "unspecified"))
      (node (ref "LED150") (pin "2") (pinfunction "A_2") (pintype "unspecified"))
      (node (ref "LED151") (pin "2") (pinfunction "A_2") (pintype "unspecified"))
      (node (ref "LED152") (pin "2") (pinfunction "A_2") (pintype "unspecified"))
      (node (ref "LED153") (pin "2") (pinfunction "A_2") (pintype "unspecified"))
      (node (ref "LED154") (pin "2") (pinfunction "A_2") (pintype "unspecified"))
      (node (ref "LED155") (pin "2") (pinfunction "A_2") (pintype "unspecified"))
      (node (ref "LED156") (pin "2") (pinfunction "A_2") (pintype "unspecified"))
      (node (ref "LED157") (pin "2") (pinfunction "A_2") (pintype "unspecified"))
      (node (ref "LED158") (pin "2") (pinfunction "A_2") (pintype "unspecified"))
      (node (ref "LED159") (pin "2") (pinfunction "A_2") (pintype "unspecified"))
      (node (ref "LED16") (pin "2") (pinfunction "A_2") (pintype "unspecified"))
      (node (ref "LED160") (pin "2") (pinfunction "A_2") (pintype "unspecified"))
      (node (ref "LED161") (pin "2") (pinfunction "A_2") (pintype "unspecified"))
      (node (ref "LED162") (pin "2") (pinfunction "A_2") (pintype "unspecified"))
      (node (ref "LED163") (pin "2") (pinfunction "A_2") (pintype "unspecified"))
      (node (ref "LED164") (pin "2") (pinfunction "A_2") (pintype "unspecified"))
      (node (ref "LED165") (pin "2") (pinfunction "A_2") (pintype "unspecified"))
      (node (ref "LED166") (pin "2") (pinfunction "A_2") (pintype "unspecified"))
      (node (ref "LED167") (pin "2") (pinfunction "A_2") (pintype "unspecified"))
      (node (ref "LED168") (pin "2") (pinfunction "A_2") (pintype "unspecified"))
      (node (ref "LED169") (pin "2") (pinfunction "A_2") (pintype "unspecified"))
      (node (ref "LED17") (pin "2") (pinfunction "A_2") (pintype "unspecified"))
      (node (ref "LED170") (pin "2") (pinfunction "A_2") (pintype "unspecified"))
      (node (ref "LED171") (pin "2") (pinfunction "A_2") (pintype "unspecified"))
      (node (ref "LED172") (pin "2") (pinfunction "A_2") (pintype "unspecified"))
      (node (ref "LED173") (pin "2") (pinfunction "A_2") (pintype "unspecified"))
      (node (ref "LED174") (pin "2") (pinfunction "A_2") (pintype "unspecified"))
      (node (ref "LED175") (pin "2") (pinfunction "A_2") (pintype "unspecified"))
      (node (ref "LED176") (pin "2") (pinfunction "A_2") (pintype "unspecified"))
      (node (ref "LED177") (pin "2") (pinfunction "A_2") (pintype "unspecified"))
      (node (ref "LED178") (pin "2") (pinfunction "A_2") (pintype "unspecified"))
      (node (ref "LED179") (pin "2") (pinfunction "A_2") (pintype "unspecified"))
      (node (ref "LED18") (pin "2") (pinfunction "A_2") (pintype "unspecified"))
      (node (ref "LED180") (pin "2") (pinfunction "A_2") (pintype "unspecified"))
      (node (ref "LED181") (pin "2") (pinfunction "A_2") (pintype "unspecified"))
      (node (ref "LED182") (pin "2") (pinfunction "A_2") (pintype "unspecified"))
      (node (ref "LED183") (pin "2") (pinfunction "A_2") (pintype "unspecified"))
      (node (ref "LED184") (pin "2") (pinfunction "A_2") (pintype "unspecified"))
      (node (ref "LED185") (pin "2") (pinfunction "A_2") (pintype "unspecified"))
      (node (ref "LED186") (pin "2") (pinfunction "A_2") (pintype "unspecified"))
      (node (ref "LED187") (pin "2") (pinfunction "A_2") (pintype "unspecified"))
      (node (ref "LED188") (pin "2") (pinfunction "A_2") (pintype "unspecified"))
      (node (ref "LED189") (pin "2") (pinfunction "A_2") (pintype "unspecified"))
      (node (ref "LED19") (pin "2") (pinfunction "A_2") (pintype "unspecified"))
      (node (ref "LED190") (pin "2") (pinfunction "A_2") (pintype "unspecified"))
      (node (ref "LED191") (pin "2") (pinfunction "A_2") (pintype "unspecified"))
      (node (ref "LED192") (pin "2") (pinfunction "A_2") (pintype "unspecified"))
      (node (ref "LED193") (pin "2") (pinfunction "A_2") (pintype "unspecified"))
      (node (ref "LED194") (pin "2") (pinfunction "A_2") (pintype "unspecified"))
      (node (ref "LED195") (pin "2") (pinfunction "A_2") (pintype "unspecified"))
      (node (ref "LED196") (pin "2") (pinfunction "A_2") (pintype "unspecified"))
      (node (ref "LED197") (pin "2") (pinfunction "A_2") (pintype "unspecified"))
      (node (ref "LED198") (pin "2") (pinfunction "A_2") (pintype "unspecified"))
      (node (ref "LED199") (pin "2") (pinfunction "A_2") (pintype "unspecified"))
      (node (ref "LED2") (pin "2") (pinfunction "A_2") (pintype "unspecified"))
      (node (ref "LED20") (pin "2") (pinfunction "A_2") (pintype "unspecified"))
      (node (ref "LED200") (pin "2") (pinfunction "A_2") (pintype "unspecified"))
      (node (ref "LED201") (pin "2") (pinfunction "A_2") (pintype "unspecified"))
      (node (ref "LED202") (pin "2") (pinfunction "A_2") (pintype "unspecified"))
      (node (ref "LED203") (pin "2") (pinfunction "A_2") (pintype "unspecified"))
      (node (ref "LED204") (pin "2") (pinfunction "A_2") (pintype "unspecified"))
      (node (ref "LED205") (pin "2") (pinfunction "A_2") (pintype "unspecified"))
      (node (ref "LED206") (pin "2") (pinfunction "A_2") (pintype "unspecified"))
      (node (ref "LED207") (pin "2") (pinfunction "A_2") (pintype "unspecified"))
      (node (ref "LED208") (pin "2") (pinfunction "A_2") (pintype "unspecified"))
      (node (ref "LED209") (pin "2") (pinfunction "A_2") (pintype "unspecified"))
      (node (ref "LED21") (pin "2") (pinfunction "A_2") (pintype "unspecified"))
      (node (ref "LED210") (pin "2") (pinfunction "A_2") (pintype "unspecified"))
      (node (ref "LED211") (pin "2") (pinfunction "A_2") (pintype "unspecified"))
      (node (ref "LED212") (pin "2") (pinfunction "A_2") (pintype "unspecified"))
      (node (ref "LED213") (pin "2") (pinfunction "A_2") (pintype "unspecified"))
      (node (ref "LED214") (pin "2") (pinfunction "A_2") (pintype "unspecified"))
      (node (ref "LED215") (pin "2") (pinfunction "A_2") (pintype "unspecified"))
      (node (ref "LED216") (pin "2") (pinfunction "A_2") (pintype "unspecified"))
      (node (ref "LED217") (pin "2") (pinfunction "A_2") (pintype "unspecified"))
      (node (ref "LED218") (pin "2") (pinfunction "A_2") (pintype "unspecified"))
      (node (ref "LED219") (pin "2") (pinfunction "A_2") (pintype "unspecified"))
      (node (ref "LED22") (pin "2") (pinfunction "A_2") (pintype "unspecified"))
      (node (ref "LED220") (pin "2") (pinfunction "A_2") (pintype "unspecified"))
      (node (ref "LED221") (pin "2") (pinfunction "A_2") (pintype "unspecified"))
      (node (ref "LED222") (pin "2") (pinfunction "A_2") (pintype "unspecified"))
      (node (ref "LED223") (pin "2") (pinfunction "A_2") (pintype "unspecified"))
      (node (ref "LED224") (pin "2") (pinfunction "A_2") (pintype "unspecified"))
      (node (ref "LED225") (pin "2") (pinfunction "A_2") (pintype "unspecified"))
      (node (ref "LED226") (pin "2") (pinfunction "A_2") (pintype "unspecified"))
      (node (ref "LED227") (pin "2") (pinfunction "A_2") (pintype "unspecified"))
      (node (ref "LED228") (pin "2") (pinfunction "A_2") (pintype "unspecified"))
      (node (ref "LED229") (pin "2") (pinfunction "A_2") (pintype "unspecified"))
      (node (ref "LED23") (pin "2") (pinfunction "A_2") (pintype "unspecified"))
      (node (ref "LED230") (pin "2") (pinfunction "A_2") (pintype "unspecified"))
      (node (ref "LED231") (pin "2") (pinfunction "A_2") (pintype "unspecified"))
      (node (ref "LED232") (pin "2") (pinfunction "A_2") (pintype "unspecified"))
      (node (ref "LED233") (pin "2") (pinfunction "A_2") (pintype "unspecified"))
      (node (ref "LED234") (pin "2") (pinfunction "A_2") (pintype "unspecified"))
      (node (ref "LED235") (pin "2") (pinfunction "A_2") (pintype "unspecified"))
      (node (ref "LED236") (pin "2") (pinfunction "A_2") (pintype "unspecified"))
      (node (ref "LED237") (pin "2") (pinfunction "A_2") (pintype "unspecified"))
      (node (ref "LED238") (pin "2") (pinfunction "A_2") (pintype "unspecified"))
      (node (ref "LED239") (pin "2") (pinfunction "A_2") (pintype "unspecified"))
      (node (ref "LED24") (pin "2") (pinfunction "A_2") (pintype "unspecified"))
      (node (ref "LED240") (pin "2") (pinfunction "A_2") (pintype "unspecified"))
      (node (ref "LED241") (pin "2") (pinfunction "A_2") (pintype "unspecified"))
      (node (ref "LED242") (pin "2") (pinfunction "A_2") (pintype "unspecified"))
      (node (ref "LED243") (pin "2") (pinfunction "A_2") (pintype "unspecified"))
      (node (ref "LED244") (pin "2") (pinfunction "A_2") (pintype "unspecified"))
      (node (ref "LED245") (pin "2") (pinfunction "A_2") (pintype "unspecified"))
      (node (ref "LED246") (pin "2") (pinfunction "A_2") (pintype "unspecified"))
      (node (ref "LED247") (pin "2") (pinfunction "A_2") (pintype "unspecified"))
      (node (ref "LED248") (pin "2") (pinfunction "A_2") (pintype "unspecified"))
      (node (ref "LED249") (pin "2") (pinfunction "A_2") (pintype "unspecified"))
      (node (ref "LED25") (pin "2") (pinfunction "A_2") (pintype "unspecified"))
      (node (ref "LED250") (pin "2") (pinfunction "A_2") (pintype "unspecified"))
      (node (ref "LED251") (pin "2") (pinfunction "A_2") (pintype "unspecified"))
      (node (ref "LED252") (pin "2") (pinfunction "A_2") (pintype "unspecified"))
      (node (ref "LED253") (pin "2") (pinfunction "A_2") (pintype "unspecified"))
      (node (ref "LED254") (pin "2") (pinfunction "A_2") (pintype "unspecified"))
      (node (ref "LED255") (pin "2") (pinfunction "A_2") (pintype "unspecified"))
      (node (ref "LED256") (pin "2") (pinfunction "A_2") (pintype "unspecified"))
      (node (ref "LED26") (pin "2") (pinfunction "A_2") (pintype "unspecified"))
      (node (ref "LED27") (pin "2") (pinfunction "A_2") (pintype "unspecified"))
      (node (ref "LED28") (pin "2") (pinfunction "A_2") (pintype "unspecified"))
      (node (ref "LED29") (pin "2") (pinfunction "A_2") (pintype "unspecified"))
      (node (ref "LED3") (pin "2") (pinfunction "A_2") (pintype "unspecified"))
      (node (ref "LED30") (pin "2") (pinfunction "A_2") (pintype "unspecified"))
      (node (ref "LED31") (pin "2") (pinfunction "A_2") (pintype "unspecified"))
      (node (ref "LED32") (pin "2") (pinfunction "A_2") (pintype "unspecified"))
      (node (ref "LED33") (pin "2") (pinfunction "A_2") (pintype "unspecified"))
      (node (ref "LED34") (pin "2") (pinfunction "A_2") (pintype "unspecified"))
      (node (ref "LED35") (pin "2") (pinfunction "A_2") (pintype "unspecified"))
      (node (ref "LED36") (pin "2") (pinfunction "A_2") (pintype "unspecified"))
      (node (ref "LED37") (pin "2") (pinfunction "A_2") (pintype "unspecified"))
      (node (ref "LED38") (pin "2") (pinfunction "A_2") (pintype "unspecified"))
      (node (ref "LED39") (pin "2") (pinfunction "A_2") (pintype "unspecified"))
      (node (ref "LED4") (pin "2") (pinfunction "A_2") (pintype "unspecified"))
      (node (ref "LED40") (pin "2") (pinfunction "A_2") (pintype "unspecified"))
      (node (ref "LED41") (pin "2") (pinfunction "A_2") (pintype "unspecified"))
      (node (ref "LED42") (pin "2") (pinfunction "A_2") (pintype "unspecified"))
      (node (ref "LED43") (pin "2") (pinfunction "A_2") (pintype "unspecified"))
      (node (ref "LED44") (pin "2") (pinfunction "A_2") (pintype "unspecified"))
      (node (ref "LED45") (pin "2") (pinfunction "A_2") (pintype "unspecified"))
      (node (ref "LED46") (pin "2") (pinfunction "A_2") (pintype "unspecified"))
      (node (ref "LED47") (pin "2") (pinfunction "A_2") (pintype "unspecified"))
      (node (ref "LED48") (pin "2") (pinfunction "A_2") (pintype "unspecified"))
      (node (ref "LED49") (pin "2") (pinfunction "A_2") (pintype "unspecified"))
      (node (ref "LED5") (pin "2") (pinfunction "A_2") (pintype "unspecified"))
      (node (ref "LED50") (pin "2") (pinfunction "A_2") (pintype "unspecified"))
      (node (ref "LED51") (pin "2") (pinfunction "A_2") (pintype "unspecified"))
      (node (ref "LED52") (pin "2") (pinfunction "A_2") (pintype "unspecified"))
      (node (ref "LED53") (pin "2") (pinfunction "A_2") (pintype "unspecified"))
      (node (ref "LED54") (pin "2") (pinfunction "A_2") (pintype "unspecified"))
      (node (ref "LED55") (pin "2") (pinfunction "A_2") (pintype "unspecified"))
      (node (ref "LED56") (pin "2") (pinfunction "A_2") (pintype "unspecified"))
      (node (ref "LED57") (pin "2") (pinfunction "A_2") (pintype "unspecified"))
      (node (ref "LED58") (pin "2") (pinfunction "A_2") (pintype "unspecified"))
      (node (ref "LED59") (pin "2") (pinfunction "A_2") (pintype "unspecified"))
      (node (ref "LED6") (pin "2") (pinfunction "A_2") (pintype "unspecified"))
      (node (ref "LED60") (pin "2") (pinfunction "A_2") (pintype "unspecified"))
      (node (ref "LED61") (pin "2") (pinfunction "A_2") (pintype "unspecified"))
      (node (ref "LED62") (pin "2") (pinfunction "A_2") (pintype "unspecified"))
      (node (ref "LED63") (pin "2") (pinfunction "A_2") (pintype "unspecified"))
      (node (ref "LED64") (pin "2") (pinfunction "A_2") (pintype "unspecified"))
      (node (ref "LED65") (pin "2") (pinfunction "A_2") (pintype "unspecified"))
      (node (ref "LED66") (pin "2") (pinfunction "A_2") (pintype "unspecified"))
      (node (ref "LED67") (pin "2") (pinfunction "A_2") (pintype "unspecified"))
      (node (ref "LED68") (pin "2") (pinfunction "A_2") (pintype "unspecified"))
      (node (ref "LED69") (pin "2") (pinfunction "A_2") (pintype "unspecified"))
      (node (ref "LED7") (pin "2") (pinfunction "A_2") (pintype "unspecified"))
      (node (ref "LED70") (pin "2") (pinfunction "A_2") (pintype "unspecified"))
      (node (ref "LED71") (pin "2") (pinfunction "A_2") (pintype "unspecified"))
      (node (ref "LED72") (pin "2") (pinfunction "A_2") (pintype "unspecified"))
      (node (ref "LED73") (pin "2") (pinfunction "A_2") (pintype "unspecified"))
      (node (ref "LED74") (pin "2") (pinfunction "A_2") (pintype "unspecified"))
      (node (ref "LED75") (pin "2") (pinfunction "A_2") (pintype "unspecified"))
      (node (ref "LED76") (pin "2") (pinfunction "A_2") (pintype "unspecified"))
      (node (ref "LED77") (pin "2") (pinfunction "A_2") (pintype "unspecified"))
      (node (ref "LED78") (pin "2") (pinfunction "A_2") (pintype "unspecified"))
      (node (ref "LED79") (pin "2") (pinfunction "A_2") (pintype "unspecified"))
      (node (ref "LED8") (pin "2") (pinfunction "A_2") (pintype "unspecified"))
      (node (ref "LED80") (pin "2") (pinfunction "A_2") (pintype "unspecified"))
      (node (ref "LED81") (pin "2") (pinfunction "A_2") (pintype "unspecified"))
      (node (ref "LED82") (pin "2") (pinfunction "A_2") (pintype "unspecified"))
      (node (ref "LED83") (pin "2") (pinfunction "A_2") (pintype "unspecified"))
      (node (ref "LED84") (pin "2") (pinfunction "A_2") (pintype "unspecified"))
      (node (ref "LED85") (pin "2") (pinfunction "A_2") (pintype "unspecified"))
      (node (ref "LED86") (pin "2") (pinfunction "A_2") (pintype "unspecified"))
      (node (ref "LED87") (pin "2") (pinfunction "A_2") (pintype "unspecified"))
      (node (ref "LED88") (pin "2") (pinfunction "A_2") (pintype "unspecified"))
      (node (ref "LED89") (pin "2") (pinfunction "A_2") (pintype "unspecified"))
      (node (ref "LED9") (pin "2") (pinfunction "A_2") (pintype "unspecified"))
      (node (ref "LED90") (pin "2") (pinfunction "A_2") (pintype "unspecified"))
      (node (ref "LED91") (pin "2") (pinfunction "A_2") (pintype "unspecified"))
      (node (ref "LED92") (pin "2") (pinfunction "A_2") (pintype "unspecified"))
      (node (ref "LED93") (pin "2") (pinfunction "A_2") (pintype "unspecified"))
      (node (ref "LED94") (pin "2") (pinfunction "A_2") (pintype "unspecified"))
      (node (ref "LED95") (pin "2") (pinfunction "A_2") (pintype "unspecified"))
      (node (ref "LED96") (pin "2") (pinfunction "A_2") (pintype "unspecified"))
      (node (ref "LED97") (pin "2") (pinfunction "A_2") (pintype "unspecified"))
      (node (ref "LED98") (pin "2") (pinfunction "A_2") (pintype "unspecified"))
      (node (ref "LED99") (pin "2") (pinfunction "A_2") (pintype "unspecified"))
      (node (ref "U1") (pin "24") (pinfunction "VCC_24") (pintype "unspecified"))
      (node (ref "U10") (pin "24") (pinfunction "VCC_24") (pintype "unspecified"))
      (node (ref "U11") (pin "24") (pinfunction "VCC_24") (pintype "unspecified"))
      (node (ref "U12") (pin "24") (pinfunction "VCC_24") (pintype "unspecified"))
      (node (ref "U13") (pin "24") (pinfunction "VCC_24") (pintype "unspecified"))
      (node (ref "U14") (pin "24") (pinfunction "VCC_24") (pintype "unspecified"))
      (node (ref "U15") (pin "24") (pinfunction "VCC_24") (pintype "unspecified"))
      (node (ref "U16") (pin "24") (pinfunction "VCC_24") (pintype "unspecified"))
      (node (ref "U2") (pin "24") (pinfunction "VCC_24") (pintype "unspecified"))
      (node (ref "U3") (pin "24") (pinfunction "VCC_24") (pintype "unspecified"))
      (node (ref "U4") (pin "24") (pinfunction "VCC_24") (pintype "unspecified"))
      (node (ref "U5") (pin "24") (pinfunction "VCC_24") (pintype "unspecified"))
      (node (ref "U6") (pin "24") (pinfunction "VCC_24") (pintype "unspecified"))
      (node (ref "U7") (pin "24") (pinfunction "VCC_24") (pintype "unspecified"))
      (node (ref "U8") (pin "24") (pinfunction "VCC_24") (pintype "unspecified"))
      (node (ref "U9") (pin "24") (pinfunction "VCC_24") (pintype "unspecified"))
    )
  )
)
